# Replicape_B4.net
KiCad netlist of a schematic drawn in EAGLE
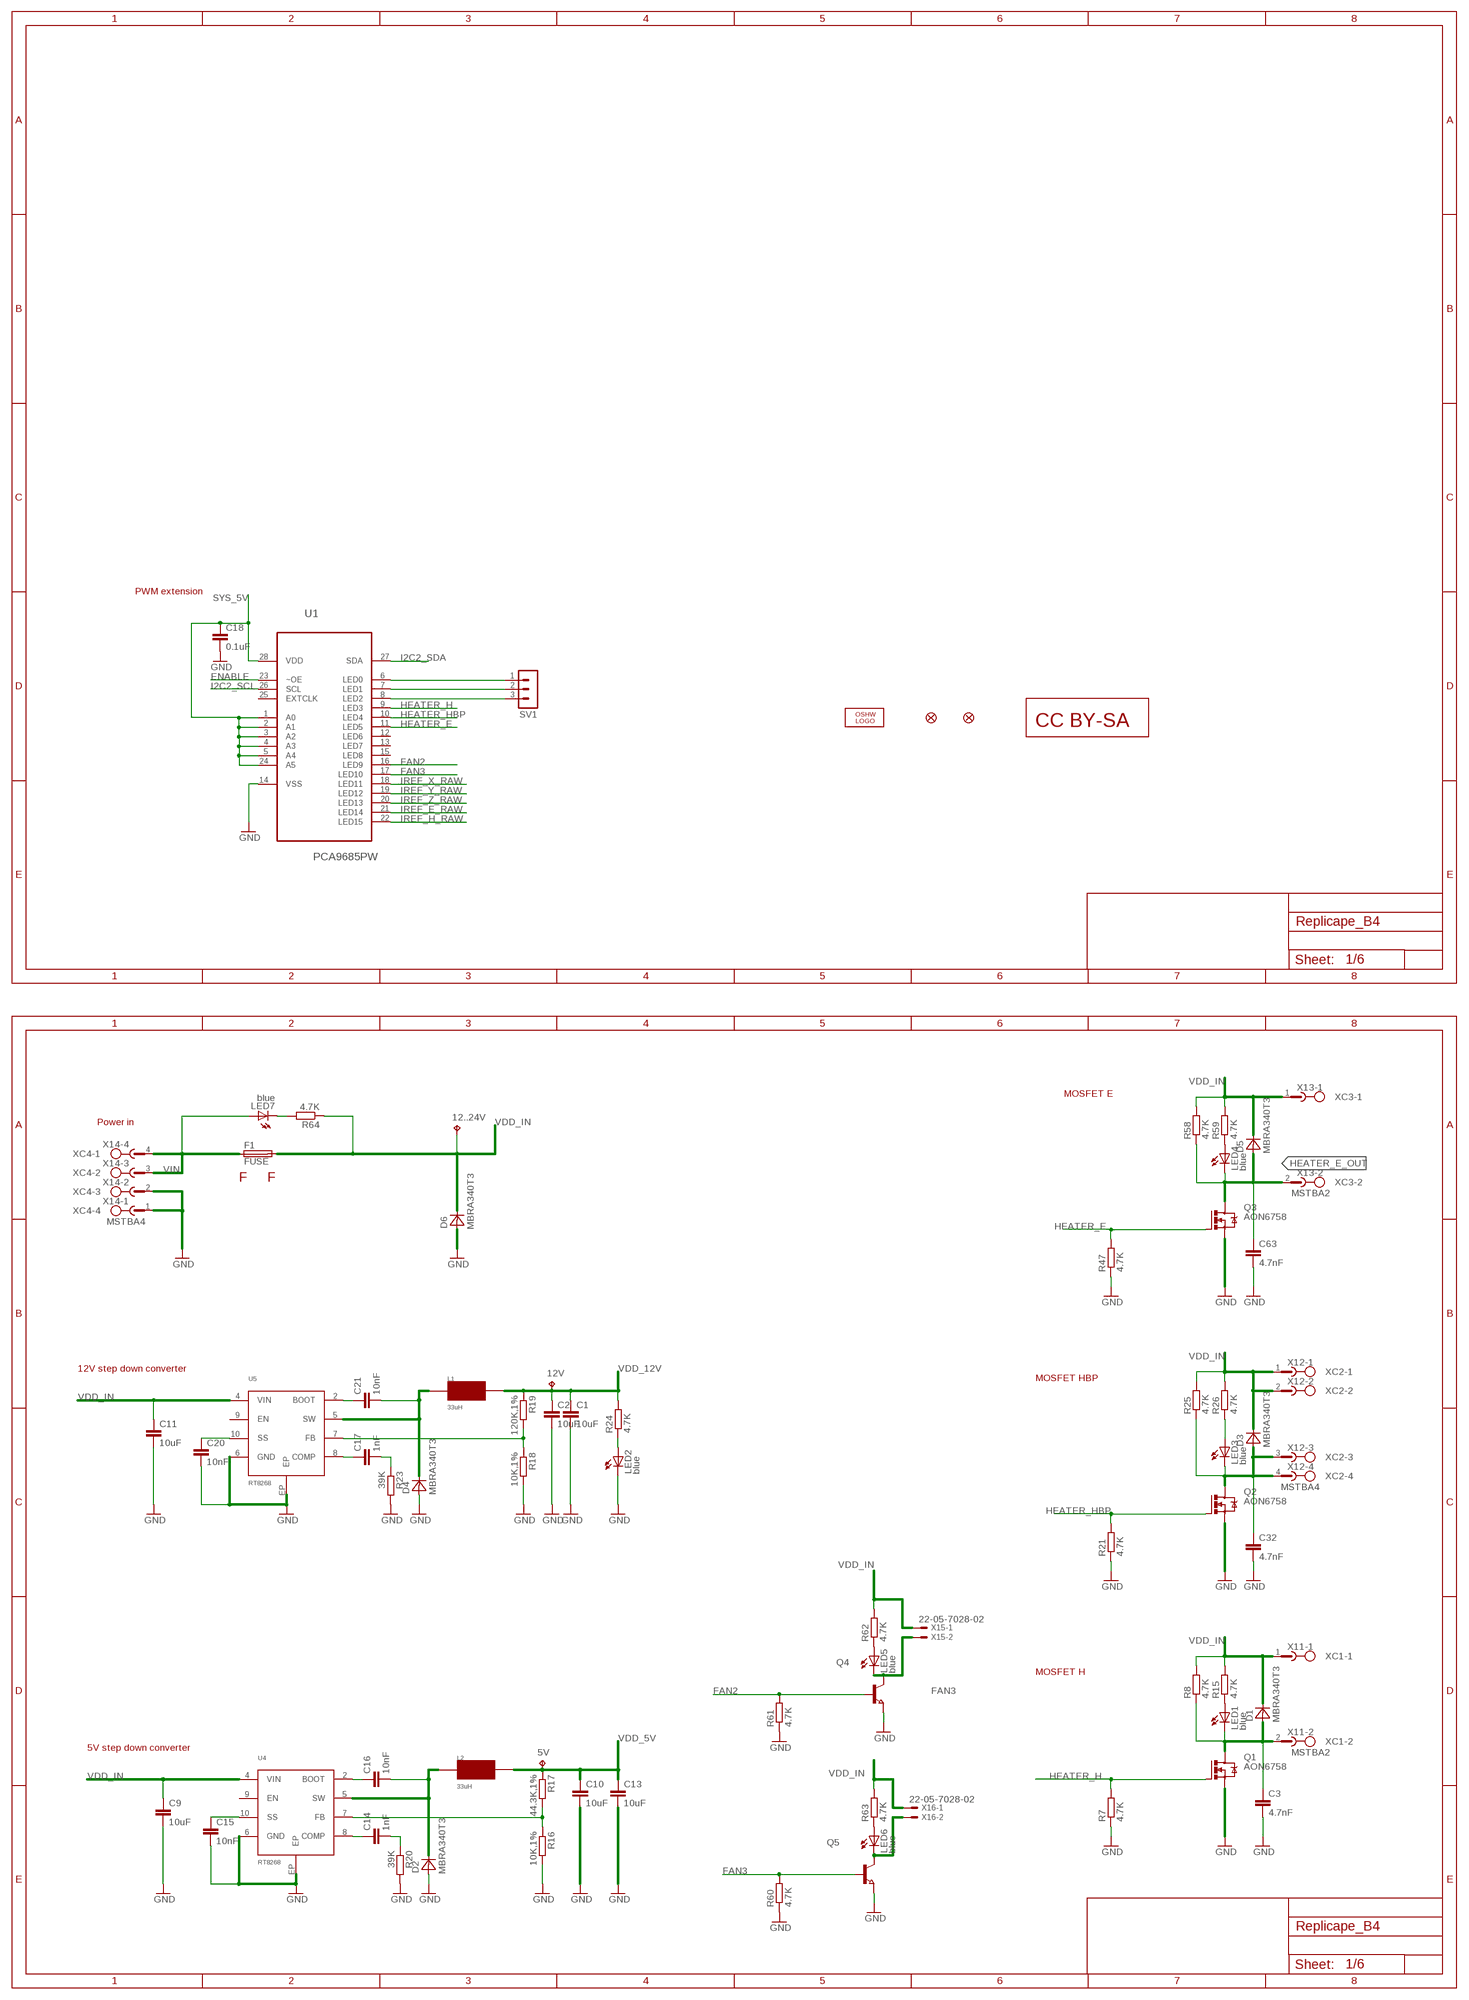
[diagram p0: schematic, sheet 1, part 1 of 2]
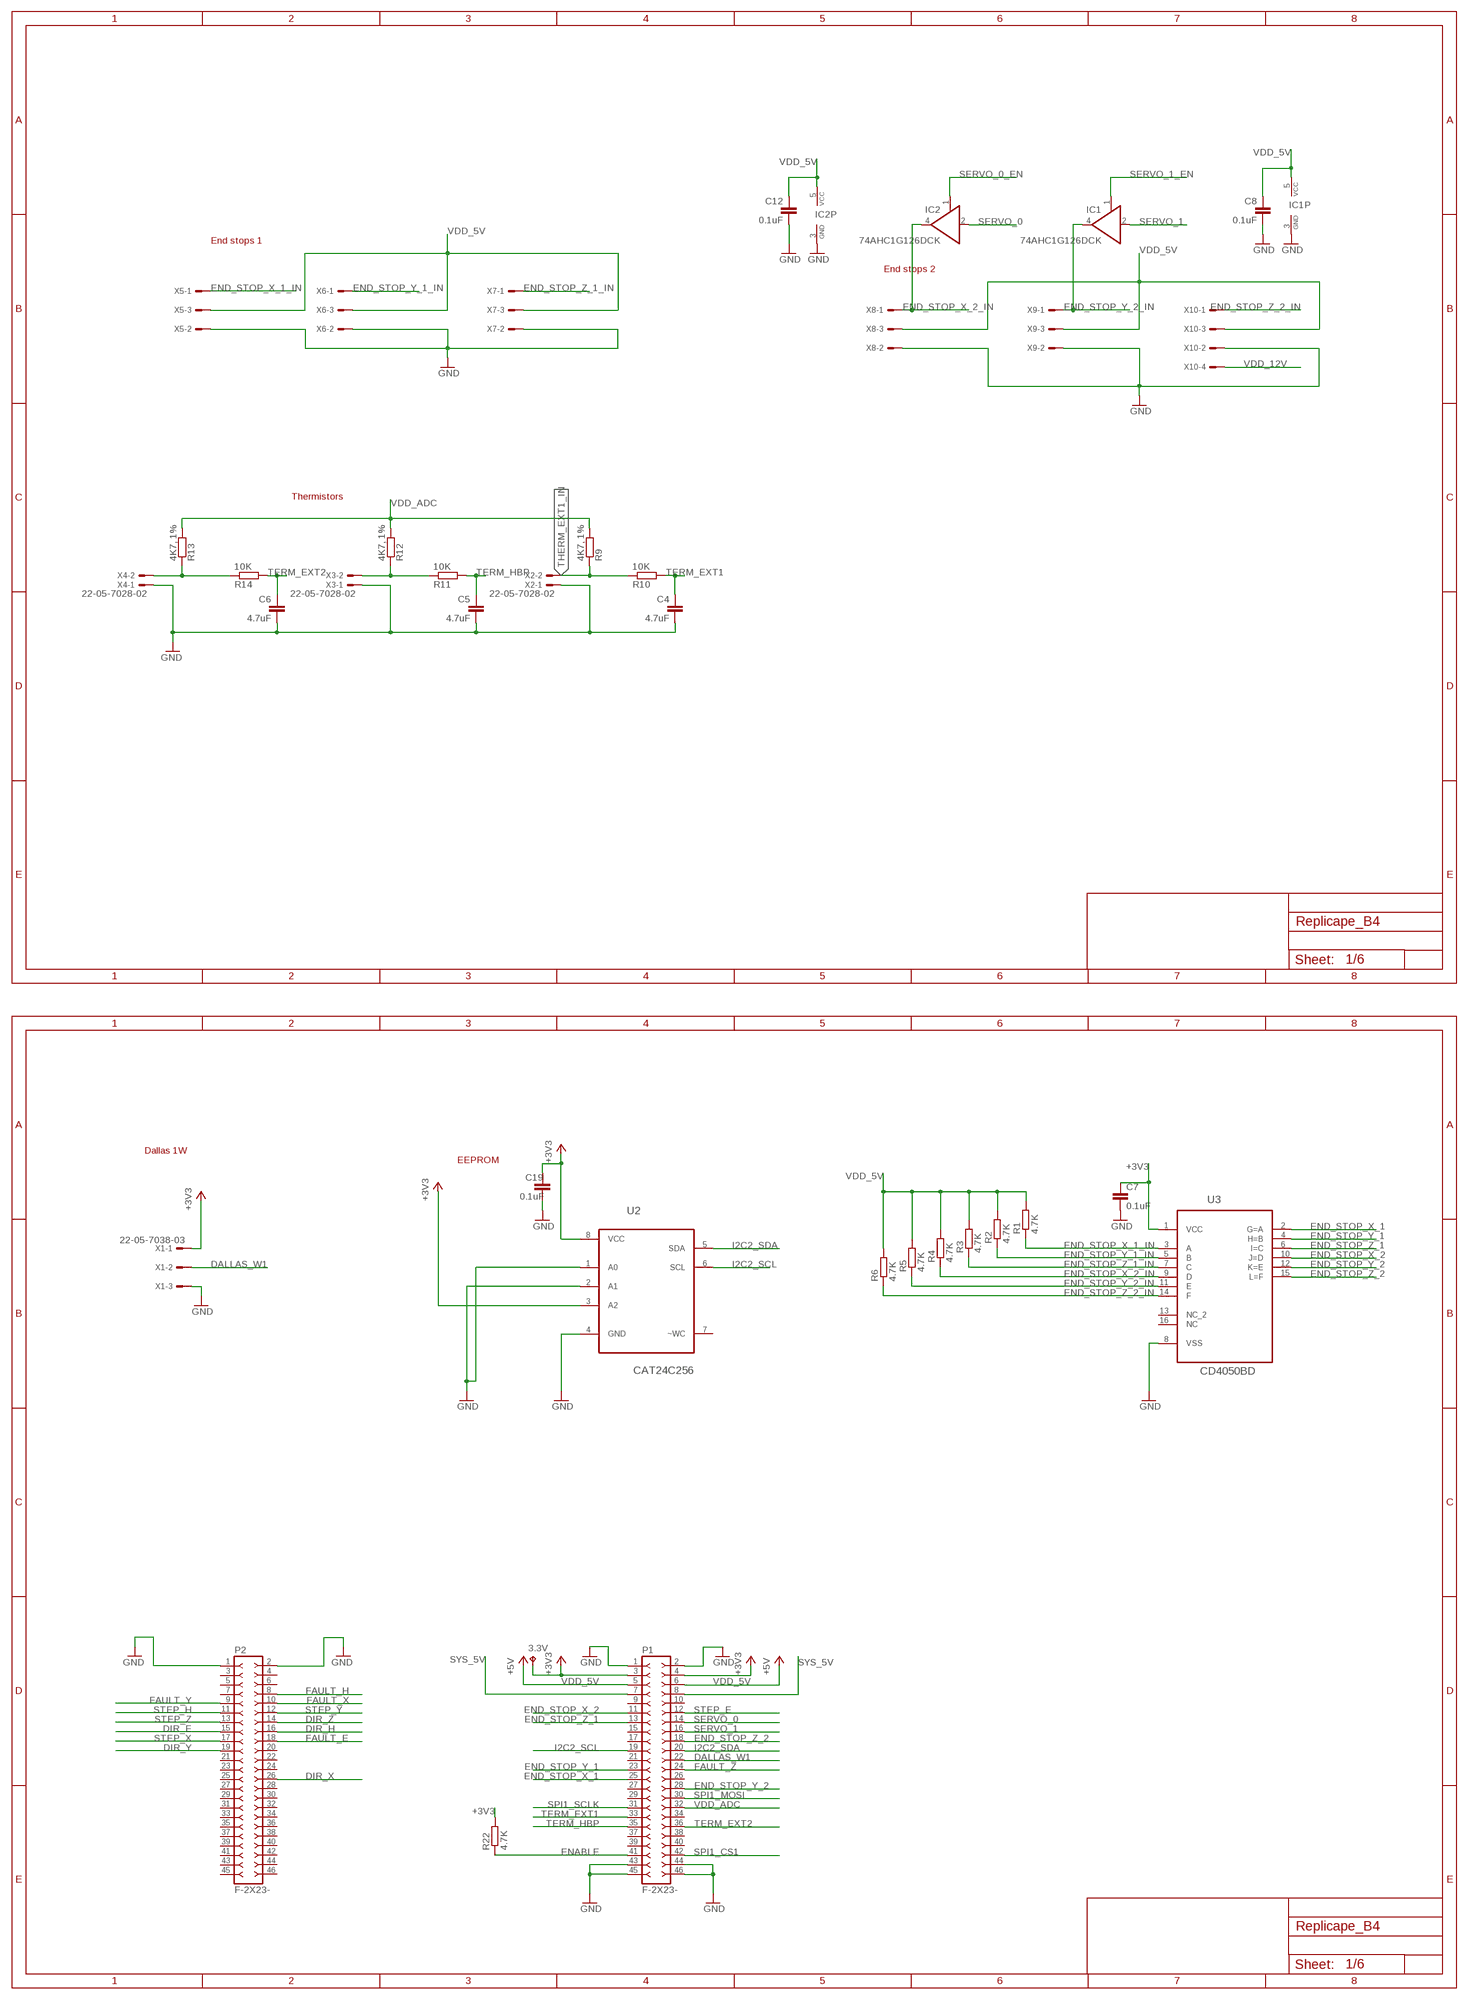
[diagram p1: schematic, sheet 1, part 2 of 2]
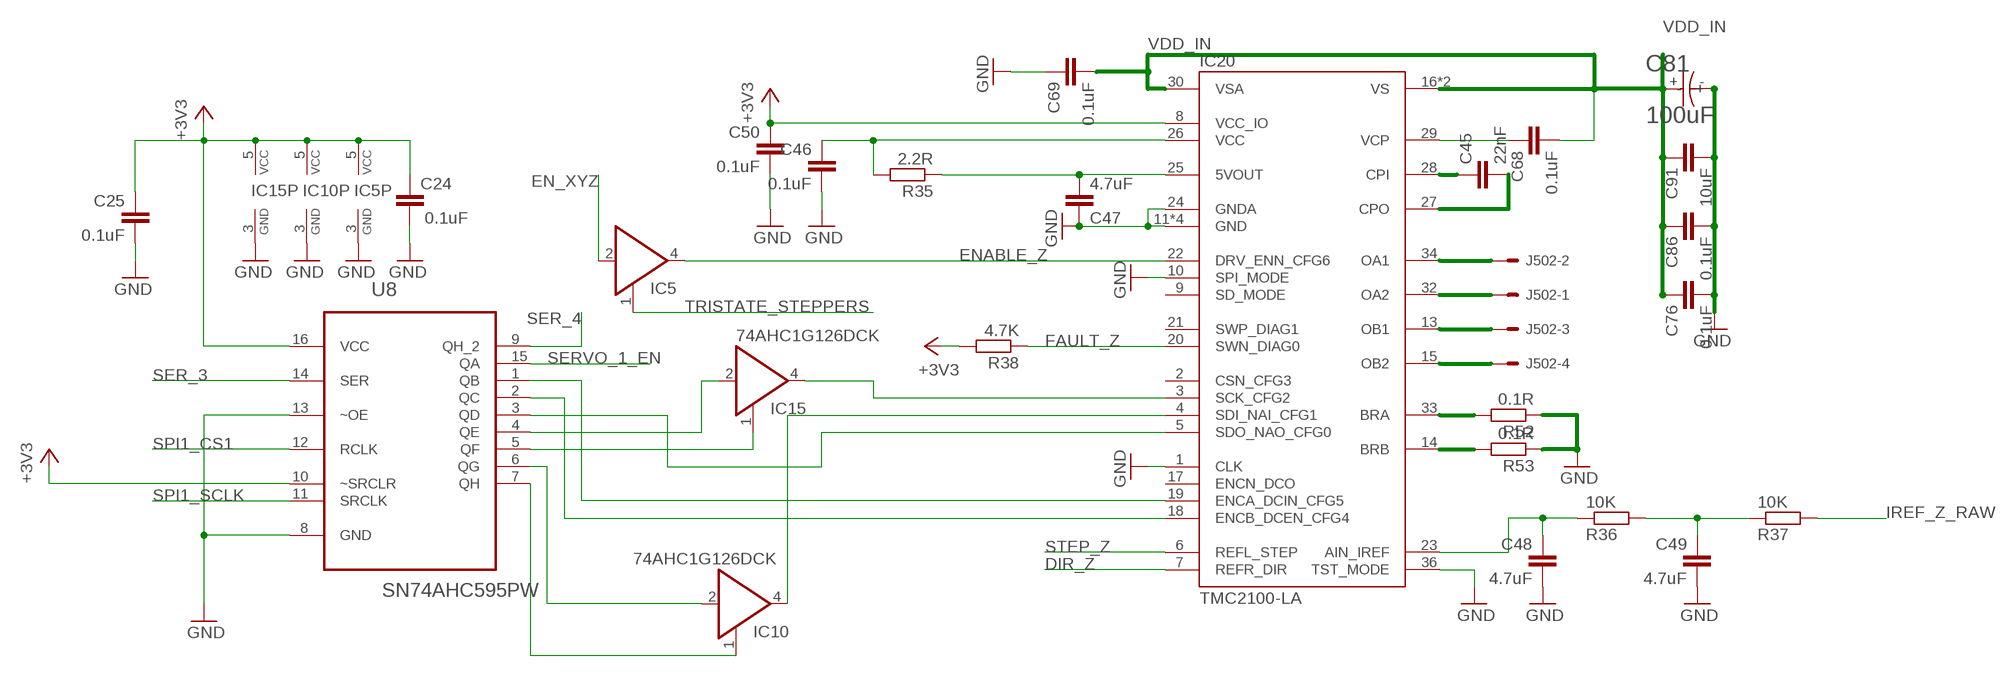
[diagram p2: schematic, sheet 2]
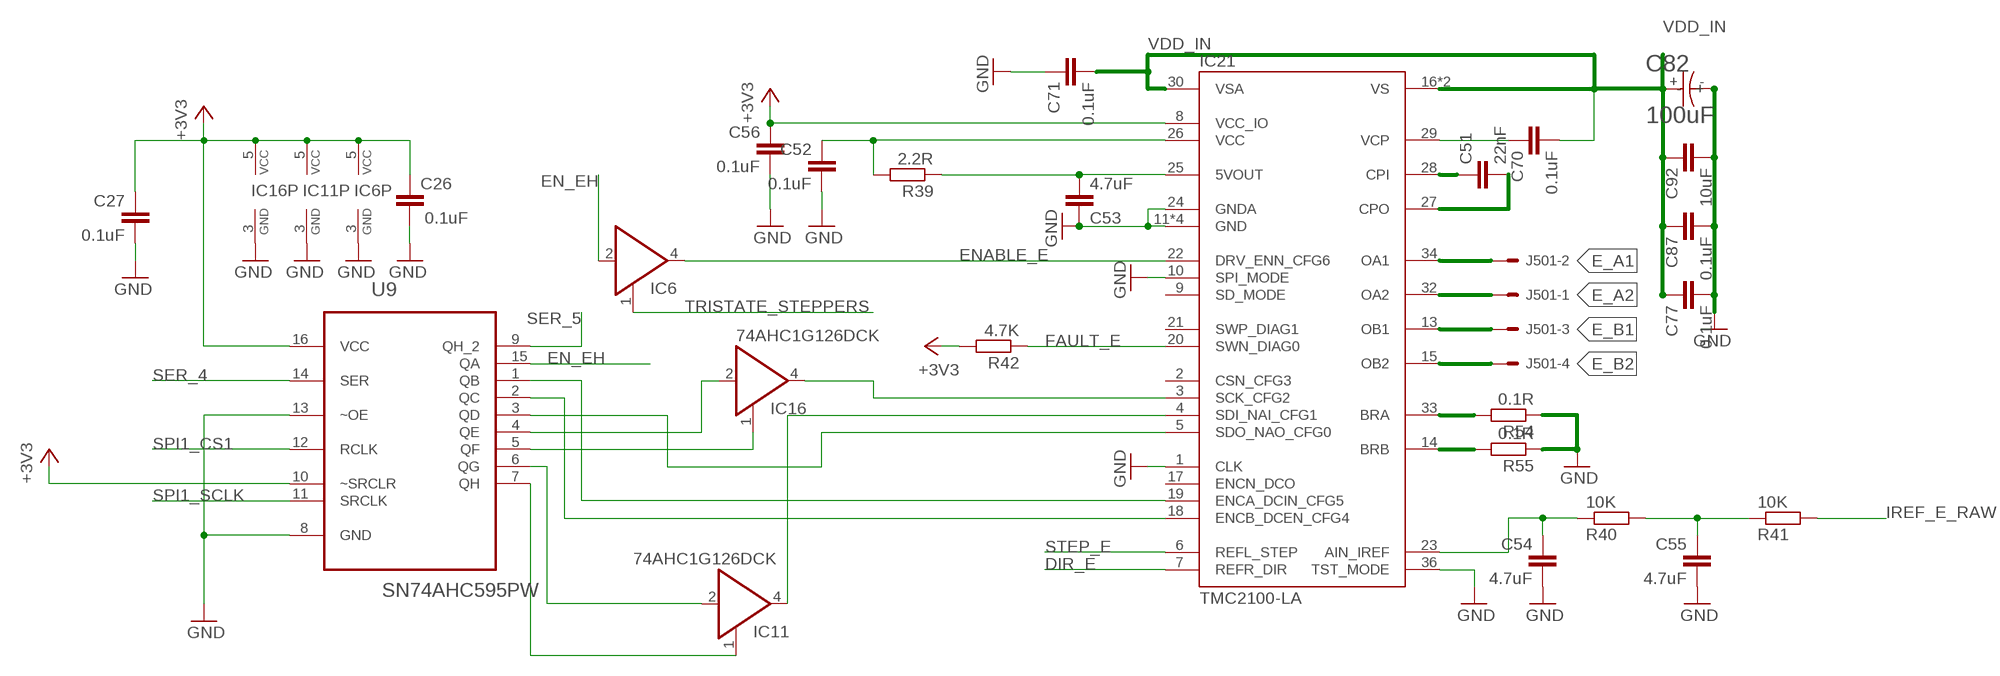
[diagram p3: schematic, sheet 3]
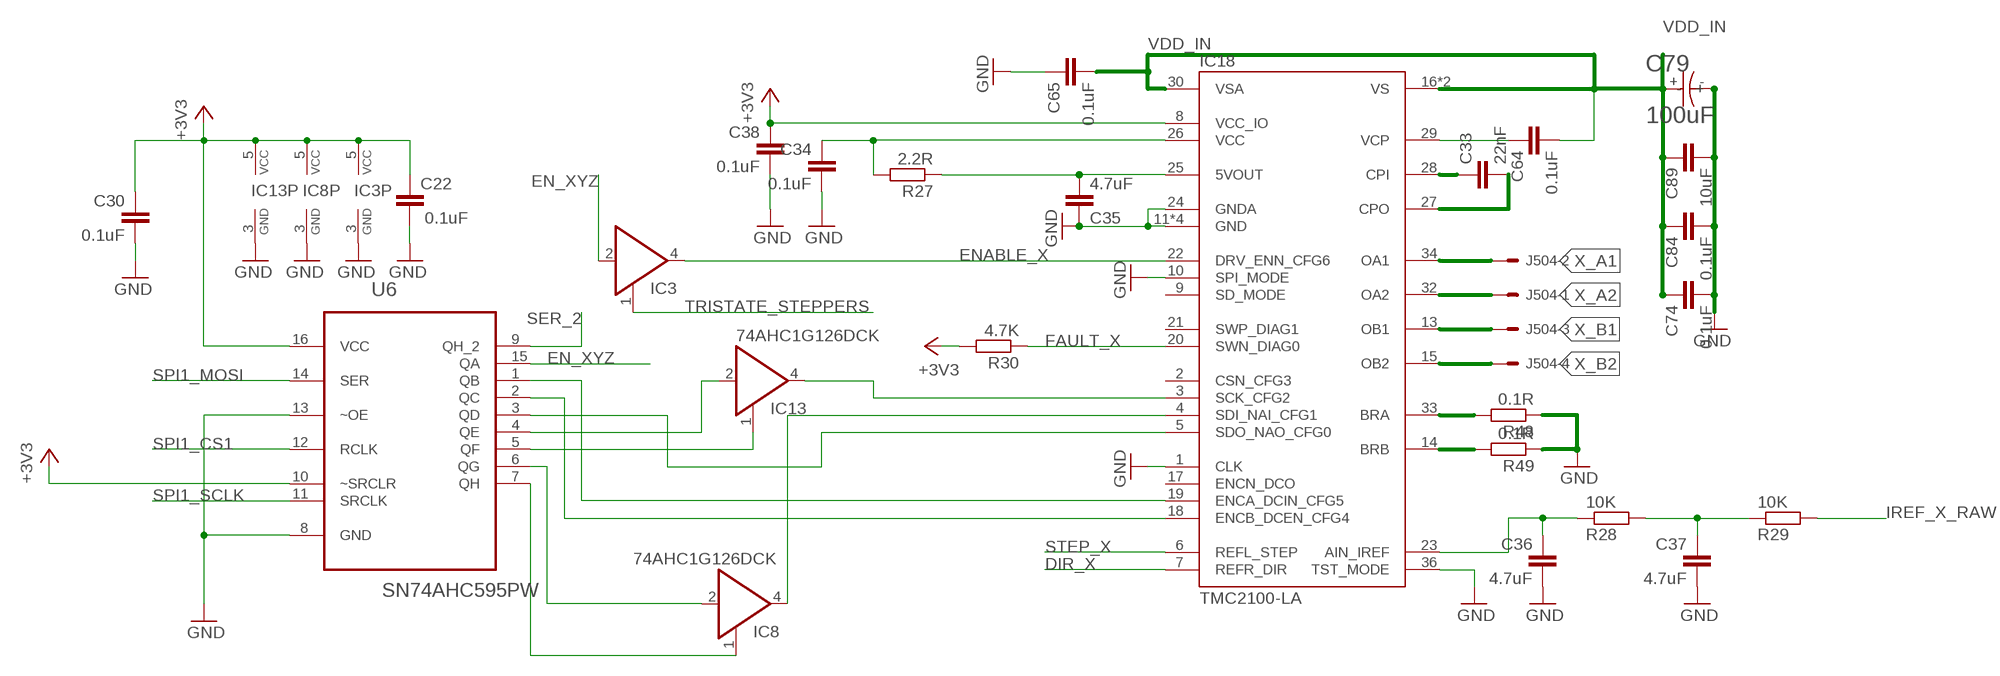
[diagram p4: schematic, sheet 4]
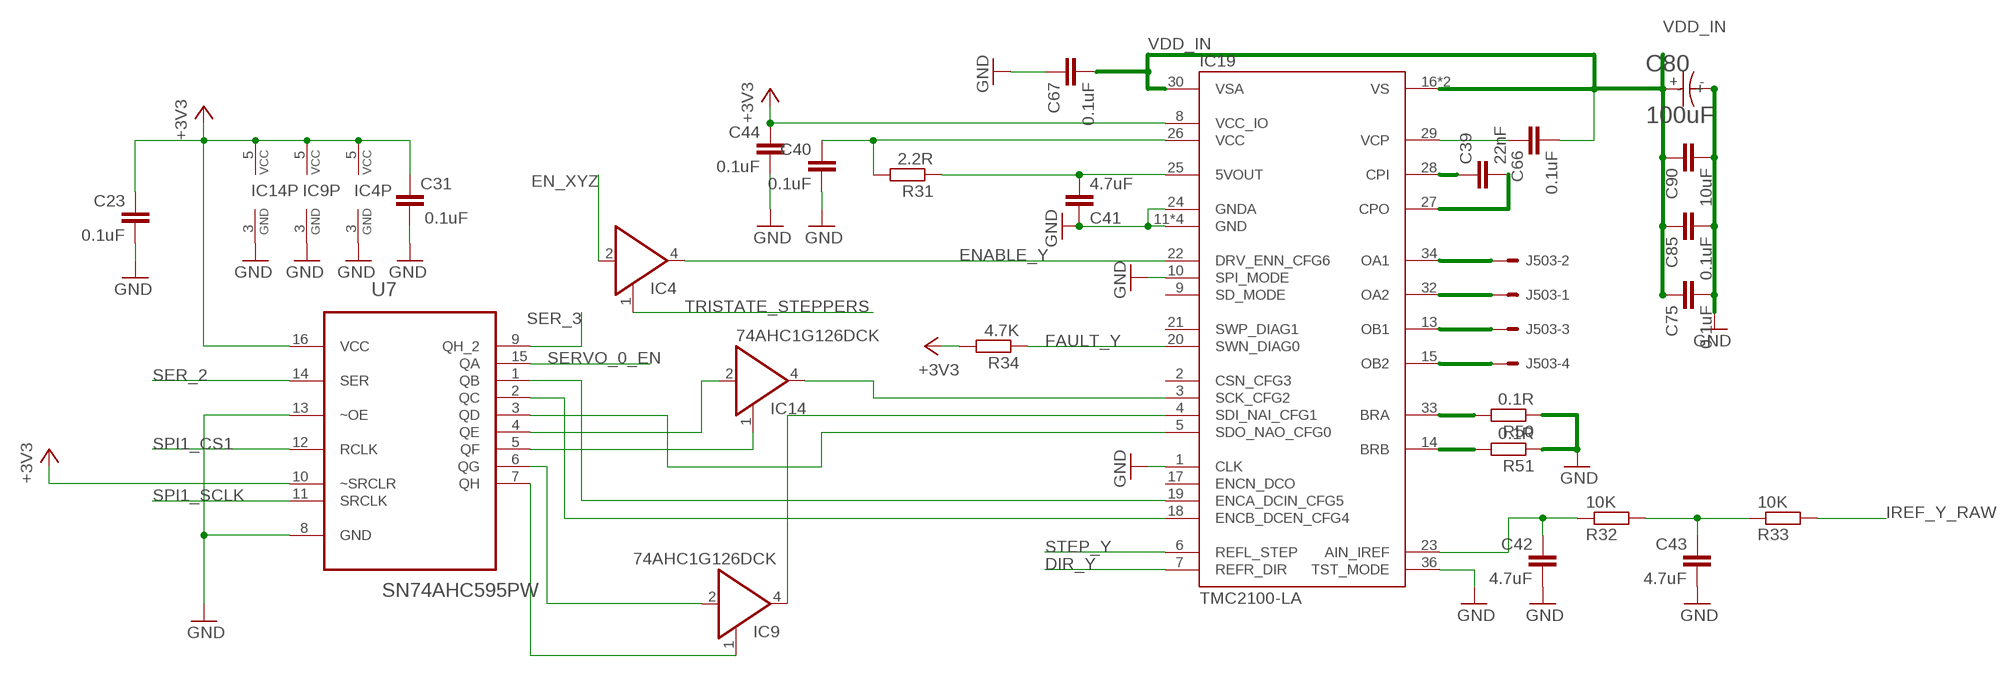
[diagram p5: schematic, sheet 5]
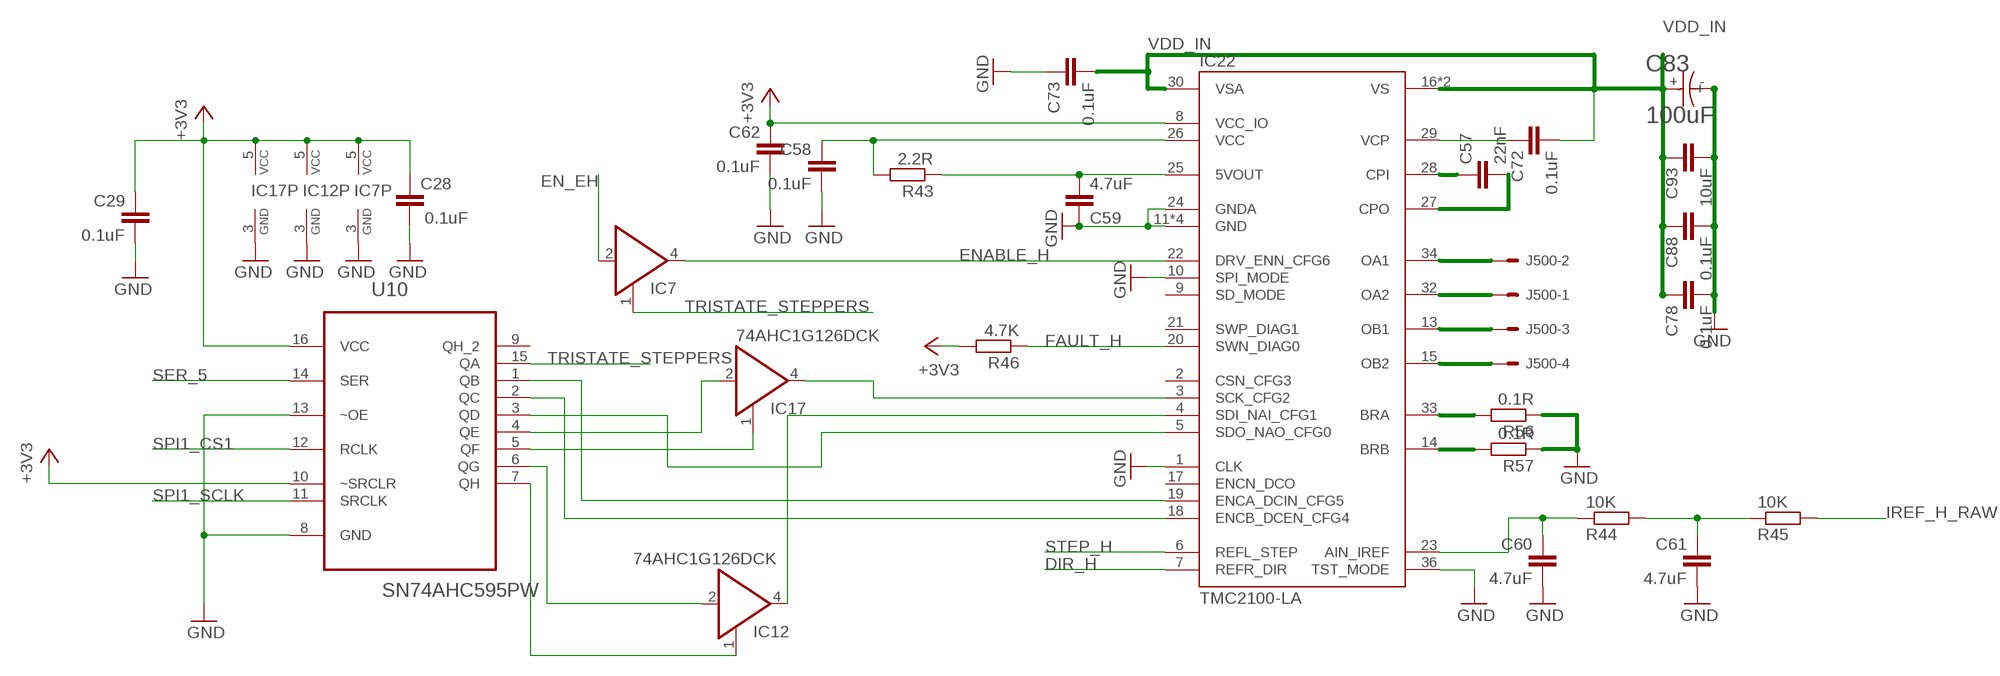
[diagram p6: schematic, sheet 6]

(export (version "E")
  (design (tool "Eeschema 10.0.6"))
  (components
    (comp (ref "C26")
      (value "0.1uF")
      (footprint "eagle-import:C0402")
      (fields (field (name "MPN") "CL10B104KB8NNND"))
      (libsource (lib "eagle-import") (part "C-EUC0402"))
    )
    (comp (ref "C27")
      (value "0.1uF")
      (footprint "eagle-import:C0402")
      (fields (field (name "MPN") "CL10B104KB8NNND"))
      (libsource (lib "eagle-import") (part "C-EUC0402"))
    )
    (comp (ref "C51")
      (value "22nF")
      (footprint "eagle-import:C0402")
      (fields (field (name "MPN") "C1005X7R1E223K050BB"))
      (libsource (lib "eagle-import") (part "C-EUC0402"))
    )
    (comp (ref "C52")
      (value "0.1uF")
      (footprint "eagle-import:C0402")
      (fields (field (name "MPN") "CL10B104KB8NNND"))
      (libsource (lib "eagle-import") (part "C-EUC0402"))
    )
    (comp (ref "C53")
      (value "4.7uF")
      (footprint "eagle-import:C0402")
      (fields (field (name "MPN") "GRM155R60J475ME47D"))
      (libsource (lib "eagle-import") (part "C-EUC0402"))
    )
    (comp (ref "C54")
      (value "4.7uF")
      (footprint "eagle-import:C0402")
      (fields (field (name "MPN") "GRM155R60J475ME47D"))
      (libsource (lib "eagle-import") (part "C-EUC0402"))
    )
    (comp (ref "C55")
      (value "4.7uF")
      (footprint "eagle-import:C0402")
      (fields (field (name "MPN") "GRM155R60J475ME47D"))
      (libsource (lib "eagle-import") (part "C-EUC0402"))
    )
    (comp (ref "C56")
      (value "0.1uF")
      (footprint "eagle-import:C0402")
      (fields (field (name "MPN") "CL10B104KB8NNND"))
      (libsource (lib "eagle-import") (part "C-EUC0402"))
    )
    (comp (ref "C70")
      (value "0.1uF")
      (footprint "eagle-import:C0402")
      (fields (field (name "MPN") "CL10B104KB8NNND"))
      (libsource (lib "eagle-import") (part "C-EUC0402"))
    )
    (comp (ref "C71")
      (value "0.1uF")
      (footprint "eagle-import:C0402")
      (fields (field (name "MPN") "CL10B104KB8NNND"))
      (libsource (lib "eagle-import") (part "C-EUC0402"))
    )
    (comp (ref "C77")
      (value "0.1uF")
      (footprint "eagle-import:C0402")
      (fields (field (name "MPN") "CL10B104KB8NNND"))
      (libsource (lib "eagle-import") (part "C-EUC0402"))
    )
    (comp (ref "C82")
      (value "100uF")
      (footprint "eagle-import:RHS1V10MCN1GS")
      (fields (field (name "MPN") "RHS1V101MCN1GS"))
      (libsource (lib "eagle-import") (part "C"))
    )
    (comp (ref "C87")
      (value "0.1uF")
      (footprint "eagle-import:C0402")
      (fields (field (name "MPN") "CL10B104KB8NNND"))
      (libsource (lib "eagle-import") (part "C-EUC0402"))
    )
    (comp (ref "C92")
      (value "10uF")
      (footprint "eagle-import:C0805")
      (fields (field (name "MPN") "C2012X5R1V106M085AC"))
      (libsource (lib "eagle-import") (part "C-EUC0805"))
    )
    (comp (ref "IC6")
      (value "74AHC1G126DCK")
      (footprint "eagle-import:SC70-5")
      (fields (field (name "MPN") "M74VHC1GT126DF1G"))
      (libsource (lib "eagle-import") (part "741G126DCKAHC"))
    )
    (comp (ref "IC11")
      (value "74AHC1G126DCK")
      (footprint "eagle-import:SC70-5")
      (fields (field (name "MPN") "M74VHC1GT126DF1G"))
      (libsource (lib "eagle-import") (part "741G126DCKAHC"))
    )
    (comp (ref "IC16")
      (value "74AHC1G126DCK")
      (footprint "eagle-import:SC70-5")
      (fields (field (name "MPN") "M74VHC1GT126DF1G"))
      (libsource (lib "eagle-import") (part "741G126DCKAHC"))
    )
    (comp (ref "IC21")
      (value "TMC2100-LA")
      (footprint "eagle-import:QFN36-PAD")
      (fields (field (name "MPN") "TMC2100-LA-T"))
      (libsource (lib "eagle-import") (part "TMC2100-LA"))
    )
    (comp (ref "J501")
      (value "22-05-7048-04")
      (footprint "eagle-import:7395-04")
      (fields (field (name "MPN") "640455-4"))
      (libsource (lib "eagle-import") (part "22-?-0405-7048"))
    )
    (comp (ref "R39")
      (value "2.2R")
      (footprint "eagle-import:R0402")
      (fields (field (name "MPN") "RC1005J2R2CS"))
      (libsource (lib "eagle-import") (part "R-EU_R0402"))
    )
    (comp (ref "R40")
      (value "10K")
      (footprint "eagle-import:R0402")
      (fields (field (name "MPN") "RC0402FR-0710KL"))
      (libsource (lib "eagle-import") (part "R-EU_R0402"))
    )
    (comp (ref "R41")
      (value "10K")
      (footprint "eagle-import:R0402")
      (fields (field (name "MPN") "RC0402FR-0710KL"))
      (libsource (lib "eagle-import") (part "R-EU_R0402"))
    )
    (comp (ref "R42")
      (value "4.7K")
      (footprint "eagle-import:R0402")
      (fields (field (name "MPN") "RC0402JR-074K7L"))
      (libsource (lib "eagle-import") (part "R-EU_R0402"))
    )
    (comp (ref "R54")
      (value "0.1R")
      (footprint "eagle-import:R0805")
      (fields (field (name "MPN") "RL1220S-R10-F"))
      (libsource (lib "eagle-import") (part "R-EU_R0805"))
    )
    (comp (ref "R55")
      (value "0.1R")
      (footprint "eagle-import:R0805")
      (fields (field (name "MPN") "RL1220S-R10-F"))
      (libsource (lib "eagle-import") (part "R-EU_R0805"))
    )
    (comp (ref "U9")
      (value "SN74AHC595PW")
      (footprint "eagle-import:SOP65P640X120-16N")
      (fields (field (name "MPN") "MC74HC595ADTR2G"))
      (libsource (lib "eagle-import") (part "SN74AHC595PW"))
    )
    (comp (ref "C24")
      (value "0.1uF")
      (footprint "eagle-import:C0402")
      (fields (field (name "MPN") "CL10B104KB8NNND"))
      (libsource (lib "eagle-import") (part "C-EUC0402"))
    )
    (comp (ref "C25")
      (value "0.1uF")
      (footprint "eagle-import:C0402")
      (fields (field (name "MPN") "CL10B104KB8NNND"))
      (libsource (lib "eagle-import") (part "C-EUC0402"))
    )
    (comp (ref "C45")
      (value "22nF")
      (footprint "eagle-import:C0402")
      (fields (field (name "MPN") "C1005X7R1E223K050BB"))
      (libsource (lib "eagle-import") (part "C-EUC0402"))
    )
    (comp (ref "C46")
      (value "0.1uF")
      (footprint "eagle-import:C0402")
      (fields (field (name "MPN") "CL10B104KB8NNND"))
      (libsource (lib "eagle-import") (part "C-EUC0402"))
    )
    (comp (ref "C47")
      (value "4.7uF")
      (footprint "eagle-import:C0402")
      (fields (field (name "MPN") "GRM155R60J475ME47D"))
      (libsource (lib "eagle-import") (part "C-EUC0402"))
    )
    (comp (ref "C48")
      (value "4.7uF")
      (footprint "eagle-import:C0402")
      (fields (field (name "MPN") "GRM155R60J475ME47D"))
      (libsource (lib "eagle-import") (part "C-EUC0402"))
    )
    (comp (ref "C49")
      (value "4.7uF")
      (footprint "eagle-import:C0402")
      (fields (field (name "MPN") "GRM155R60J475ME47D"))
      (libsource (lib "eagle-import") (part "C-EUC0402"))
    )
    (comp (ref "C50")
      (value "0.1uF")
      (footprint "eagle-import:C0402")
      (fields (field (name "MPN") "CL10B104KB8NNND"))
      (libsource (lib "eagle-import") (part "C-EUC0402"))
    )
    (comp (ref "C68")
      (value "0.1uF")
      (footprint "eagle-import:C0402")
      (fields (field (name "MPN") "CL10B104KB8NNND"))
      (libsource (lib "eagle-import") (part "C-EUC0402"))
    )
    (comp (ref "C69")
      (value "0.1uF")
      (footprint "eagle-import:C0402")
      (fields (field (name "MPN") "CL10B104KB8NNND"))
      (libsource (lib "eagle-import") (part "C-EUC0402"))
    )
    (comp (ref "C76")
      (value "0.1uF")
      (footprint "eagle-import:C0402")
      (fields (field (name "MPN") "CL10B104KB8NNND"))
      (libsource (lib "eagle-import") (part "C-EUC0402"))
    )
    (comp (ref "C81")
      (value "100uF")
      (footprint "eagle-import:RHS1V10MCN1GS")
      (fields (field (name "MPN") "RHS1V101MCN1GS"))
      (libsource (lib "eagle-import") (part "C"))
    )
    (comp (ref "C86")
      (value "0.1uF")
      (footprint "eagle-import:C0402")
      (fields (field (name "MPN") "CL10B104KB8NNND"))
      (libsource (lib "eagle-import") (part "C-EUC0402"))
    )
    (comp (ref "C91")
      (value "10uF")
      (footprint "eagle-import:C0805")
      (fields (field (name "MPN") "C2012X5R1V106M085AC"))
      (libsource (lib "eagle-import") (part "C-EUC0805"))
    )
    (comp (ref "IC5")
      (value "74AHC1G126DCK")
      (footprint "eagle-import:SC70-5")
      (fields (field (name "MPN") "M74VHC1GT126DF1G"))
      (libsource (lib "eagle-import") (part "741G126DCKAHC"))
    )
    (comp (ref "IC10")
      (value "74AHC1G126DCK")
      (footprint "eagle-import:SC70-5")
      (fields (field (name "MPN") "M74VHC1GT126DF1G"))
      (libsource (lib "eagle-import") (part "741G126DCKAHC"))
    )
    (comp (ref "IC15")
      (value "74AHC1G126DCK")
      (footprint "eagle-import:SC70-5")
      (fields (field (name "MPN") "M74VHC1GT126DF1G"))
      (libsource (lib "eagle-import") (part "741G126DCKAHC"))
    )
    (comp (ref "IC20")
      (value "TMC2100-LA")
      (footprint "eagle-import:QFN36-PAD")
      (fields (field (name "MPN") "TMC2100-LA-T"))
      (libsource (lib "eagle-import") (part "TMC2100-LA"))
    )
    (comp (ref "J502")
      (value "22-05-7048-04")
      (footprint "eagle-import:7395-04")
      (fields (field (name "MPN") "640455-4"))
      (libsource (lib "eagle-import") (part "22-?-0405-7048"))
    )
    (comp (ref "R35")
      (value "2.2R")
      (footprint "eagle-import:R0402")
      (fields (field (name "MPN") "RC1005J2R2CS"))
      (libsource (lib "eagle-import") (part "R-EU_R0402"))
    )
    (comp (ref "R36")
      (value "10K")
      (footprint "eagle-import:R0402")
      (fields (field (name "MPN") "RC0402FR-0710KL"))
      (libsource (lib "eagle-import") (part "R-EU_R0402"))
    )
    (comp (ref "R37")
      (value "10K")
      (footprint "eagle-import:R0402")
      (fields (field (name "MPN") "RC0402FR-0710KL"))
      (libsource (lib "eagle-import") (part "R-EU_R0402"))
    )
    (comp (ref "R38")
      (value "4.7K")
      (footprint "eagle-import:R0402")
      (fields (field (name "MPN") "RC0402JR-074K7L"))
      (libsource (lib "eagle-import") (part "R-EU_R0402"))
    )
    (comp (ref "R52")
      (value "0.1R")
      (footprint "eagle-import:R0805")
      (fields (field (name "MPN") "RL1220S-R10-F"))
      (libsource (lib "eagle-import") (part "R-EU_R0805"))
    )
    (comp (ref "R53")
      (value "0.1R")
      (footprint "eagle-import:R0805")
      (fields (field (name "MPN") "RL1220S-R10-F"))
      (libsource (lib "eagle-import") (part "R-EU_R0805"))
    )
    (comp (ref "U8")
      (value "SN74AHC595PW")
      (footprint "eagle-import:SOP65P640X120-16N")
      (fields (field (name "MPN") "MC74HC595ADTR2G"))
      (libsource (lib "eagle-import") (part "SN74AHC595PW"))
    )
    (comp (ref "C22")
      (value "0.1uF")
      (footprint "eagle-import:C0402")
      (fields (field (name "MPN") "CL10B104KB8NNND"))
      (libsource (lib "eagle-import") (part "C-EUC0402"))
    )
    (comp (ref "C30")
      (value "0.1uF")
      (footprint "eagle-import:C0402")
      (fields (field (name "MPN") "CL10B104KB8NNND"))
      (libsource (lib "eagle-import") (part "C-EUC0402"))
    )
    (comp (ref "C33")
      (value "22nF")
      (footprint "eagle-import:C0402")
      (fields (field (name "MPN") "C1005X7R1E223K050BB"))
      (libsource (lib "eagle-import") (part "C-EUC0402"))
    )
    (comp (ref "C34")
      (value "0.1uF")
      (footprint "eagle-import:C0402")
      (fields (field (name "MPN") "CL10B104KB8NNND"))
      (libsource (lib "eagle-import") (part "C-EUC0402"))
    )
    (comp (ref "C35")
      (value "4.7uF")
      (footprint "eagle-import:C0402")
      (fields (field (name "MPN") "GRM155R60J475ME47D"))
      (libsource (lib "eagle-import") (part "C-EUC0402"))
    )
    (comp (ref "C36")
      (value "4.7uF")
      (footprint "eagle-import:C0402")
      (fields (field (name "MPN") "GRM155R60J475ME47D"))
      (libsource (lib "eagle-import") (part "C-EUC0402"))
    )
    (comp (ref "C37")
      (value "4.7uF")
      (footprint "eagle-import:C0402")
      (fields (field (name "MPN") "GRM155R60J475ME47D"))
      (libsource (lib "eagle-import") (part "C-EUC0402"))
    )
    (comp (ref "C38")
      (value "0.1uF")
      (footprint "eagle-import:C0402")
      (fields (field (name "MPN") "CL10B104KB8NNND"))
      (libsource (lib "eagle-import") (part "C-EUC0402"))
    )
    (comp (ref "C64")
      (value "0.1uF")
      (footprint "eagle-import:C0402")
      (fields (field (name "MPN") "CL10B104KB8NNND"))
      (libsource (lib "eagle-import") (part "C-EUC0402"))
    )
    (comp (ref "C65")
      (value "0.1uF")
      (footprint "eagle-import:C0402")
      (fields (field (name "MPN") "CL10B104KB8NNND"))
      (libsource (lib "eagle-import") (part "C-EUC0402"))
    )
    (comp (ref "C74")
      (value "0.1uF")
      (footprint "eagle-import:C0402")
      (fields (field (name "MPN") "CL10B104KB8NNND"))
      (libsource (lib "eagle-import") (part "C-EUC0402"))
    )
    (comp (ref "C79")
      (value "100uF")
      (footprint "eagle-import:RHS1V10MCN1GS")
      (fields (field (name "MPN") "RHS1V101MCN1GS"))
      (libsource (lib "eagle-import") (part "C"))
    )
    (comp (ref "C84")
      (value "0.1uF")
      (footprint "eagle-import:C0402")
      (fields (field (name "MPN") "CL10B104KB8NNND"))
      (libsource (lib "eagle-import") (part "C-EUC0402"))
    )
    (comp (ref "C89")
      (value "10uF")
      (footprint "eagle-import:C0805")
      (fields (field (name "MPN") "C2012X5R1V106M085AC"))
      (libsource (lib "eagle-import") (part "C-EUC0805"))
    )
    (comp (ref "IC3")
      (value "74AHC1G126DCK")
      (footprint "eagle-import:SC70-5")
      (fields (field (name "MPN") "M74VHC1GT126DF1G"))
      (libsource (lib "eagle-import") (part "741G126DCKAHC"))
    )
    (comp (ref "IC8")
      (value "74AHC1G126DCK")
      (footprint "eagle-import:SC70-5")
      (fields (field (name "MPN") "M74VHC1GT126DF1G"))
      (libsource (lib "eagle-import") (part "741G126DCKAHC"))
    )
    (comp (ref "IC13")
      (value "74AHC1G126DCK")
      (footprint "eagle-import:SC70-5")
      (fields (field (name "MPN") "M74VHC1GT126DF1G"))
      (libsource (lib "eagle-import") (part "741G126DCKAHC"))
    )
    (comp (ref "IC18")
      (value "TMC2100-LA")
      (footprint "eagle-import:QFN36-PAD")
      (fields (field (name "MPN") "TMC2100-LA-T"))
      (libsource (lib "eagle-import") (part "TMC2100-LA"))
    )
    (comp (ref "J504")
      (value "22-05-7048-04")
      (footprint "eagle-import:7395-04")
      (fields (field (name "MPN") "640455-4"))
      (libsource (lib "eagle-import") (part "22-?-0405-7048"))
    )
    (comp (ref "R27")
      (value "2.2R")
      (footprint "eagle-import:R0402")
      (fields (field (name "MPN") "RC1005J2R2CS"))
      (libsource (lib "eagle-import") (part "R-EU_R0402"))
    )
    (comp (ref "R28")
      (value "10K")
      (footprint "eagle-import:R0402")
      (fields (field (name "MPN") "RC0402FR-0710KL"))
      (libsource (lib "eagle-import") (part "R-EU_R0402"))
    )
    (comp (ref "R29")
      (value "10K")
      (footprint "eagle-import:R0402")
      (fields (field (name "MPN") "RC0402FR-0710KL"))
      (libsource (lib "eagle-import") (part "R-EU_R0402"))
    )
    (comp (ref "R30")
      (value "4.7K")
      (footprint "eagle-import:R0402")
      (fields (field (name "MPN") "RC0402JR-074K7L"))
      (libsource (lib "eagle-import") (part "R-EU_R0402"))
    )
    (comp (ref "R48")
      (value "0.1R")
      (footprint "eagle-import:R0805")
      (fields (field (name "MPN") "RL1220S-R10-F"))
      (libsource (lib "eagle-import") (part "R-EU_R0805"))
    )
    (comp (ref "R49")
      (value "0.1R")
      (footprint "eagle-import:R0805")
      (fields (field (name "MPN") "RL1220S-R10-F"))
      (libsource (lib "eagle-import") (part "R-EU_R0805"))
    )
    (comp (ref "U6")
      (value "SN74AHC595PW")
      (footprint "eagle-import:SOP65P640X120-16N")
      (fields (field (name "MPN") "MC74HC595ADTR2G"))
      (libsource (lib "eagle-import") (part "SN74AHC595PW"))
    )
    (comp (ref "C23")
      (value "0.1uF")
      (footprint "eagle-import:C0402")
      (fields (field (name "MPN") "CL10B104KB8NNND"))
      (libsource (lib "eagle-import") (part "C-EUC0402"))
    )
    (comp (ref "C31")
      (value "0.1uF")
      (footprint "eagle-import:C0402")
      (fields (field (name "MPN") "CL10B104KB8NNND"))
      (libsource (lib "eagle-import") (part "C-EUC0402"))
    )
    (comp (ref "C39")
      (value "22nF")
      (footprint "eagle-import:C0402")
      (fields (field (name "MPN") "C1005X7R1E223K050BB"))
      (libsource (lib "eagle-import") (part "C-EUC0402"))
    )
    (comp (ref "C40")
      (value "0.1uF")
      (footprint "eagle-import:C0402")
      (fields (field (name "MPN") "CL10B104KB8NNND"))
      (libsource (lib "eagle-import") (part "C-EUC0402"))
    )
    (comp (ref "C41")
      (value "4.7uF")
      (footprint "eagle-import:C0402")
      (fields (field (name "MPN") "GRM155R60J475ME47D"))
      (libsource (lib "eagle-import") (part "C-EUC0402"))
    )
    (comp (ref "C42")
      (value "4.7uF")
      (footprint "eagle-import:C0402")
      (fields (field (name "MPN") "GRM155R60J475ME47D"))
      (libsource (lib "eagle-import") (part "C-EUC0402"))
    )
    (comp (ref "C43")
      (value "4.7uF")
      (footprint "eagle-import:C0402")
      (fields (field (name "MPN") "GRM155R60J475ME47D"))
      (libsource (lib "eagle-import") (part "C-EUC0402"))
    )
    (comp (ref "C44")
      (value "0.1uF")
      (footprint "eagle-import:C0402")
      (fields (field (name "MPN") "CL10B104KB8NNND"))
      (libsource (lib "eagle-import") (part "C-EUC0402"))
    )
    (comp (ref "C66")
      (value "0.1uF")
      (footprint "eagle-import:C0402")
      (fields (field (name "MPN") "CL10B104KB8NNND"))
      (libsource (lib "eagle-import") (part "C-EUC0402"))
    )
    (comp (ref "C67")
      (value "0.1uF")
      (footprint "eagle-import:C0402")
      (fields (field (name "MPN") "CL10B104KB8NNND"))
      (libsource (lib "eagle-import") (part "C-EUC0402"))
    )
    (comp (ref "C75")
      (value "0.1uF")
      (footprint "eagle-import:C0402")
      (fields (field (name "MPN") "CL10B104KB8NNND"))
      (libsource (lib "eagle-import") (part "C-EUC0402"))
    )
    (comp (ref "C80")
      (value "100uF")
      (footprint "eagle-import:RHS1V10MCN1GS")
      (fields (field (name "MPN") "RHS1V101MCN1GS"))
      (libsource (lib "eagle-import") (part "C"))
    )
    (comp (ref "C85")
      (value "0.1uF")
      (footprint "eagle-import:C0402")
      (fields (field (name "MPN") "CL10B104KB8NNND"))
      (libsource (lib "eagle-import") (part "C-EUC0402"))
    )
    (comp (ref "C90")
      (value "10uF")
      (footprint "eagle-import:C0805")
      (fields (field (name "MPN") "C2012X5R1V106M085AC"))
      (libsource (lib "eagle-import") (part "C-EUC0805"))
    )
    (comp (ref "IC4")
      (value "74AHC1G126DCK")
      (footprint "eagle-import:SC70-5")
      (fields (field (name "MPN") "M74VHC1GT126DF1G"))
      (libsource (lib "eagle-import") (part "741G126DCKAHC"))
    )
    (comp (ref "IC9")
      (value "74AHC1G126DCK")
      (footprint "eagle-import:SC70-5")
      (fields (field (name "MPN") "M74VHC1GT126DF1G"))
      (libsource (lib "eagle-import") (part "741G126DCKAHC"))
    )
    (comp (ref "IC14")
      (value "74AHC1G126DCK")
      (footprint "eagle-import:SC70-5")
      (fields (field (name "MPN") "M74VHC1GT126DF1G"))
      (libsource (lib "eagle-import") (part "741G126DCKAHC"))
    )
    (comp (ref "IC19")
      (value "TMC2100-LA")
      (footprint "eagle-import:QFN36-PAD")
      (fields (field (name "MPN") "TMC2100-LA-T"))
      (libsource (lib "eagle-import") (part "TMC2100-LA"))
    )
    (comp (ref "J503")
      (value "22-05-7048-04")
      (footprint "eagle-import:7395-04")
      (fields (field (name "MPN") "640455-4"))
      (libsource (lib "eagle-import") (part "22-?-0405-7048"))
    )
    (comp (ref "R31")
      (value "2.2R")
      (footprint "eagle-import:R0402")
      (fields (field (name "MPN") "RC1005J2R2CS"))
      (libsource (lib "eagle-import") (part "R-EU_R0402"))
    )
    (comp (ref "R32")
      (value "10K")
      (footprint "eagle-import:R0402")
      (fields (field (name "MPN") "RC0402FR-0710KL"))
      (libsource (lib "eagle-import") (part "R-EU_R0402"))
    )
    (comp (ref "R33")
      (value "10K")
      (footprint "eagle-import:R0402")
      (fields (field (name "MPN") "RC0402FR-0710KL"))
      (libsource (lib "eagle-import") (part "R-EU_R0402"))
    )
    (comp (ref "R34")
      (value "4.7K")
      (footprint "eagle-import:R0402")
      (fields (field (name "MPN") "RC0402JR-074K7L"))
      (libsource (lib "eagle-import") (part "R-EU_R0402"))
    )
    (comp (ref "R50")
      (value "0.1R")
      (footprint "eagle-import:R0805")
      (fields (field (name "MPN") "RL1220S-R10-F"))
      (libsource (lib "eagle-import") (part "R-EU_R0805"))
    )
    (comp (ref "R51")
      (value "0.1R")
      (footprint "eagle-import:R0805")
      (fields (field (name "MPN") "RL1220S-R10-F"))
      (libsource (lib "eagle-import") (part "R-EU_R0805"))
    )
    (comp (ref "U7")
      (value "SN74AHC595PW")
      (footprint "eagle-import:SOP65P640X120-16N")
      (fields (field (name "MPN") "MC74HC595ADTR2G"))
      (libsource (lib "eagle-import") (part "SN74AHC595PW"))
    )
    (comp (ref "C28")
      (value "0.1uF")
      (footprint "eagle-import:C0402")
      (fields (field (name "MPN") "CL10B104KB8NNND"))
      (libsource (lib "eagle-import") (part "C-EUC0402"))
    )
    (comp (ref "C29")
      (value "0.1uF")
      (footprint "eagle-import:C0402")
      (fields (field (name "MPN") "CL10B104KB8NNND"))
      (libsource (lib "eagle-import") (part "C-EUC0402"))
    )
    (comp (ref "C57")
      (value "22nF")
      (footprint "eagle-import:C0402")
      (fields (field (name "MPN") "C1005X7R1E223K050BB"))
      (libsource (lib "eagle-import") (part "C-EUC0402"))
    )
    (comp (ref "C58")
      (value "0.1uF")
      (footprint "eagle-import:C0402")
      (fields (field (name "MPN") "CL10B104KB8NNND"))
      (libsource (lib "eagle-import") (part "C-EUC0402"))
    )
    (comp (ref "C59")
      (value "4.7uF")
      (footprint "eagle-import:C0402")
      (fields (field (name "MPN") "GRM155R60J475ME47D"))
      (libsource (lib "eagle-import") (part "C-EUC0402"))
    )
    (comp (ref "C60")
      (value "4.7uF")
      (footprint "eagle-import:C0402")
      (fields (field (name "MPN") "GRM155R60J475ME47D"))
      (libsource (lib "eagle-import") (part "C-EUC0402"))
    )
    (comp (ref "C61")
      (value "4.7uF")
      (footprint "eagle-import:C0402")
      (fields (field (name "MPN") "GRM155R60J475ME47D"))
      (libsource (lib "eagle-import") (part "C-EUC0402"))
    )
    (comp (ref "C62")
      (value "0.1uF")
      (footprint "eagle-import:C0402")
      (fields (field (name "MPN") "CL10B104KB8NNND"))
      (libsource (lib "eagle-import") (part "C-EUC0402"))
    )
    (comp (ref "C72")
      (value "0.1uF")
      (footprint "eagle-import:C0402")
      (fields (field (name "MPN") "CL10B104KB8NNND"))
      (libsource (lib "eagle-import") (part "C-EUC0402"))
    )
    (comp (ref "C73")
      (value "0.1uF")
      (footprint "eagle-import:C0402")
      (fields (field (name "MPN") "CL10B104KB8NNND"))
      (libsource (lib "eagle-import") (part "C-EUC0402"))
    )
    (comp (ref "C78")
      (value "0.1uF")
      (footprint "eagle-import:C0402")
      (fields (field (name "MPN") "CL10B104KB8NNND"))
      (libsource (lib "eagle-import") (part "C-EUC0402"))
    )
    (comp (ref "C83")
      (value "100uF")
      (footprint "eagle-import:RHS1V10MCN1GS")
      (fields (field (name "MPN") "RHS1V101MCN1GS"))
      (libsource (lib "eagle-import") (part "C"))
    )
    (comp (ref "C88")
      (value "0.1uF")
      (footprint "eagle-import:C0402")
      (fields (field (name "MPN") "CL10B104KB8NNND"))
      (libsource (lib "eagle-import") (part "C-EUC0402"))
    )
    (comp (ref "C93")
      (value "10uF")
      (footprint "eagle-import:C0805")
      (fields (field (name "MPN") "C2012X5R1V106M085AC"))
      (libsource (lib "eagle-import") (part "C-EUC0805"))
    )
    (comp (ref "IC7")
      (value "74AHC1G126DCK")
      (footprint "eagle-import:SC70-5")
      (fields (field (name "MPN") "M74VHC1GT126DF1G"))
      (libsource (lib "eagle-import") (part "741G126DCKAHC"))
    )
    (comp (ref "IC12")
      (value "74AHC1G126DCK")
      (footprint "eagle-import:SC70-5")
      (fields (field (name "MPN") "M74VHC1GT126DF1G"))
      (libsource (lib "eagle-import") (part "741G126DCKAHC"))
    )
    (comp (ref "IC17")
      (value "74AHC1G126DCK")
      (footprint "eagle-import:SC70-5")
      (fields (field (name "MPN") "M74VHC1GT126DF1G"))
      (libsource (lib "eagle-import") (part "741G126DCKAHC"))
    )
    (comp (ref "IC22")
      (value "TMC2100-LA")
      (footprint "eagle-import:QFN36-PAD")
      (fields (field (name "MPN") "TMC2100-LA-T"))
      (libsource (lib "eagle-import") (part "TMC2100-LA"))
    )
    (comp (ref "J500")
      (value "22-05-7048-04")
      (footprint "eagle-import:7395-04")
      (fields (field (name "MPN") "640455-4"))
      (libsource (lib "eagle-import") (part "22-?-0405-7048"))
    )
    (comp (ref "R43")
      (value "2.2R")
      (footprint "eagle-import:R0402")
      (fields (field (name "MPN") "RC1005J2R2CS"))
      (libsource (lib "eagle-import") (part "R-EU_R0402"))
    )
    (comp (ref "R44")
      (value "10K")
      (footprint "eagle-import:R0402")
      (fields (field (name "MPN") "RC0402FR-0710KL"))
      (libsource (lib "eagle-import") (part "R-EU_R0402"))
    )
    (comp (ref "R45")
      (value "10K")
      (footprint "eagle-import:R0402")
      (fields (field (name "MPN") "RC0402FR-0710KL"))
      (libsource (lib "eagle-import") (part "R-EU_R0402"))
    )
    (comp (ref "R46")
      (value "4.7K")
      (footprint "eagle-import:R0402")
      (fields (field (name "MPN") "RC0402JR-074K7L"))
      (libsource (lib "eagle-import") (part "R-EU_R0402"))
    )
    (comp (ref "R56")
      (value "0.1R")
      (footprint "eagle-import:R0805")
      (fields (field (name "MPN") "RL1220S-R10-F"))
      (libsource (lib "eagle-import") (part "R-EU_R0805"))
    )
    (comp (ref "R57")
      (value "0.1R")
      (footprint "eagle-import:R0805")
      (fields (field (name "MPN") "RL1220S-R10-F"))
      (libsource (lib "eagle-import") (part "R-EU_R0805"))
    )
    (comp (ref "U10")
      (value "SN74AHC595PW")
      (footprint "eagle-import:SOP65P640X120-16N")
      (fields (field (name "MPN") "MC74HC595ADTR2G"))
      (libsource (lib "eagle-import") (part "SN74AHC595PW"))
    )
    (comp (ref "3.3V")
      (value "TPB1,27")
      (footprint "eagle-import:B1,27")
      (libsource (lib "eagle-import") (part "TPB1,27"))
    )
    (comp (ref "5V")
      (value "TPB1,27")
      (footprint "eagle-import:B1,27")
      (libsource (lib "eagle-import") (part "TPB1,27"))
    )
    (comp (ref "12..24V")
      (value "TPB1,27")
      (footprint "eagle-import:B1,27")
      (libsource (lib "eagle-import") (part "TPB1,27"))
    )
    (comp (ref "12V")
      (value "TPB1,27")
      (footprint "eagle-import:B1,27")
      (libsource (lib "eagle-import") (part "TPB1,27"))
    )
    (comp (ref "C1")
      (value "10uF")
      (footprint "eagle-import:C1206")
      (fields (field (name "MPN") "CL31B106KAHNNNE"))
      (libsource (lib "eagle-import") (part "C-EUC1206"))
    )
    (comp (ref "C2")
      (value "10uF")
      (footprint "eagle-import:C1206")
      (fields (field (name "MPN") "CL31B106KAHNNNE"))
      (libsource (lib "eagle-import") (part "C-EUC1206"))
    )
    (comp (ref "C3")
      (value "4.7nF")
      (footprint "eagle-import:C0402")
      (fields (field (name "MPN") "CL05B472KA5NNNC"))
      (libsource (lib "eagle-import") (part "C-EUC0402"))
    )
    (comp (ref "C4")
      (value "4.7uF")
      (footprint "eagle-import:C0402")
      (fields (field (name "MPN") "GRM155R60J475ME47D"))
      (libsource (lib "eagle-import") (part "C-EUC0402"))
    )
    (comp (ref "C5")
      (value "4.7uF")
      (footprint "eagle-import:C0402")
      (fields (field (name "MPN") "GRM155R60J475ME47D"))
      (libsource (lib "eagle-import") (part "C-EUC0402"))
    )
    (comp (ref "C6")
      (value "4.7uF")
      (footprint "eagle-import:C0402")
      (fields (field (name "MPN") "GRM155R60J475ME47D"))
      (libsource (lib "eagle-import") (part "C-EUC0402"))
    )
    (comp (ref "C7")
      (value "0.1uF")
      (footprint "eagle-import:C0402")
      (fields (field (name "MPN") "CL10B104KB8NNND"))
      (libsource (lib "eagle-import") (part "C-EUC0402"))
    )
    (comp (ref "C8")
      (value "0.1uF")
      (footprint "eagle-import:C0402")
      (fields (field (name "MPN") "CL10B104KB8NNND"))
      (libsource (lib "eagle-import") (part "C-EUC0402"))
    )
    (comp (ref "C9")
      (value "10uF")
      (footprint "eagle-import:C1206")
      (fields (field (name "MPN") "CL31B106KAHNNNE"))
      (libsource (lib "eagle-import") (part "C-EUC1206"))
    )
    (comp (ref "C10")
      (value "10uF")
      (footprint "eagle-import:C1206")
      (fields (field (name "MPN") "CL31B106KAHNNNE"))
      (libsource (lib "eagle-import") (part "C-EUC1206"))
    )
    (comp (ref "C11")
      (value "10uF")
      (footprint "eagle-import:C1206")
      (fields (field (name "MPN") "CL31B106KAHNNNE"))
      (libsource (lib "eagle-import") (part "C-EUC1206"))
    )
    (comp (ref "C12")
      (value "0.1uF")
      (footprint "eagle-import:C0402")
      (fields (field (name "MPN") "CL10B104KB8NNND"))
      (libsource (lib "eagle-import") (part "C-EUC0402"))
    )
    (comp (ref "C13")
      (value "10uF")
      (footprint "eagle-import:C1206")
      (fields (field (name "MPN") "CL31B106KAHNNNE"))
      (libsource (lib "eagle-import") (part "C-EUC1206"))
    )
    (comp (ref "C14")
      (value "1nF")
      (footprint "eagle-import:C0402")
      (fields (field (name "MPN") "C1005X7R1H102K050BA"))
      (libsource (lib "eagle-import") (part "C-EUC0402"))
    )
    (comp (ref "C15")
      (value "10nF")
      (footprint "eagle-import:C0402")
      (fields (field (name "MPN") "CL05B103KB5NNNC"))
      (libsource (lib "eagle-import") (part "C-EUC0402"))
    )
    (comp (ref "C16")
      (value "10nF")
      (footprint "eagle-import:C0402")
      (fields (field (name "MPN") "CL05B103KB5NNNC"))
      (libsource (lib "eagle-import") (part "C-EUC0402"))
    )
    (comp (ref "C17")
      (value "1nF")
      (footprint "eagle-import:C0402")
      (fields (field (name "MPN") "C1005X7R1H102K050BA"))
      (libsource (lib "eagle-import") (part "C-EUC0402"))
    )
    (comp (ref "C18")
      (value "0.1uF")
      (footprint "eagle-import:C0402")
      (fields (field (name "MPN") "CL10B104KB8NNND"))
      (libsource (lib "eagle-import") (part "C-EUC0402"))
    )
    (comp (ref "C19")
      (value "0.1uF")
      (footprint "eagle-import:C0402")
      (fields (field (name "MPN") "CL10B104KB8NNND"))
      (libsource (lib "eagle-import") (part "C-EUC0402"))
    )
    (comp (ref "C20")
      (value "10nF")
      (footprint "eagle-import:C0402")
      (fields (field (name "MPN") "CL05B103KB5NNNC"))
      (libsource (lib "eagle-import") (part "C-EUC0402"))
    )
    (comp (ref "C21")
      (value "10nF")
      (footprint "eagle-import:C0402")
      (fields (field (name "MPN") "CL05B103KB5NNNC"))
      (libsource (lib "eagle-import") (part "C-EUC0402"))
    )
    (comp (ref "C32")
      (value "4.7nF")
      (footprint "eagle-import:C0402")
      (fields (field (name "MPN") "CL05B472KA5NNNC"))
      (libsource (lib "eagle-import") (part "C-EUC0402"))
    )
    (comp (ref "C63")
      (value "4.7nF")
      (footprint "eagle-import:C0402")
      (fields (field (name "MPN") "CL05B472KA5NNNC"))
      (libsource (lib "eagle-import") (part "C-EUC0402"))
    )
    (comp (ref "D1")
      (value "MBRA340T3")
      (footprint "eagle-import:SMA")
      (fields (field (name "MPN") "MBRA340T3G"))
      (libsource (lib "eagle-import") (part "MBRA340T3"))
    )
    (comp (ref "D2")
      (value "MBRA340T3")
      (footprint "eagle-import:SMA")
      (fields (field (name "MPN") "MBRA340T3G"))
      (libsource (lib "eagle-import") (part "MBRA340T3"))
    )
    (comp (ref "D3")
      (value "MBRA340T3")
      (footprint "eagle-import:SMA")
      (fields (field (name "MPN") "MBRA340T3G"))
      (libsource (lib "eagle-import") (part "MBRA340T3"))
    )
    (comp (ref "D4")
      (value "MBRA340T3")
      (footprint "eagle-import:SMA")
      (fields (field (name "MPN") "MBRA340T3G"))
      (libsource (lib "eagle-import") (part "MBRA340T3"))
    )
    (comp (ref "D5")
      (value "MBRA340T3")
      (footprint "eagle-import:SMA")
      (fields (field (name "MPN") "MBRA340T3G"))
      (libsource (lib "eagle-import") (part "MBRA340T3"))
    )
    (comp (ref "D6")
      (value "MBRA340T3")
      (footprint "eagle-import:SMA")
      (fields (field (name "MPN") "MBRA340T3G"))
      (libsource (lib "eagle-import") (part "MBRA340T3"))
    )
    (comp (ref "F1")
      (value "FUSE")
      (footprint "eagle-import:3557")
      (fields (field (name "MPN") "0891020.NXS"))
      (libsource (lib "eagle-import") (part "FUSE"))
    )
    (comp (ref "FH1")
      (value "FUSE-HOLDER")
      (footprint "eagle-import:FUSE-HOLDER")
      (fields (field (name "MPN") "3557"))
      (libsource (lib "eagle-import") (part "FUSE-HOLDER"))
    )
    (comp (ref "FH2")
      (value "FUSE-HOLDER")
      (footprint "eagle-import:FUSE-HOLDER")
      (fields (field (name "MPN") "3557"))
      (libsource (lib "eagle-import") (part "FUSE-HOLDER"))
    )
    (comp (ref "IC1")
      (value "74AHC1G126DCK")
      (footprint "eagle-import:SC70-5")
      (fields (field (name "MPN") "M74VHC1GT126DF1G"))
      (libsource (lib "eagle-import") (part "741G126DCKAHC"))
    )
    (comp (ref "IC2")
      (value "74AHC1G126DCK")
      (footprint "eagle-import:SC70-5")
      (fields (field (name "MPN") "M74VHC1GT126DF1G"))
      (libsource (lib "eagle-import") (part "741G126DCKAHC"))
    )
    (comp (ref "JP1")
      (value "FIDUCIAL1X2.5")
      (footprint "eagle-import:FIDUCIAL-1X2.5")
      (libsource (lib "eagle-import") (part "FIDUCIAL1X2.5"))
    )
    (comp (ref "JP2")
      (value "FIDUCIAL1X2.5")
      (footprint "eagle-import:FIDUCIAL-1X2.5")
      (libsource (lib "eagle-import") (part "FIDUCIAL1X2.5"))
    )
    (comp (ref "L1")
      (value "33uH")
      (footprint "eagle-import:NR8040T330")
      (fields (field (name "MPN") "NR8040T330M"))
      (libsource (lib "eagle-import") (part "RT8040T330"))
    )
    (comp (ref "L2")
      (value "33uH")
      (footprint "eagle-import:NR8040T330")
      (fields (field (name "MPN") "NR8040T330M"))
      (libsource (lib "eagle-import") (part "RT8040T330"))
    )
    (comp (ref "LED1")
      (value "blue")
      (footprint "eagle-import:CHIP-LED0603")
      (fields (field (name "MPN") "Q65110A7211"))
      (libsource (lib "eagle-import") (part "LEDCHIP-LED0603"))
    )
    (comp (ref "LED2")
      (value "blue")
      (footprint "eagle-import:CHIP-LED0603")
      (fields (field (name "MPN") "Q65110A7211"))
      (libsource (lib "eagle-import") (part "LEDCHIP-LED0603"))
    )
    (comp (ref "LED3")
      (value "blue")
      (footprint "eagle-import:CHIP-LED0603")
      (fields (field (name "MPN") "Q65110A7211"))
      (libsource (lib "eagle-import") (part "LEDCHIP-LED0603"))
    )
    (comp (ref "LED4")
      (value "blue")
      (footprint "eagle-import:CHIP-LED0603")
      (fields (field (name "MPN") "Q65110A7211"))
      (libsource (lib "eagle-import") (part "LEDCHIP-LED0603"))
    )
    (comp (ref "LED5")
      (value "blue")
      (footprint "eagle-import:CHIP-LED0603")
      (fields (field (name "MPN") "Q65110A7211"))
      (libsource (lib "eagle-import") (part "LEDCHIP-LED0603"))
    )
    (comp (ref "LED6")
      (value "blue")
      (footprint "eagle-import:CHIP-LED0603")
      (fields (field (name "MPN") "Q65110A7211"))
      (libsource (lib "eagle-import") (part "LEDCHIP-LED0603"))
    )
    (comp (ref "LED7")
      (value "blue")
      (footprint "eagle-import:CHIP-LED0603")
      (fields (field (name "MPN") "Q65110A7211"))
      (libsource (lib "eagle-import") (part "LEDCHIP-LED0603"))
    )
    (comp (ref "LOGO1")
      (value "OSHW_LOGO_FILLX0200-NT")
      (footprint "eagle-import:OSHW_FILLX200_NOTEXT")
      (libsource (lib "eagle-import") (part "OSHW_LOGO_FILLX0200-NT"))
    )
    (comp (ref "P1")
      (value "F-2X23-")
      (footprint "eagle-import:DIL-100-2X23")
      (fields (field (name "MPN") "SSHQ-123-D-08-F-LF"))
      (libsource (lib "eagle-import") (part "F-2X23-"))
    )
    (comp (ref "P2")
      (value "F-2X23-")
      (footprint "eagle-import:DIL-100-2X23")
      (fields (field (name "MPN") "SSHQ-123-D-08-F-LF"))
      (libsource (lib "eagle-import") (part "F-2X23-"))
    )
    (comp (ref "Q1")
      (value "AON6758")
      (footprint "eagle-import:8-DFN-EP-(5X6)")
      (fields (field (name "MPN") "SIRA34DP-T1-GE3"))
      (libsource (lib "eagle-import") (part "AON6758"))
    )
    (comp (ref "Q2")
      (value "AON6758")
      (footprint "eagle-import:8-DFN-EP-(5X6)")
      (fields (field (name "MPN") "SIRA34DP-T1-GE3"))
      (libsource (lib "eagle-import") (part "AON6758"))
    )
    (comp (ref "Q3")
      (value "AON6758")
      (footprint "eagle-import:8-DFN-EP-(5X6)")
      (fields (field (name "MPN") "SIRA34DP-T1-GE3"))
      (libsource (lib "eagle-import") (part "AON6758"))
    )
    (comp (ref "Q4")
      (value "NPN-TRANSISTOR_SOT23")
      (footprint "eagle-import:SOT23")
      (fields (field (name "MPN") "AO7400"))
      (libsource (lib "eagle-import") (part "NPN-TRANSISTOR_SOT23"))
    )
    (comp (ref "Q5")
      (value "NPN-TRANSISTOR_SOT23")
      (footprint "eagle-import:SOT23")
      (fields (field (name "MPN") "AO7400"))
      (libsource (lib "eagle-import") (part "NPN-TRANSISTOR_SOT23"))
    )
    (comp (ref "R1")
      (value "4.7K")
      (footprint "eagle-import:R0402")
      (fields (field (name "MPN") "RC0402JR-074K7L"))
      (libsource (lib "eagle-import") (part "R-EU_R0402"))
    )
    (comp (ref "R2")
      (value "4.7K")
      (footprint "eagle-import:R0402")
      (fields (field (name "MPN") "RC0402JR-074K7L"))
      (libsource (lib "eagle-import") (part "R-EU_R0402"))
    )
    (comp (ref "R3")
      (value "4.7K")
      (footprint "eagle-import:R0402")
      (fields (field (name "MPN") "RC0402JR-074K7L"))
      (libsource (lib "eagle-import") (part "R-EU_R0402"))
    )
    (comp (ref "R4")
      (value "4.7K")
      (footprint "eagle-import:R0402")
      (fields (field (name "MPN") "RC0402JR-074K7L"))
      (libsource (lib "eagle-import") (part "R-EU_R0402"))
    )
    (comp (ref "R5")
      (value "4.7K")
      (footprint "eagle-import:R0402")
      (fields (field (name "MPN") "RC0402JR-074K7L"))
      (libsource (lib "eagle-import") (part "R-EU_R0402"))
    )
    (comp (ref "R6")
      (value "4.7K")
      (footprint "eagle-import:R0402")
      (fields (field (name "MPN") "RC0402JR-074K7L"))
      (libsource (lib "eagle-import") (part "R-EU_R0402"))
    )
    (comp (ref "R7")
      (value "4.7K")
      (footprint "eagle-import:R0402")
      (fields (field (name "MPN") "RC0402JR-074K7L"))
      (libsource (lib "eagle-import") (part "R-EU_R0402"))
    )
    (comp (ref "R8")
      (value "4.7K")
      (footprint "eagle-import:R0402")
      (fields (field (name "MPN") "RC0402JR-074K7L"))
      (libsource (lib "eagle-import") (part "R-EU_R0402"))
    )
    (comp (ref "R9")
      (value "4K7, 1%")
      (footprint "eagle-import:R0402")
      (fields (field (name "MPN") "RC0402FR-074K7L"))
      (libsource (lib "eagle-import") (part "R-EU_R0402"))
    )
    (comp (ref "R10")
      (value "10K")
      (footprint "eagle-import:R0402")
      (fields (field (name "MPN") "RC0402FR-0710KL"))
      (libsource (lib "eagle-import") (part "R-EU_R0402"))
    )
    (comp (ref "R11")
      (value "10K")
      (footprint "eagle-import:R0402")
      (fields (field (name "MPN") "RC0402FR-0710KL"))
      (libsource (lib "eagle-import") (part "R-EU_R0402"))
    )
    (comp (ref "R12")
      (value "4K7, 1%")
      (footprint "eagle-import:R0402")
      (fields (field (name "MPN") "RC0402FR-074K7L"))
      (libsource (lib "eagle-import") (part "R-EU_R0402"))
    )
    (comp (ref "R13")
      (value "4K7, 1%")
      (footprint "eagle-import:R0402")
      (fields (field (name "MPN") "RC0402FR-074K7L"))
      (libsource (lib "eagle-import") (part "R-EU_R0402"))
    )
    (comp (ref "R14")
      (value "10K")
      (footprint "eagle-import:R0402")
      (fields (field (name "MPN") "RC0402FR-0710KL"))
      (libsource (lib "eagle-import") (part "R-EU_R0402"))
    )
    (comp (ref "R15")
      (value "4.7K")
      (footprint "eagle-import:R0402")
      (fields (field (name "MPN") "RC0402JR-074K7L"))
      (libsource (lib "eagle-import") (part "R-EU_R0402"))
    )
    (comp (ref "R16")
      (value "10K,1%")
      (footprint "eagle-import:R0402")
      (fields (field (name "MPN") "RC0402FR-0710KL"))
      (libsource (lib "eagle-import") (part "R-EU_R0402"))
    )
    (comp (ref "R17")
      (value "44.3K,1%")
      (footprint "eagle-import:R0402")
      (fields (field (name "MPN") "RC1005F4422CS"))
      (libsource (lib "eagle-import") (part "R-EU_R0402"))
    )
    (comp (ref "R18")
      (value "10K,1%")
      (footprint "eagle-import:R0402")
      (fields (field (name "MPN") "RC0402FR-0710KL"))
      (libsource (lib "eagle-import") (part "R-EU_R0402"))
    )
    (comp (ref "R19")
      (value "120K,1%")
      (footprint "eagle-import:R0402")
      (fields (field (name "MPN") "RMCF0402FT120K"))
      (libsource (lib "eagle-import") (part "R-EU_R0402"))
    )
    (comp (ref "R20")
      (value "39K")
      (footprint "eagle-import:R0402")
      (fields (field (name "MPN") "RC1005J393CS"))
      (libsource (lib "eagle-import") (part "R-EU_R0402"))
    )
    (comp (ref "R21")
      (value "4.7K")
      (footprint "eagle-import:R0402")
      (fields (field (name "MPN") "RC0402JR-074K7L"))
      (libsource (lib "eagle-import") (part "R-EU_R0402"))
    )
    (comp (ref "R22")
      (value "4.7K")
      (footprint "eagle-import:R0402")
      (fields (field (name "MPN") "RC0402JR-074K7L"))
      (libsource (lib "eagle-import") (part "R-EU_R0402"))
    )
    (comp (ref "R23")
      (value "39K")
      (footprint "eagle-import:R0402")
      (fields (field (name "MPN") "RC1005J393CS"))
      (libsource (lib "eagle-import") (part "R-EU_R0402"))
    )
    (comp (ref "R24")
      (value "4.7K")
      (footprint "eagle-import:R0402")
      (fields (field (name "MPN") "RC0402JR-074K7L"))
      (libsource (lib "eagle-import") (part "R-EU_R0402"))
    )
    (comp (ref "R25")
      (value "4.7K")
      (footprint "eagle-import:R0402")
      (fields (field (name "MPN") "RC0402JR-074K7L"))
      (libsource (lib "eagle-import") (part "R-EU_R0402"))
    )
    (comp (ref "R26")
      (value "4.7K")
      (footprint "eagle-import:R0402")
      (fields (field (name "MPN") "RC0402JR-074K7L"))
      (libsource (lib "eagle-import") (part "R-EU_R0402"))
    )
    (comp (ref "R47")
      (value "4.7K")
      (footprint "eagle-import:R0402")
      (fields (field (name "MPN") "RC0402JR-074K7L"))
      (libsource (lib "eagle-import") (part "R-EU_R0402"))
    )
    (comp (ref "R58")
      (value "4.7K")
      (footprint "eagle-import:R0402")
      (fields (field (name "MPN") "RC0402JR-074K7L"))
      (libsource (lib "eagle-import") (part "R-EU_R0402"))
    )
    (comp (ref "R59")
      (value "4.7K")
      (footprint "eagle-import:R0402")
      (fields (field (name "MPN") "RC0402JR-074K7L"))
      (libsource (lib "eagle-import") (part "R-EU_R0402"))
    )
    (comp (ref "R60")
      (value "4.7K")
      (footprint "eagle-import:R0402")
      (fields (field (name "MPN") "RC0402JR-074K7L"))
      (libsource (lib "eagle-import") (part "R-EU_R0402"))
    )
    (comp (ref "R61")
      (value "4.7K")
      (footprint "eagle-import:R0402")
      (fields (field (name "MPN") "RC0402JR-074K7L"))
      (libsource (lib "eagle-import") (part "R-EU_R0402"))
    )
    (comp (ref "R62")
      (value "4.7K")
      (footprint "eagle-import:R0402")
      (fields (field (name "MPN") "RC0402JR-074K7L"))
      (libsource (lib "eagle-import") (part "R-EU_R0402"))
    )
    (comp (ref "R63")
      (value "4.7K")
      (footprint "eagle-import:R0402")
      (fields (field (name "MPN") "RC0402JR-074K7L"))
      (libsource (lib "eagle-import") (part "R-EU_R0402"))
    )
    (comp (ref "R64")
      (value "4.7K")
      (footprint "eagle-import:R0402")
      (fields (field (name "MPN") "RC0402JR-074K7L"))
      (libsource (lib "eagle-import") (part "R-EU_R0402"))
    )
    (comp (ref "SV1")
      (value "MA03-1")
      (footprint "eagle-import:MA03-1")
      (libsource (lib "eagle-import") (part "MA03-1"))
    )
    (comp (ref "U$1")
      (value "CC-BY-SA")
      (footprint "eagle-import:CC-BY-SA")
      (libsource (lib "eagle-import") (part "CC-BY-SA"))
    )
    (comp (ref "U1")
      (value "PCA9685PW")
      (footprint "eagle-import:SOP65P640X110-28N")
      (fields (field (name "MPN") "PCA9685PW,112"))
      (libsource (lib "eagle-import") (part "PCA9685PW"))
    )
    (comp (ref "U2")
      (value "CAT24C256")
      (footprint "eagle-import:SOIC127P600X175-8N")
      (fields (field (name "MPN") "CAT24C256WI-GT3"))
      (libsource (lib "eagle-import") (part "CAT24C256"))
    )
    (comp (ref "U3")
      (value "CD4050BD")
      (footprint "eagle-import:SOIC127P600X175-16N")
      (fields (field (name "MPN") "CD4050BDR"))
      (libsource (lib "eagle-import") (part "CD4050BD"))
    )
    (comp (ref "U4")
      (value "RT8268")
      (footprint "eagle-import:MSOP10")
      (fields (field (name "MPN") "RT8268GFP"))
      (libsource (lib "eagle-import") (part "RT8268"))
    )
    (comp (ref "U5")
      (value "RT8268")
      (footprint "eagle-import:MSOP10")
      (fields (field (name "MPN") "RT8268GFP"))
      (libsource (lib "eagle-import") (part "RT8268"))
    )
    (comp (ref "X1")
      (value "22-05-7038-03")
      (footprint "eagle-import:7395-03")
      (fields (field (name "MPN") "640455-3"))
      (libsource (lib "eagle-import") (part "22-?-0305-7038"))
    )
    (comp (ref "X2")
      (value "22-05-7028-02")
      (footprint "eagle-import:7395-02")
      (fields (field (name "MPN") "640455-2"))
      (libsource (lib "eagle-import") (part "22-?-0205-7028"))
    )
    (comp (ref "X3")
      (value "22-05-7028-02")
      (footprint "eagle-import:7395-02")
      (fields (field (name "MPN") "640455-2"))
      (libsource (lib "eagle-import") (part "22-?-0205-7028"))
    )
    (comp (ref "X4")
      (value "22-05-7028-02")
      (footprint "eagle-import:7395-02")
      (fields (field (name "MPN") "640455-2"))
      (libsource (lib "eagle-import") (part "22-?-0205-7028"))
    )
    (comp (ref "X5")
      (value "22-05-7038-03")
      (footprint "eagle-import:7395-03")
      (fields (field (name "MPN") "640455-3"))
      (libsource (lib "eagle-import") (part "22-?-0305-7038"))
    )
    (comp (ref "X6")
      (value "22-05-7038-03")
      (footprint "eagle-import:7395-03")
      (fields (field (name "MPN") "640455-3"))
      (libsource (lib "eagle-import") (part "22-?-0305-7038"))
    )
    (comp (ref "X7")
      (value "22-05-7038-03")
      (footprint "eagle-import:7395-03")
      (fields (field (name "MPN") "640455-3"))
      (libsource (lib "eagle-import") (part "22-?-0305-7038"))
    )
    (comp (ref "X8")
      (value "22-05-7038-03")
      (footprint "eagle-import:7395-03")
      (fields (field (name "MPN") "640455-3"))
      (libsource (lib "eagle-import") (part "22-?-0305-7038"))
    )
    (comp (ref "X9")
      (value "22-05-7038-03")
      (footprint "eagle-import:7395-03")
      (fields (field (name "MPN") "640455-3"))
      (libsource (lib "eagle-import") (part "22-?-0305-7038"))
    )
    (comp (ref "X10")
      (value "22-05-7048-04")
      (footprint "eagle-import:7395-04")
      (fields (field (name "MPN") "640455-4"))
      (libsource (lib "eagle-import") (part "22-?-0405-7048"))
    )
    (comp (ref "X11")
      (value "MSTBA2")
      (footprint "eagle-import:MSTBA2")
      (fields
        (field (name "MF") "FARNELL")
        (field (name "MPN") "1757242")
        (field (name "MPN_1") "39532-1002")
      )
      (libsource (lib "eagle-import") (part "MSTBA2"))
    )
    (comp (ref "X12")
      (value "MSTBA4")
      (footprint "eagle-import:MSTBA4")
      (fields
        (field (name "MF") "FARNELL")
        (field (name "MPN") "1757268")
        (field (name "MPN_1") "39532-1004")
      )
      (libsource (lib "eagle-import") (part "MSTBA4"))
    )
    (comp (ref "X13")
      (value "MSTBA2")
      (footprint "eagle-import:MSTBA2")
      (fields
        (field (name "MF") "FARNELL")
        (field (name "MPN") "1757242")
        (field (name "MPN_1") "39532-1002")
      )
      (libsource (lib "eagle-import") (part "MSTBA2"))
    )
    (comp (ref "X14")
      (value "MSTBA4")
      (footprint "eagle-import:MSTBA4")
      (fields
        (field (name "MF") "FARNELL")
        (field (name "MPN") "1757268")
        (field (name "MPN_1") "39532-1004")
      )
      (libsource (lib "eagle-import") (part "MSTBA4"))
    )
    (comp (ref "X15")
      (value "22-05-7028-02")
      (footprint "eagle-import:7395-02")
      (fields (field (name "MPN") "640455-2"))
      (libsource (lib "eagle-import") (part "22-?-0205-7028"))
    )
    (comp (ref "X16")
      (value "22-05-7028-02")
      (footprint "eagle-import:7395-02")
      (fields (field (name "MPN") "640455-2"))
      (libsource (lib "eagle-import") (part "22-?-0205-7028"))
    )
    (comp (ref "XC1")
      (value "MSTBV2-CONNECTOR")
      (footprint "eagle-import:MSTBA2-CONNECTOR")
      (fields (field (name "MPN") "39530-0002"))
      (libsource (lib "eagle-import") (part "MSTBV2-CONNECTOR"))
    )
    (comp (ref "XC2")
      (value "MSTBA4-CONNECTOR")
      (footprint "eagle-import:MSTBA4-CONNECTOR")
      (fields (field (name "MPN") "39530-0004"))
      (libsource (lib "eagle-import") (part "MSTBA4-CONNECTOR"))
    )
    (comp (ref "XC3")
      (value "MSTBV2-CONNECTOR")
      (footprint "eagle-import:MSTBA2-CONNECTOR")
      (fields (field (name "MPN") "39530-0002"))
      (libsource (lib "eagle-import") (part "MSTBV2-CONNECTOR"))
    )
    (comp (ref "XC4")
      (value "MSTBA4-CONNECTOR")
      (footprint "eagle-import:MSTBA4-CONNECTOR")
      (fields (field (name "MPN") "39530-0004"))
      (libsource (lib "eagle-import") (part "MSTBA4-CONNECTOR"))
    )
  )
  (nets
    (net (code "1") (name "+3V3") (class "Default")
      (node (ref "3.3V") (pin "TP") (pinfunction "TP_TP") (pintype "input"))
      (node (ref "C19") (pin "1") (pinfunction "1_1") (pintype "passive"))
      (node (ref "C22") (pin "1") (pinfunction "1_1") (pintype "passive"))
      (node (ref "C23") (pin "1") (pinfunction "1_1") (pintype "passive"))
      (node (ref "C24") (pin "1") (pinfunction "1_1") (pintype "passive"))
      (node (ref "C25") (pin "1") (pinfunction "1_1") (pintype "passive"))
      (node (ref "C26") (pin "1") (pinfunction "1_1") (pintype "passive"))
      (node (ref "C27") (pin "1") (pinfunction "1_1") (pintype "passive"))
      (node (ref "C28") (pin "1") (pinfunction "1_1") (pintype "passive"))
      (node (ref "C29") (pin "1") (pinfunction "1_1") (pintype "passive"))
      (node (ref "C30") (pin "1") (pinfunction "1_1") (pintype "passive"))
      (node (ref "C31") (pin "1") (pinfunction "1_1") (pintype "passive"))
      (node (ref "C38") (pin "1") (pinfunction "1_1") (pintype "passive"))
      (node (ref "C44") (pin "1") (pinfunction "1_1") (pintype "passive"))
      (node (ref "C50") (pin "1") (pinfunction "1_1") (pintype "passive"))
      (node (ref "C56") (pin "1") (pinfunction "1_1") (pintype "passive"))
      (node (ref "C62") (pin "1") (pinfunction "1_1") (pintype "passive"))
      (node (ref "C7") (pin "1") (pinfunction "1_1") (pintype "passive"))
      (node (ref "IC10") (pin "5") (pinfunction "VCC_5") (pintype "power_in"))
      (node (ref "IC11") (pin "5") (pinfunction "VCC_5") (pintype "power_in"))
      (node (ref "IC12") (pin "5") (pinfunction "VCC_5") (pintype "power_in"))
      (node (ref "IC13") (pin "5") (pinfunction "VCC_5") (pintype "power_in"))
      (node (ref "IC14") (pin "5") (pinfunction "VCC_5") (pintype "power_in"))
      (node (ref "IC15") (pin "5") (pinfunction "VCC_5") (pintype "power_in"))
      (node (ref "IC16") (pin "5") (pinfunction "VCC_5") (pintype "power_in"))
      (node (ref "IC17") (pin "5") (pinfunction "VCC_5") (pintype "power_in"))
      (node (ref "IC18") (pin "8") (pinfunction "VCC_IO_8") (pintype "bidirectional"))
      (node (ref "IC19") (pin "8") (pinfunction "VCC_IO_8") (pintype "bidirectional"))
      (node (ref "IC20") (pin "8") (pinfunction "VCC_IO_8") (pintype "bidirectional"))
      (node (ref "IC21") (pin "8") (pinfunction "VCC_IO_8") (pintype "bidirectional"))
      (node (ref "IC22") (pin "8") (pinfunction "VCC_IO_8") (pintype "bidirectional"))
      (node (ref "IC3") (pin "5") (pinfunction "VCC_5") (pintype "power_in"))
      (node (ref "IC4") (pin "5") (pinfunction "VCC_5") (pintype "power_in"))
      (node (ref "IC5") (pin "5") (pinfunction "VCC_5") (pintype "power_in"))
      (node (ref "IC6") (pin "5") (pinfunction "VCC_5") (pintype "power_in"))
      (node (ref "IC7") (pin "5") (pinfunction "VCC_5") (pintype "power_in"))
      (node (ref "IC8") (pin "5") (pinfunction "VCC_5") (pintype "power_in"))
      (node (ref "IC9") (pin "5") (pinfunction "VCC_5") (pintype "power_in"))
      (node (ref "P1") (pin "3") (pinfunction "3_3") (pintype "passive"))
      (node (ref "P1") (pin "4") (pinfunction "4_4") (pintype "passive"))
      (node (ref "R22") (pin "2") (pinfunction "2_2") (pintype "passive"))
      (node (ref "R30") (pin "2") (pinfunction "2_2") (pintype "passive"))
      (node (ref "R34") (pin "2") (pinfunction "2_2") (pintype "passive"))
      (node (ref "R38") (pin "2") (pinfunction "2_2") (pintype "passive"))
      (node (ref "R42") (pin "2") (pinfunction "2_2") (pintype "passive"))
      (node (ref "R46") (pin "2") (pinfunction "2_2") (pintype "passive"))
      (node (ref "U10") (pin "10") (pinfunction "~{SRCLR}_10") (pintype "input"))
      (node (ref "U10") (pin "16") (pinfunction "VCC_16") (pintype "power_in"))
      (node (ref "U2") (pin "3") (pinfunction "A2_3") (pintype "input"))
      (node (ref "U2") (pin "8") (pinfunction "VCC_8") (pintype "power_in"))
      (node (ref "U3") (pin "1") (pinfunction "VCC_1") (pintype "power_in"))
      (node (ref "U6") (pin "10") (pinfunction "~{SRCLR}_10") (pintype "input"))
      (node (ref "U6") (pin "16") (pinfunction "VCC_16") (pintype "power_in"))
      (node (ref "U7") (pin "10") (pinfunction "~{SRCLR}_10") (pintype "input"))
      (node (ref "U7") (pin "16") (pinfunction "VCC_16") (pintype "power_in"))
      (node (ref "U8") (pin "10") (pinfunction "~{SRCLR}_10") (pintype "input"))
      (node (ref "U8") (pin "16") (pinfunction "VCC_16") (pintype "power_in"))
      (node (ref "U9") (pin "10") (pinfunction "~{SRCLR}_10") (pintype "input"))
      (node (ref "U9") (pin "16") (pinfunction "VCC_16") (pintype "power_in"))
      (node (ref "X1") (pin "1") (pinfunction "S_1") (pintype "passive"))
    )
    (net (code "2") (name "DALLAS_W1") (class "Default")
      (node (ref "P1") (pin "22") (pinfunction "22_22") (pintype "passive"))
      (node (ref "X1") (pin "2") (pinfunction "S_2") (pintype "passive"))
    )
    (net (code "3") (name "DIR_E") (class "Default")
      (node (ref "IC21") (pin "7") (pinfunction "REFR_DIR_7") (pintype "bidirectional"))
      (node (ref "P2") (pin "15") (pinfunction "15_15") (pintype "passive"))
    )
    (net (code "4") (name "DIR_H") (class "Default")
      (node (ref "IC22") (pin "7") (pinfunction "REFR_DIR_7") (pintype "bidirectional"))
      (node (ref "P2") (pin "16") (pinfunction "16_16") (pintype "passive"))
    )
    (net (code "5") (name "DIR_X") (class "Default")
      (node (ref "IC18") (pin "7") (pinfunction "REFR_DIR_7") (pintype "bidirectional"))
      (node (ref "P2") (pin "26") (pinfunction "26_26") (pintype "passive"))
    )
    (net (code "6") (name "DIR_Y") (class "Default")
      (node (ref "IC19") (pin "7") (pinfunction "REFR_DIR_7") (pintype "bidirectional"))
      (node (ref "P2") (pin "19") (pinfunction "19_19") (pintype "passive"))
    )
    (net (code "7") (name "DIR_Z") (class "Default")
      (node (ref "IC20") (pin "7") (pinfunction "REFR_DIR_7") (pintype "bidirectional"))
      (node (ref "P2") (pin "14") (pinfunction "14_14") (pintype "passive"))
    )
    (net (code "8") (name "ENABLE") (class "Default")
      (node (ref "P1") (pin "41") (pinfunction "41_41") (pintype "passive"))
      (node (ref "R22") (pin "1") (pinfunction "1_1") (pintype "passive"))
      (node (ref "U1") (pin "23") (pinfunction "~{OE}_23") (pintype "input"))
    )
    (net (code "9") (name "ENABLE_E") (class "Default")
      (node (ref "IC21") (pin "22") (pinfunction "DRV_ENN_CFG6_22") (pintype "bidirectional"))
      (node (ref "IC6") (pin "4") (pinfunction "O_4") (pintype "output"))
    )
    (net (code "10") (name "ENABLE_H") (class "Default")
      (node (ref "IC22") (pin "22") (pinfunction "DRV_ENN_CFG6_22") (pintype "bidirectional"))
      (node (ref "IC7") (pin "4") (pinfunction "O_4") (pintype "output"))
    )
    (net (code "11") (name "ENABLE_X") (class "Default")
      (node (ref "IC18") (pin "22") (pinfunction "DRV_ENN_CFG6_22") (pintype "bidirectional"))
      (node (ref "IC3") (pin "4") (pinfunction "O_4") (pintype "output"))
    )
    (net (code "12") (name "ENABLE_Y") (class "Default")
      (node (ref "IC19") (pin "22") (pinfunction "DRV_ENN_CFG6_22") (pintype "bidirectional"))
      (node (ref "IC4") (pin "4") (pinfunction "O_4") (pintype "output"))
    )
    (net (code "13") (name "ENABLE_Z") (class "Default")
      (node (ref "IC20") (pin "22") (pinfunction "DRV_ENN_CFG6_22") (pintype "bidirectional"))
      (node (ref "IC5") (pin "4") (pinfunction "O_4") (pintype "output"))
    )
    (net (code "14") (name "END_STOP_X_1") (class "Default")
      (node (ref "P1") (pin "25") (pinfunction "25_25") (pintype "passive"))
      (node (ref "U3") (pin "2") (pinfunction "G=A_2") (pintype "output"))
    )
    (net (code "15") (name "END_STOP_X_1_IN") (class "Default")
      (node (ref "R1") (pin "1") (pinfunction "1_1") (pintype "passive"))
      (node (ref "U3") (pin "3") (pinfunction "A_3") (pintype "input"))
      (node (ref "X5") (pin "1") (pinfunction "S_1") (pintype "passive"))
    )
    (net (code "16") (name "END_STOP_X_2") (class "Default")
      (node (ref "P1") (pin "11") (pinfunction "11_11") (pintype "passive"))
      (node (ref "U3") (pin "10") (pinfunction "J=D_10") (pintype "output"))
    )
    (net (code "17") (name "END_STOP_X_2_IN") (class "Default")
      (node (ref "IC2") (pin "4") (pinfunction "O_4") (pintype "output"))
      (node (ref "R4") (pin "1") (pinfunction "1_1") (pintype "passive"))
      (node (ref "U3") (pin "9") (pinfunction "D_9") (pintype "input"))
      (node (ref "X8") (pin "1") (pinfunction "S_1") (pintype "passive"))
    )
    (net (code "18") (name "END_STOP_Y_1") (class "Default")
      (node (ref "P1") (pin "23") (pinfunction "23_23") (pintype "passive"))
      (node (ref "U3") (pin "4") (pinfunction "H=B_4") (pintype "output"))
    )
    (net (code "19") (name "END_STOP_Y_1_IN") (class "Default")
      (node (ref "R2") (pin "1") (pinfunction "1_1") (pintype "passive"))
      (node (ref "U3") (pin "5") (pinfunction "B_5") (pintype "input"))
      (node (ref "X6") (pin "1") (pinfunction "S_1") (pintype "passive"))
    )
    (net (code "20") (name "END_STOP_Y_2") (class "Default")
      (node (ref "P1") (pin "28") (pinfunction "28_28") (pintype "passive"))
      (node (ref "U3") (pin "12") (pinfunction "K=E_12") (pintype "output"))
    )
    (net (code "21") (name "END_STOP_Y_2_IN") (class "Default")
      (node (ref "IC1") (pin "4") (pinfunction "O_4") (pintype "output"))
      (node (ref "R5") (pin "1") (pinfunction "1_1") (pintype "passive"))
      (node (ref "U3") (pin "11") (pinfunction "E_11") (pintype "input"))
      (node (ref "X9") (pin "1") (pinfunction "S_1") (pintype "passive"))
    )
    (net (code "22") (name "END_STOP_Z_1") (class "Default")
      (node (ref "P1") (pin "13") (pinfunction "13_13") (pintype "passive"))
      (node (ref "U3") (pin "6") (pinfunction "I=C_6") (pintype "output"))
    )
    (net (code "23") (name "END_STOP_Z_1_IN") (class "Default")
      (node (ref "R3") (pin "1") (pinfunction "1_1") (pintype "passive"))
      (node (ref "U3") (pin "7") (pinfunction "C_7") (pintype "input"))
      (node (ref "X7") (pin "1") (pinfunction "S_1") (pintype "passive"))
    )
    (net (code "24") (name "END_STOP_Z_2") (class "Default")
      (node (ref "P1") (pin "18") (pinfunction "18_18") (pintype "passive"))
      (node (ref "U3") (pin "15") (pinfunction "L=F_15") (pintype "output"))
    )
    (net (code "25") (name "END_STOP_Z_2_IN") (class "Default")
      (node (ref "R6") (pin "1") (pinfunction "1_1") (pintype "passive"))
      (node (ref "U3") (pin "14") (pinfunction "F_14") (pintype "input"))
      (node (ref "X10") (pin "1") (pinfunction "S_1") (pintype "passive"))
    )
    (net (code "26") (name "EN_EH") (class "Default")
      (node (ref "IC6") (pin "2") (pinfunction "I_2") (pintype "input"))
      (node (ref "IC7") (pin "2") (pinfunction "I_2") (pintype "input"))
      (node (ref "U9") (pin "15") (pinfunction "QA_15") (pintype "output"))
    )
    (net (code "27") (name "EN_XYZ") (class "Default")
      (node (ref "IC3") (pin "2") (pinfunction "I_2") (pintype "input"))
      (node (ref "IC4") (pin "2") (pinfunction "I_2") (pintype "input"))
      (node (ref "IC5") (pin "2") (pinfunction "I_2") (pintype "input"))
      (node (ref "U6") (pin "15") (pinfunction "QA_15") (pintype "output"))
    )
    (net (code "28") (name "E_A1") (class "Default")
      (node (ref "IC21") (pin "34") (pinfunction "OA1_34") (pintype "bidirectional"))
      (node (ref "J501") (pin "2") (pinfunction "S_2") (pintype "passive"))
    )
    (net (code "29") (name "E_A2") (class "Default")
      (node (ref "IC21") (pin "32") (pinfunction "OA2_32") (pintype "bidirectional"))
      (node (ref "J501") (pin "1") (pinfunction "S_1") (pintype "passive"))
    )
    (net (code "30") (name "E_B1") (class "Default")
      (node (ref "IC21") (pin "13") (pinfunction "OB1_13") (pintype "bidirectional"))
      (node (ref "J501") (pin "3") (pinfunction "S_3") (pintype "passive"))
    )
    (net (code "31") (name "E_B2") (class "Default")
      (node (ref "IC21") (pin "15") (pinfunction "OB2_15") (pintype "bidirectional"))
      (node (ref "J501") (pin "4") (pinfunction "S_4") (pintype "passive"))
    )
    (net (code "32") (name "FAN2") (class "Default")
      (node (ref "Q4") (pin "1") (pinfunction "B_1") (pintype "passive"))
      (node (ref "R61") (pin "2") (pinfunction "2_2") (pintype "passive"))
      (node (ref "U1") (pin "16") (pinfunction "LED9_16") (pintype "output"))
    )
    (net (code "33") (name "FAN3") (class "Default")
      (node (ref "Q5") (pin "1") (pinfunction "B_1") (pintype "passive"))
      (node (ref "R60") (pin "2") (pinfunction "2_2") (pintype "passive"))
      (node (ref "U1") (pin "17") (pinfunction "LED10_17") (pintype "output"))
    )
    (net (code "34") (name "FAULT_E") (class "Default")
      (node (ref "IC21") (pin "20") (pinfunction "SWN_DIAG0_20") (pintype "bidirectional"))
      (node (ref "P2") (pin "18") (pinfunction "18_18") (pintype "passive"))
      (node (ref "R42") (pin "1") (pinfunction "1_1") (pintype "passive"))
    )
    (net (code "35") (name "FAULT_H") (class "Default")
      (node (ref "IC22") (pin "20") (pinfunction "SWN_DIAG0_20") (pintype "bidirectional"))
      (node (ref "P2") (pin "8") (pinfunction "8_8") (pintype "passive"))
      (node (ref "R46") (pin "1") (pinfunction "1_1") (pintype "passive"))
    )
    (net (code "36") (name "FAULT_X") (class "Default")
      (node (ref "IC18") (pin "20") (pinfunction "SWN_DIAG0_20") (pintype "bidirectional"))
      (node (ref "P2") (pin "10") (pinfunction "10_10") (pintype "passive"))
      (node (ref "R30") (pin "1") (pinfunction "1_1") (pintype "passive"))
    )
    (net (code "37") (name "FAULT_Y") (class "Default")
      (node (ref "IC19") (pin "20") (pinfunction "SWN_DIAG0_20") (pintype "bidirectional"))
      (node (ref "P2") (pin "9") (pinfunction "9_9") (pintype "passive"))
      (node (ref "R34") (pin "1") (pinfunction "1_1") (pintype "passive"))
    )
    (net (code "38") (name "FAULT_Z") (class "Default")
      (node (ref "IC20") (pin "20") (pinfunction "SWN_DIAG0_20") (pintype "bidirectional"))
      (node (ref "P1") (pin "24") (pinfunction "24_24") (pintype "passive"))
      (node (ref "R38") (pin "1") (pinfunction "1_1") (pintype "passive"))
    )
    (net (code "39") (name "GND") (class "Default")
      (node (ref "C1") (pin "2") (pinfunction "2_2") (pintype "passive"))
      (node (ref "C10") (pin "2") (pinfunction "2_2") (pintype "passive"))
      (node (ref "C11") (pin "2") (pinfunction "2_2") (pintype "passive"))
      (node (ref "C12") (pin "2") (pinfunction "2_2") (pintype "passive"))
      (node (ref "C13") (pin "2") (pinfunction "2_2") (pintype "passive"))
      (node (ref "C15") (pin "2") (pinfunction "2_2") (pintype "passive"))
      (node (ref "C18") (pin "2") (pinfunction "2_2") (pintype "passive"))
      (node (ref "C19") (pin "2") (pinfunction "2_2") (pintype "passive"))
      (node (ref "C2") (pin "2") (pinfunction "2_2") (pintype "passive"))
      (node (ref "C20") (pin "2") (pinfunction "2_2") (pintype "passive"))
      (node (ref "C22") (pin "2") (pinfunction "2_2") (pintype "passive"))
      (node (ref "C23") (pin "2") (pinfunction "2_2") (pintype "passive"))
      (node (ref "C24") (pin "2") (pinfunction "2_2") (pintype "passive"))
      (node (ref "C25") (pin "2") (pinfunction "2_2") (pintype "passive"))
      (node (ref "C26") (pin "2") (pinfunction "2_2") (pintype "passive"))
      (node (ref "C27") (pin "2") (pinfunction "2_2") (pintype "passive"))
      (node (ref "C28") (pin "2") (pinfunction "2_2") (pintype "passive"))
      (node (ref "C29") (pin "2") (pinfunction "2_2") (pintype "passive"))
      (node (ref "C3") (pin "2") (pinfunction "2_2") (pintype "passive"))
      (node (ref "C30") (pin "2") (pinfunction "2_2") (pintype "passive"))
      (node (ref "C31") (pin "2") (pinfunction "2_2") (pintype "passive"))
      (node (ref "C32") (pin "2") (pinfunction "2_2") (pintype "passive"))
      (node (ref "C34") (pin "2") (pinfunction "2_2") (pintype "passive"))
      (node (ref "C35") (pin "1") (pinfunction "1_1") (pintype "passive"))
      (node (ref "C36") (pin "2") (pinfunction "2_2") (pintype "passive"))
      (node (ref "C37") (pin "2") (pinfunction "2_2") (pintype "passive"))
      (node (ref "C38") (pin "2") (pinfunction "2_2") (pintype "passive"))
      (node (ref "C4") (pin "2") (pinfunction "2_2") (pintype "passive"))
      (node (ref "C40") (pin "2") (pinfunction "2_2") (pintype "passive"))
      (node (ref "C41") (pin "1") (pinfunction "1_1") (pintype "passive"))
      (node (ref "C42") (pin "2") (pinfunction "2_2") (pintype "passive"))
      (node (ref "C43") (pin "2") (pinfunction "2_2") (pintype "passive"))
      (node (ref "C44") (pin "2") (pinfunction "2_2") (pintype "passive"))
      (node (ref "C46") (pin "2") (pinfunction "2_2") (pintype "passive"))
      (node (ref "C47") (pin "1") (pinfunction "1_1") (pintype "passive"))
      (node (ref "C48") (pin "2") (pinfunction "2_2") (pintype "passive"))
      (node (ref "C49") (pin "2") (pinfunction "2_2") (pintype "passive"))
      (node (ref "C5") (pin "2") (pinfunction "2_2") (pintype "passive"))
      (node (ref "C50") (pin "2") (pinfunction "2_2") (pintype "passive"))
      (node (ref "C52") (pin "2") (pinfunction "2_2") (pintype "passive"))
      (node (ref "C53") (pin "1") (pinfunction "1_1") (pintype "passive"))
      (node (ref "C54") (pin "2") (pinfunction "2_2") (pintype "passive"))
      (node (ref "C55") (pin "2") (pinfunction "2_2") (pintype "passive"))
      (node (ref "C56") (pin "2") (pinfunction "2_2") (pintype "passive"))
      (node (ref "C58") (pin "2") (pinfunction "2_2") (pintype "passive"))
      (node (ref "C59") (pin "1") (pinfunction "1_1") (pintype "passive"))
      (node (ref "C6") (pin "2") (pinfunction "2_2") (pintype "passive"))
      (node (ref "C60") (pin "2") (pinfunction "2_2") (pintype "passive"))
      (node (ref "C61") (pin "2") (pinfunction "2_2") (pintype "passive"))
      (node (ref "C62") (pin "2") (pinfunction "2_2") (pintype "passive"))
      (node (ref "C63") (pin "2") (pinfunction "2_2") (pintype "passive"))
      (node (ref "C65") (pin "1") (pinfunction "1_1") (pintype "passive"))
      (node (ref "C67") (pin "1") (pinfunction "1_1") (pintype "passive"))
      (node (ref "C69") (pin "1") (pinfunction "1_1") (pintype "passive"))
      (node (ref "C7") (pin "2") (pinfunction "2_2") (pintype "passive"))
      (node (ref "C71") (pin "1") (pinfunction "1_1") (pintype "passive"))
      (node (ref "C73") (pin "1") (pinfunction "1_1") (pintype "passive"))
      (node (ref "C74") (pin "2") (pinfunction "2_2") (pintype "passive"))
      (node (ref "C75") (pin "2") (pinfunction "2_2") (pintype "passive"))
      (node (ref "C76") (pin "2") (pinfunction "2_2") (pintype "passive"))
      (node (ref "C77") (pin "2") (pinfunction "2_2") (pintype "passive"))
      (node (ref "C78") (pin "2") (pinfunction "2_2") (pintype "passive"))
      (node (ref "C79") (pin "-") (pinfunction "-_-") (pintype "passive"))
      (node (ref "C8") (pin "2") (pinfunction "2_2") (pintype "passive"))
      (node (ref "C80") (pin "-") (pinfunction "-_-") (pintype "passive"))
      (node (ref "C81") (pin "-") (pinfunction "-_-") (pintype "passive"))
      (node (ref "C82") (pin "-") (pinfunction "-_-") (pintype "passive"))
      (node (ref "C83") (pin "-") (pinfunction "-_-") (pintype "passive"))
      (node (ref "C84") (pin "2") (pinfunction "2_2") (pintype "passive"))
      (node (ref "C85") (pin "2") (pinfunction "2_2") (pintype "passive"))
      (node (ref "C86") (pin "2") (pinfunction "2_2") (pintype "passive"))
      (node (ref "C87") (pin "2") (pinfunction "2_2") (pintype "passive"))
      (node (ref "C88") (pin "2") (pinfunction "2_2") (pintype "passive"))
      (node (ref "C89") (pin "2") (pinfunction "2_2") (pintype "passive"))
      (node (ref "C9") (pin "2") (pinfunction "2_2") (pintype "passive"))
      (node (ref "C90") (pin "2") (pinfunction "2_2") (pintype "passive"))
      (node (ref "C91") (pin "2") (pinfunction "2_2") (pintype "passive"))
      (node (ref "C92") (pin "2") (pinfunction "2_2") (pintype "passive"))
      (node (ref "C93") (pin "2") (pinfunction "2_2") (pintype "passive"))
      (node (ref "D2") (pin "A") (pinfunction "A_A") (pintype "passive"))
      (node (ref "D4") (pin "A") (pinfunction "A_A") (pintype "passive"))
      (node (ref "D6") (pin "A") (pinfunction "A_A") (pintype "passive"))
      (node (ref "IC1") (pin "3") (pinfunction "GND_3") (pintype "power_in"))
      (node (ref "IC10") (pin "3") (pinfunction "GND_3") (pintype "power_in"))
      (node (ref "IC11") (pin "3") (pinfunction "GND_3") (pintype "power_in"))
      (node (ref "IC12") (pin "3") (pinfunction "GND_3") (pintype "power_in"))
      (node (ref "IC13") (pin "3") (pinfunction "GND_3") (pintype "power_in"))
      (node (ref "IC14") (pin "3") (pinfunction "GND_3") (pintype "power_in"))
      (node (ref "IC15") (pin "3") (pinfunction "GND_3") (pintype "power_in"))
      (node (ref "IC16") (pin "3") (pinfunction "GND_3") (pintype "power_in"))
      (node (ref "IC17") (pin "3") (pinfunction "GND_3") (pintype "power_in"))
      (node (ref "IC18") (pin "1") (pinfunction "CLK_1") (pintype "bidirectional"))
      (node (ref "IC18") (pin "10") (pinfunction "SPI_MODE_10") (pintype "bidirectional"))
      (node (ref "IC18") (pin "11") (pinfunction "GND_11") (pintype "bidirectional"))
      (node (ref "IC18") (pin "12") (pinfunction "GND_12") (pintype "bidirectional"))
      (node (ref "IC18") (pin "24") (pinfunction "GNDA_24") (pintype "bidirectional"))
      (node (ref "IC18") (pin "35") (pinfunction "GND_35") (pintype "bidirectional"))
      (node (ref "IC18") (pin "36") (pinfunction "TST_MODE_36") (pintype "bidirectional"))
      (node (ref "IC18") (pin "TP") (pinfunction "GND_TP") (pintype "bidirectional"))
      (node (ref "IC19") (pin "1") (pinfunction "CLK_1") (pintype "bidirectional"))
      (node (ref "IC19") (pin "10") (pinfunction "SPI_MODE_10") (pintype "bidirectional"))
      (node (ref "IC19") (pin "11") (pinfunction "GND_11") (pintype "bidirectional"))
      (node (ref "IC19") (pin "12") (pinfunction "GND_12") (pintype "bidirectional"))
      (node (ref "IC19") (pin "24") (pinfunction "GNDA_24") (pintype "bidirectional"))
      (node (ref "IC19") (pin "35") (pinfunction "GND_35") (pintype "bidirectional"))
      (node (ref "IC19") (pin "36") (pinfunction "TST_MODE_36") (pintype "bidirectional"))
      (node (ref "IC19") (pin "TP") (pinfunction "GND_TP") (pintype "bidirectional"))
      (node (ref "IC2") (pin "3") (pinfunction "GND_3") (pintype "power_in"))
      (node (ref "IC20") (pin "1") (pinfunction "CLK_1") (pintype "bidirectional"))
      (node (ref "IC20") (pin "10") (pinfunction "SPI_MODE_10") (pintype "bidirectional"))
      (node (ref "IC20") (pin "11") (pinfunction "GND_11") (pintype "bidirectional"))
      (node (ref "IC20") (pin "12") (pinfunction "GND_12") (pintype "bidirectional"))
      (node (ref "IC20") (pin "24") (pinfunction "GNDA_24") (pintype "bidirectional"))
      (node (ref "IC20") (pin "35") (pinfunction "GND_35") (pintype "bidirectional"))
      (node (ref "IC20") (pin "36") (pinfunction "TST_MODE_36") (pintype "bidirectional"))
      (node (ref "IC20") (pin "TP") (pinfunction "GND_TP") (pintype "bidirectional"))
      (node (ref "IC21") (pin "1") (pinfunction "CLK_1") (pintype "bidirectional"))
      (node (ref "IC21") (pin "10") (pinfunction "SPI_MODE_10") (pintype "bidirectional"))
      (node (ref "IC21") (pin "11") (pinfunction "GND_11") (pintype "bidirectional"))
      (node (ref "IC21") (pin "12") (pinfunction "GND_12") (pintype "bidirectional"))
      (node (ref "IC21") (pin "24") (pinfunction "GNDA_24") (pintype "bidirectional"))
      (node (ref "IC21") (pin "35") (pinfunction "GND_35") (pintype "bidirectional"))
      (node (ref "IC21") (pin "36") (pinfunction "TST_MODE_36") (pintype "bidirectional"))
      (node (ref "IC21") (pin "TP") (pinfunction "GND_TP") (pintype "bidirectional"))
      (node (ref "IC22") (pin "1") (pinfunction "CLK_1") (pintype "bidirectional"))
      (node (ref "IC22") (pin "10") (pinfunction "SPI_MODE_10") (pintype "bidirectional"))
      (node (ref "IC22") (pin "11") (pinfunction "GND_11") (pintype "bidirectional"))
      (node (ref "IC22") (pin "12") (pinfunction "GND_12") (pintype "bidirectional"))
      (node (ref "IC22") (pin "24") (pinfunction "GNDA_24") (pintype "bidirectional"))
      (node (ref "IC22") (pin "35") (pinfunction "GND_35") (pintype "bidirectional"))
      (node (ref "IC22") (pin "36") (pinfunction "TST_MODE_36") (pintype "bidirectional"))
      (node (ref "IC22") (pin "TP") (pinfunction "GND_TP") (pintype "bidirectional"))
      (node (ref "IC3") (pin "3") (pinfunction "GND_3") (pintype "power_in"))
      (node (ref "IC4") (pin "3") (pinfunction "GND_3") (pintype "power_in"))
      (node (ref "IC5") (pin "3") (pinfunction "GND_3") (pintype "power_in"))
      (node (ref "IC6") (pin "3") (pinfunction "GND_3") (pintype "power_in"))
      (node (ref "IC7") (pin "3") (pinfunction "GND_3") (pintype "power_in"))
      (node (ref "IC8") (pin "3") (pinfunction "GND_3") (pintype "power_in"))
      (node (ref "IC9") (pin "3") (pinfunction "GND_3") (pintype "power_in"))
      (node (ref "LED2") (pin "C") (pinfunction "C_C") (pintype "passive"))
      (node (ref "P1") (pin "1") (pinfunction "1_1") (pintype "passive"))
      (node (ref "P1") (pin "2") (pinfunction "2_2") (pintype "passive"))
      (node (ref "P1") (pin "43") (pinfunction "43_43") (pintype "passive"))
      (node (ref "P1") (pin "44") (pinfunction "44_44") (pintype "passive"))
      (node (ref "P1") (pin "45") (pinfunction "45_45") (pintype "passive"))
      (node (ref "P1") (pin "46") (pinfunction "46_46") (pintype "passive"))
      (node (ref "P2") (pin "1") (pinfunction "1_1") (pintype "passive"))
      (node (ref "P2") (pin "2") (pinfunction "2_2") (pintype "passive"))
      (node (ref "Q1") (pin "1") (pinfunction "S_1") (pintype "passive"))
      (node (ref "Q1") (pin "2") (pinfunction "S_2") (pintype "passive"))
      (node (ref "Q1") (pin "3") (pinfunction "S_3") (pintype "passive"))
      (node (ref "Q2") (pin "1") (pinfunction "S_1") (pintype "passive"))
      (node (ref "Q2") (pin "2") (pinfunction "S_2") (pintype "passive"))
      (node (ref "Q2") (pin "3") (pinfunction "S_3") (pintype "passive"))
      (node (ref "Q3") (pin "1") (pinfunction "S_1") (pintype "passive"))
      (node (ref "Q3") (pin "2") (pinfunction "S_2") (pintype "passive"))
      (node (ref "Q3") (pin "3") (pinfunction "S_3") (pintype "passive"))
      (node (ref "Q4") (pin "2") (pinfunction "E_2") (pintype "passive"))
      (node (ref "Q5") (pin "2") (pinfunction "E_2") (pintype "passive"))
      (node (ref "R16") (pin "2") (pinfunction "2_2") (pintype "passive"))
      (node (ref "R18") (pin "2") (pinfunction "2_2") (pintype "passive"))
      (node (ref "R20") (pin "2") (pinfunction "2_2") (pintype "passive"))
      (node (ref "R21") (pin "1") (pinfunction "1_1") (pintype "passive"))
      (node (ref "R23") (pin "2") (pinfunction "2_2") (pintype "passive"))
      (node (ref "R47") (pin "1") (pinfunction "1_1") (pintype "passive"))
      (node (ref "R48") (pin "1") (pinfunction "1_1") (pintype "passive"))
      (node (ref "R49") (pin "1") (pinfunction "1_1") (pintype "passive"))
      (node (ref "R50") (pin "1") (pinfunction "1_1") (pintype "passive"))
      (node (ref "R51") (pin "1") (pinfunction "1_1") (pintype "passive"))
      (node (ref "R52") (pin "1") (pinfunction "1_1") (pintype "passive"))
      (node (ref "R53") (pin "1") (pinfunction "1_1") (pintype "passive"))
      (node (ref "R54") (pin "1") (pinfunction "1_1") (pintype "passive"))
      (node (ref "R55") (pin "1") (pinfunction "1_1") (pintype "passive"))
      (node (ref "R56") (pin "1") (pinfunction "1_1") (pintype "passive"))
      (node (ref "R57") (pin "1") (pinfunction "1_1") (pintype "passive"))
      (node (ref "R60") (pin "1") (pinfunction "1_1") (pintype "passive"))
      (node (ref "R61") (pin "1") (pinfunction "1_1") (pintype "passive"))
      (node (ref "R7") (pin "1") (pinfunction "1_1") (pintype "passive"))
      (node (ref "U1") (pin "14") (pinfunction "VSS_14") (pintype "passive"))
      (node (ref "U10") (pin "13") (pinfunction "~{OE}_13") (pintype "input"))
      (node (ref "U10") (pin "8") (pinfunction "GND_8") (pintype "passive"))
      (node (ref "U2") (pin "1") (pinfunction "A0_1") (pintype "input"))
      (node (ref "U2") (pin "2") (pinfunction "A1_2") (pintype "input"))
      (node (ref "U2") (pin "4") (pinfunction "GND_4") (pintype "power_in"))
      (node (ref "U3") (pin "8") (pinfunction "VSS_8") (pintype "power_in"))
      (node (ref "U4") (pin "6") (pinfunction "GND_6") (pintype "power_in"))
      (node (ref "U4") (pin "EP") (pinfunction "EP_EP") (pintype "power_in"))
      (node (ref "U5") (pin "6") (pinfunction "GND_6") (pintype "power_in"))
      (node (ref "U5") (pin "EP") (pinfunction "EP_EP") (pintype "power_in"))
      (node (ref "U6") (pin "13") (pinfunction "~{OE}_13") (pintype "input"))
      (node (ref "U6") (pin "8") (pinfunction "GND_8") (pintype "passive"))
      (node (ref "U7") (pin "13") (pinfunction "~{OE}_13") (pintype "input"))
      (node (ref "U7") (pin "8") (pinfunction "GND_8") (pintype "passive"))
      (node (ref "U8") (pin "13") (pinfunction "~{OE}_13") (pintype "input"))
      (node (ref "U8") (pin "8") (pinfunction "GND_8") (pintype "passive"))
      (node (ref "U9") (pin "13") (pinfunction "~{OE}_13") (pintype "input"))
      (node (ref "U9") (pin "8") (pinfunction "GND_8") (pintype "passive"))
      (node (ref "X1") (pin "3") (pinfunction "S_3") (pintype "passive"))
      (node (ref "X10") (pin "2") (pinfunction "S_2") (pintype "passive"))
      (node (ref "X14") (pin "1") (pinfunction "1_1") (pintype "passive"))
      (node (ref "X14") (pin "2") (pinfunction "1_2") (pintype "passive"))
      (node (ref "X2") (pin "1") (pinfunction "S_1") (pintype "passive"))
      (node (ref "X3") (pin "1") (pinfunction "S_1") (pintype "passive"))
      (node (ref "X4") (pin "1") (pinfunction "S_1") (pintype "passive"))
      (node (ref "X5") (pin "2") (pinfunction "S_2") (pintype "passive"))
      (node (ref "X6") (pin "2") (pinfunction "S_2") (pintype "passive"))
      (node (ref "X7") (pin "2") (pinfunction "S_2") (pintype "passive"))
      (node (ref "X8") (pin "2") (pinfunction "S_2") (pintype "passive"))
      (node (ref "X9") (pin "2") (pinfunction "S_2") (pintype "passive"))
    )
    (net (code "40") (name "HEATER_E") (class "Default")
      (node (ref "Q3") (pin "4") (pinfunction "G_4") (pintype "passive"))
      (node (ref "R47") (pin "2") (pinfunction "2_2") (pintype "passive"))
      (node (ref "U1") (pin "11") (pinfunction "LED5_11") (pintype "output"))
    )
    (net (code "41") (name "HEATER_E_OUT") (class "Default")
      (node (ref "C63") (pin "1") (pinfunction "1_1") (pintype "passive"))
      (node (ref "D5") (pin "A") (pinfunction "A_A") (pintype "passive"))
      (node (ref "LED4") (pin "C") (pinfunction "C_C") (pintype "passive"))
      (node (ref "Q3") (pin "5") (pinfunction "D_5") (pintype "passive"))
      (node (ref "Q3") (pin "6") (pinfunction "D_6") (pintype "passive"))
      (node (ref "Q3") (pin "7") (pinfunction "D_7") (pintype "passive"))
      (node (ref "Q3") (pin "8") (pinfunction "D_8") (pintype "passive"))
      (node (ref "Q3") (pin "TH") (pinfunction "D_TH") (pintype "passive"))
      (node (ref "R58") (pin "1") (pinfunction "1_1") (pintype "passive"))
      (node (ref "X13") (pin "2") (pinfunction "1_2") (pintype "passive"))
    )
    (net (code "42") (name "HEATER_H") (class "Default")
      (node (ref "Q1") (pin "4") (pinfunction "G_4") (pintype "passive"))
      (node (ref "R7") (pin "2") (pinfunction "2_2") (pintype "passive"))
      (node (ref "U1") (pin "9") (pinfunction "LED3_9") (pintype "output"))
    )
    (net (code "43") (name "HEATER_HBP") (class "Default")
      (node (ref "Q2") (pin "4") (pinfunction "G_4") (pintype "passive"))
      (node (ref "R21") (pin "2") (pinfunction "2_2") (pintype "passive"))
      (node (ref "U1") (pin "10") (pinfunction "LED4_10") (pintype "output"))
    )
    (net (code "44") (name "I2C2_SCL") (class "Default")
      (node (ref "P1") (pin "19") (pinfunction "19_19") (pintype "passive"))
      (node (ref "U1") (pin "26") (pinfunction "SCL_26") (pintype "input"))
      (node (ref "U2") (pin "6") (pinfunction "SCL_6") (pintype "input"))
    )
    (net (code "45") (name "I2C2_SDA") (class "Default")
      (node (ref "P1") (pin "20") (pinfunction "20_20") (pintype "passive"))
      (node (ref "U1") (pin "27") (pinfunction "SDA_27") (pintype "bidirectional"))
      (node (ref "U2") (pin "5") (pinfunction "SDA_5") (pintype "bidirectional"))
    )
    (net (code "46") (name "IREF_E_RAW") (class "Default")
      (node (ref "R41") (pin "2") (pinfunction "2_2") (pintype "passive"))
      (node (ref "U1") (pin "21") (pinfunction "LED14_21") (pintype "output"))
    )
    (net (code "47") (name "IREF_H_RAW") (class "Default")
      (node (ref "R45") (pin "2") (pinfunction "2_2") (pintype "passive"))
      (node (ref "U1") (pin "22") (pinfunction "LED15_22") (pintype "output"))
    )
    (net (code "48") (name "IREF_X_RAW") (class "Default")
      (node (ref "R29") (pin "2") (pinfunction "2_2") (pintype "passive"))
      (node (ref "U1") (pin "18") (pinfunction "LED11_18") (pintype "output"))
    )
    (net (code "49") (name "IREF_Y_RAW") (class "Default")
      (node (ref "R33") (pin "2") (pinfunction "2_2") (pintype "passive"))
      (node (ref "U1") (pin "19") (pinfunction "LED12_19") (pintype "output"))
    )
    (net (code "50") (name "IREF_Z_RAW") (class "Default")
      (node (ref "R37") (pin "2") (pinfunction "2_2") (pintype "passive"))
      (node (ref "U1") (pin "20") (pinfunction "LED13_20") (pintype "output"))
    )
    (net (code "51") (name "Net-(C14-Pad2)") (class "Default")
      (node (ref "C14") (pin "2") (pinfunction "2_2") (pintype "passive"))
      (node (ref "R20") (pin "1") (pinfunction "1_1") (pintype "passive"))
    )
    (net (code "52") (name "Net-(C17-Pad2)") (class "Default")
      (node (ref "C17") (pin "2") (pinfunction "2_2") (pintype "passive"))
      (node (ref "R23") (pin "1") (pinfunction "1_1") (pintype "passive"))
    )
    (net (code "53") (name "Net-(C37-Pad1)") (class "Default")
      (node (ref "C37") (pin "1") (pinfunction "1_1") (pintype "passive"))
      (node (ref "R28") (pin "2") (pinfunction "2_2") (pintype "passive"))
      (node (ref "R29") (pin "1") (pinfunction "1_1") (pintype "passive"))
    )
    (net (code "54") (name "Net-(C43-Pad1)") (class "Default")
      (node (ref "C43") (pin "1") (pinfunction "1_1") (pintype "passive"))
      (node (ref "R32") (pin "2") (pinfunction "2_2") (pintype "passive"))
      (node (ref "R33") (pin "1") (pinfunction "1_1") (pintype "passive"))
    )
    (net (code "55") (name "Net-(C49-Pad1)") (class "Default")
      (node (ref "C49") (pin "1") (pinfunction "1_1") (pintype "passive"))
      (node (ref "R36") (pin "2") (pinfunction "2_2") (pintype "passive"))
      (node (ref "R37") (pin "1") (pinfunction "1_1") (pintype "passive"))
    )
    (net (code "56") (name "Net-(C55-Pad1)") (class "Default")
      (node (ref "C55") (pin "1") (pinfunction "1_1") (pintype "passive"))
      (node (ref "R40") (pin "2") (pinfunction "2_2") (pintype "passive"))
      (node (ref "R41") (pin "1") (pinfunction "1_1") (pintype "passive"))
    )
    (net (code "57") (name "Net-(C61-Pad1)") (class "Default")
      (node (ref "C61") (pin "1") (pinfunction "1_1") (pintype "passive"))
      (node (ref "R44") (pin "2") (pinfunction "2_2") (pintype "passive"))
      (node (ref "R45") (pin "1") (pinfunction "1_1") (pintype "passive"))
    )
    (net (code "58") (name "Net-(IC8A-I)") (class "Default")
      (node (ref "IC8") (pin "2") (pinfunction "I_2") (pintype "input"))
      (node (ref "U6") (pin "6") (pinfunction "QG_6") (pintype "output"))
    )
    (net (code "59") (name "Net-(IC8A-OE)") (class "Default")
      (node (ref "IC8") (pin "1") (pinfunction "OE_1") (pintype "input"))
      (node (ref "U6") (pin "7") (pinfunction "QH_7") (pintype "output"))
    )
    (net (code "60") (name "Net-(IC9A-I)") (class "Default")
      (node (ref "IC9") (pin "2") (pinfunction "I_2") (pintype "input"))
      (node (ref "U7") (pin "6") (pinfunction "QG_6") (pintype "output"))
    )
    (net (code "61") (name "Net-(IC9A-OE)") (class "Default")
      (node (ref "IC9") (pin "1") (pinfunction "OE_1") (pintype "input"))
      (node (ref "U7") (pin "7") (pinfunction "QH_7") (pintype "output"))
    )
    (net (code "62") (name "Net-(IC10A-I)") (class "Default")
      (node (ref "IC10") (pin "2") (pinfunction "I_2") (pintype "input"))
      (node (ref "U8") (pin "6") (pinfunction "QG_6") (pintype "output"))
    )
    (net (code "63") (name "Net-(IC10A-O)") (class "Default")
      (node (ref "IC10") (pin "4") (pinfunction "O_4") (pintype "output"))
      (node (ref "IC20") (pin "4") (pinfunction "SDI_NAI_CFG1_4") (pintype "bidirectional"))
    )
    (net (code "64") (name "Net-(IC10A-OE)") (class "Default")
      (node (ref "IC10") (pin "1") (pinfunction "OE_1") (pintype "input"))
      (node (ref "U8") (pin "7") (pinfunction "QH_7") (pintype "output"))
    )
    (net (code "65") (name "Net-(IC11A-I)") (class "Default")
      (node (ref "IC11") (pin "2") (pinfunction "I_2") (pintype "input"))
      (node (ref "U9") (pin "6") (pinfunction "QG_6") (pintype "output"))
    )
    (net (code "66") (name "Net-(IC11A-O)") (class "Default")
      (node (ref "IC11") (pin "4") (pinfunction "O_4") (pintype "output"))
      (node (ref "IC21") (pin "4") (pinfunction "SDI_NAI_CFG1_4") (pintype "bidirectional"))
    )
    (net (code "67") (name "Net-(IC11A-OE)") (class "Default")
      (node (ref "IC11") (pin "1") (pinfunction "OE_1") (pintype "input"))
      (node (ref "U9") (pin "7") (pinfunction "QH_7") (pintype "output"))
    )
    (net (code "68") (name "Net-(IC12A-I)") (class "Default")
      (node (ref "IC12") (pin "2") (pinfunction "I_2") (pintype "input"))
      (node (ref "U10") (pin "6") (pinfunction "QG_6") (pintype "output"))
    )
    (net (code "69") (name "Net-(IC12A-O)") (class "Default")
      (node (ref "IC12") (pin "4") (pinfunction "O_4") (pintype "output"))
      (node (ref "IC22") (pin "4") (pinfunction "SDI_NAI_CFG1_4") (pintype "bidirectional"))
    )
    (net (code "70") (name "Net-(IC12A-OE)") (class "Default")
      (node (ref "IC12") (pin "1") (pinfunction "OE_1") (pintype "input"))
      (node (ref "U10") (pin "7") (pinfunction "QH_7") (pintype "output"))
    )
    (net (code "71") (name "Net-(IC13A-I)") (class "Default")
      (node (ref "IC13") (pin "2") (pinfunction "I_2") (pintype "input"))
      (node (ref "U6") (pin "4") (pinfunction "QE_4") (pintype "output"))
    )
    (net (code "72") (name "Net-(IC13A-O)") (class "Default")
      (node (ref "IC13") (pin "4") (pinfunction "O_4") (pintype "output"))
      (node (ref "IC18") (pin "3") (pinfunction "SCK_CFG2_3") (pintype "bidirectional"))
    )
    (net (code "73") (name "Net-(IC13A-OE)") (class "Default")
      (node (ref "IC13") (pin "1") (pinfunction "OE_1") (pintype "input"))
      (node (ref "U6") (pin "5") (pinfunction "QF_5") (pintype "output"))
    )
    (net (code "74") (name "Net-(IC14A-I)") (class "Default")
      (node (ref "IC14") (pin "2") (pinfunction "I_2") (pintype "input"))
      (node (ref "U7") (pin "4") (pinfunction "QE_4") (pintype "output"))
    )
    (net (code "75") (name "Net-(IC14A-O)") (class "Default")
      (node (ref "IC14") (pin "4") (pinfunction "O_4") (pintype "output"))
      (node (ref "IC19") (pin "3") (pinfunction "SCK_CFG2_3") (pintype "bidirectional"))
    )
    (net (code "76") (name "Net-(IC14A-OE)") (class "Default")
      (node (ref "IC14") (pin "1") (pinfunction "OE_1") (pintype "input"))
      (node (ref "U7") (pin "5") (pinfunction "QF_5") (pintype "output"))
    )
    (net (code "77") (name "Net-(IC15A-I)") (class "Default")
      (node (ref "IC15") (pin "2") (pinfunction "I_2") (pintype "input"))
      (node (ref "U8") (pin "4") (pinfunction "QE_4") (pintype "output"))
    )
    (net (code "78") (name "Net-(IC15A-O)") (class "Default")
      (node (ref "IC15") (pin "4") (pinfunction "O_4") (pintype "output"))
      (node (ref "IC20") (pin "3") (pinfunction "SCK_CFG2_3") (pintype "bidirectional"))
    )
    (net (code "79") (name "Net-(IC15A-OE)") (class "Default")
      (node (ref "IC15") (pin "1") (pinfunction "OE_1") (pintype "input"))
      (node (ref "U8") (pin "5") (pinfunction "QF_5") (pintype "output"))
    )
    (net (code "80") (name "Net-(IC16A-I)") (class "Default")
      (node (ref "IC16") (pin "2") (pinfunction "I_2") (pintype "input"))
      (node (ref "U9") (pin "4") (pinfunction "QE_4") (pintype "output"))
    )
    (net (code "81") (name "Net-(IC16A-O)") (class "Default")
      (node (ref "IC16") (pin "4") (pinfunction "O_4") (pintype "output"))
      (node (ref "IC21") (pin "3") (pinfunction "SCK_CFG2_3") (pintype "bidirectional"))
    )
    (net (code "82") (name "Net-(IC16A-OE)") (class "Default")
      (node (ref "IC16") (pin "1") (pinfunction "OE_1") (pintype "input"))
      (node (ref "U9") (pin "5") (pinfunction "QF_5") (pintype "output"))
    )
    (net (code "83") (name "Net-(IC17A-I)") (class "Default")
      (node (ref "IC17") (pin "2") (pinfunction "I_2") (pintype "input"))
      (node (ref "U10") (pin "4") (pinfunction "QE_4") (pintype "output"))
    )
    (net (code "84") (name "Net-(IC17A-O)") (class "Default")
      (node (ref "IC17") (pin "4") (pinfunction "O_4") (pintype "output"))
      (node (ref "IC22") (pin "3") (pinfunction "SCK_CFG2_3") (pintype "bidirectional"))
    )
    (net (code "85") (name "Net-(IC17A-OE)") (class "Default")
      (node (ref "IC17") (pin "1") (pinfunction "OE_1") (pintype "input"))
      (node (ref "U10") (pin "5") (pinfunction "QF_5") (pintype "output"))
    )
    (net (code "86") (name "Net-(IC18-5VOUT)") (class "Default")
      (node (ref "C35") (pin "2") (pinfunction "2_2") (pintype "passive"))
      (node (ref "IC18") (pin "25") (pinfunction "5VOUT_25") (pintype "bidirectional"))
      (node (ref "R27") (pin "1") (pinfunction "1_1") (pintype "passive"))
    )
    (net (code "87") (name "Net-(IC18-AIN_IREF)") (class "Default")
      (node (ref "C36") (pin "1") (pinfunction "1_1") (pintype "passive"))
      (node (ref "IC18") (pin "23") (pinfunction "AIN_IREF_23") (pintype "bidirectional"))
      (node (ref "R28") (pin "1") (pinfunction "1_1") (pintype "passive"))
    )
    (net (code "88") (name "Net-(IC18-BRA)") (class "Default")
      (node (ref "IC18") (pin "33") (pinfunction "BRA_33") (pintype "bidirectional"))
      (node (ref "R48") (pin "2") (pinfunction "2_2") (pintype "passive"))
    )
    (net (code "89") (name "Net-(IC18-BRB)") (class "Default")
      (node (ref "IC18") (pin "14") (pinfunction "BRB_14") (pintype "bidirectional"))
      (node (ref "R49") (pin "2") (pinfunction "2_2") (pintype "passive"))
    )
    (net (code "90") (name "Net-(IC18-CPI)") (class "Default")
      (node (ref "C33") (pin "1") (pinfunction "1_1") (pintype "passive"))
      (node (ref "IC18") (pin "28") (pinfunction "CPI_28") (pintype "bidirectional"))
    )
    (net (code "91") (name "Net-(IC18-CPO)") (class "Default")
      (node (ref "C33") (pin "2") (pinfunction "2_2") (pintype "passive"))
      (node (ref "IC18") (pin "27") (pinfunction "CPO_27") (pintype "bidirectional"))
    )
    (net (code "92") (name "Net-(IC18-ENCA_DCIN_CFG5)") (class "Default")
      (node (ref "IC18") (pin "19") (pinfunction "ENCA_DCIN_CFG5_19") (pintype "bidirectional"))
      (node (ref "U6") (pin "1") (pinfunction "QB_1") (pintype "output"))
    )
    (net (code "93") (name "Net-(IC18-ENCB_DCEN_CFG4)") (class "Default")
      (node (ref "IC18") (pin "18") (pinfunction "ENCB_DCEN_CFG4_18") (pintype "bidirectional"))
      (node (ref "U6") (pin "2") (pinfunction "QC_2") (pintype "output"))
    )
    (net (code "94") (name "Net-(IC18-SDI_NAI_CFG1)") (class "Default")
      (node (ref "IC18") (pin "4") (pinfunction "SDI_NAI_CFG1_4") (pintype "bidirectional"))
      (node (ref "IC8") (pin "4") (pinfunction "O_4") (pintype "output"))
    )
    (net (code "95") (name "Net-(IC18-SDO_NAO_CFG0)") (class "Default")
      (node (ref "IC18") (pin "5") (pinfunction "SDO_NAO_CFG0_5") (pintype "bidirectional"))
      (node (ref "U6") (pin "3") (pinfunction "QD_3") (pintype "output"))
    )
    (net (code "96") (name "Net-(IC18-VCC)") (class "Default")
      (node (ref "C34") (pin "1") (pinfunction "1_1") (pintype "passive"))
      (node (ref "IC18") (pin "26") (pinfunction "VCC_26") (pintype "bidirectional"))
      (node (ref "R27") (pin "2") (pinfunction "2_2") (pintype "passive"))
    )
    (net (code "97") (name "Net-(IC18-VCP)") (class "Default")
      (node (ref "C64") (pin "1") (pinfunction "1_1") (pintype "passive"))
      (node (ref "IC18") (pin "29") (pinfunction "VCP_29") (pintype "bidirectional"))
    )
    (net (code "98") (name "Net-(IC19-5VOUT)") (class "Default")
      (node (ref "C41") (pin "2") (pinfunction "2_2") (pintype "passive"))
      (node (ref "IC19") (pin "25") (pinfunction "5VOUT_25") (pintype "bidirectional"))
      (node (ref "R31") (pin "1") (pinfunction "1_1") (pintype "passive"))
    )
    (net (code "99") (name "Net-(IC19-AIN_IREF)") (class "Default")
      (node (ref "C42") (pin "1") (pinfunction "1_1") (pintype "passive"))
      (node (ref "IC19") (pin "23") (pinfunction "AIN_IREF_23") (pintype "bidirectional"))
      (node (ref "R32") (pin "1") (pinfunction "1_1") (pintype "passive"))
    )
    (net (code "100") (name "Net-(IC19-BRA)") (class "Default")
      (node (ref "IC19") (pin "33") (pinfunction "BRA_33") (pintype "bidirectional"))
      (node (ref "R50") (pin "2") (pinfunction "2_2") (pintype "passive"))
    )
    (net (code "101") (name "Net-(IC19-BRB)") (class "Default")
      (node (ref "IC19") (pin "14") (pinfunction "BRB_14") (pintype "bidirectional"))
      (node (ref "R51") (pin "2") (pinfunction "2_2") (pintype "passive"))
    )
    (net (code "102") (name "Net-(IC19-CPI)") (class "Default")
      (node (ref "C39") (pin "1") (pinfunction "1_1") (pintype "passive"))
      (node (ref "IC19") (pin "28") (pinfunction "CPI_28") (pintype "bidirectional"))
    )
    (net (code "103") (name "Net-(IC19-CPO)") (class "Default")
      (node (ref "C39") (pin "2") (pinfunction "2_2") (pintype "passive"))
      (node (ref "IC19") (pin "27") (pinfunction "CPO_27") (pintype "bidirectional"))
    )
    (net (code "104") (name "Net-(IC19-ENCA_DCIN_CFG5)") (class "Default")
      (node (ref "IC19") (pin "19") (pinfunction "ENCA_DCIN_CFG5_19") (pintype "bidirectional"))
      (node (ref "U7") (pin "1") (pinfunction "QB_1") (pintype "output"))
    )
    (net (code "105") (name "Net-(IC19-ENCB_DCEN_CFG4)") (class "Default")
      (node (ref "IC19") (pin "18") (pinfunction "ENCB_DCEN_CFG4_18") (pintype "bidirectional"))
      (node (ref "U7") (pin "2") (pinfunction "QC_2") (pintype "output"))
    )
    (net (code "106") (name "Net-(IC19-OA1)") (class "Default")
      (node (ref "IC19") (pin "34") (pinfunction "OA1_34") (pintype "bidirectional"))
      (node (ref "J503") (pin "2") (pinfunction "S_2") (pintype "passive"))
    )
    (net (code "107") (name "Net-(IC19-OA2)") (class "Default")
      (node (ref "IC19") (pin "32") (pinfunction "OA2_32") (pintype "bidirectional"))
      (node (ref "J503") (pin "1") (pinfunction "S_1") (pintype "passive"))
    )
    (net (code "108") (name "Net-(IC19-OB1)") (class "Default")
      (node (ref "IC19") (pin "13") (pinfunction "OB1_13") (pintype "bidirectional"))
      (node (ref "J503") (pin "3") (pinfunction "S_3") (pintype "passive"))
    )
    (net (code "109") (name "Net-(IC19-OB2)") (class "Default")
      (node (ref "IC19") (pin "15") (pinfunction "OB2_15") (pintype "bidirectional"))
      (node (ref "J503") (pin "4") (pinfunction "S_4") (pintype "passive"))
    )
    (net (code "110") (name "Net-(IC19-SDI_NAI_CFG1)") (class "Default")
      (node (ref "IC19") (pin "4") (pinfunction "SDI_NAI_CFG1_4") (pintype "bidirectional"))
      (node (ref "IC9") (pin "4") (pinfunction "O_4") (pintype "output"))
    )
    (net (code "111") (name "Net-(IC19-SDO_NAO_CFG0)") (class "Default")
      (node (ref "IC19") (pin "5") (pinfunction "SDO_NAO_CFG0_5") (pintype "bidirectional"))
      (node (ref "U7") (pin "3") (pinfunction "QD_3") (pintype "output"))
    )
    (net (code "112") (name "Net-(IC19-VCC)") (class "Default")
      (node (ref "C40") (pin "1") (pinfunction "1_1") (pintype "passive"))
      (node (ref "IC19") (pin "26") (pinfunction "VCC_26") (pintype "bidirectional"))
      (node (ref "R31") (pin "2") (pinfunction "2_2") (pintype "passive"))
    )
    (net (code "113") (name "Net-(IC19-VCP)") (class "Default")
      (node (ref "C66") (pin "1") (pinfunction "1_1") (pintype "passive"))
      (node (ref "IC19") (pin "29") (pinfunction "VCP_29") (pintype "bidirectional"))
    )
    (net (code "114") (name "Net-(IC20-5VOUT)") (class "Default")
      (node (ref "C47") (pin "2") (pinfunction "2_2") (pintype "passive"))
      (node (ref "IC20") (pin "25") (pinfunction "5VOUT_25") (pintype "bidirectional"))
      (node (ref "R35") (pin "1") (pinfunction "1_1") (pintype "passive"))
    )
    (net (code "115") (name "Net-(IC20-AIN_IREF)") (class "Default")
      (node (ref "C48") (pin "1") (pinfunction "1_1") (pintype "passive"))
      (node (ref "IC20") (pin "23") (pinfunction "AIN_IREF_23") (pintype "bidirectional"))
      (node (ref "R36") (pin "1") (pinfunction "1_1") (pintype "passive"))
    )
    (net (code "116") (name "Net-(IC20-BRA)") (class "Default")
      (node (ref "IC20") (pin "33") (pinfunction "BRA_33") (pintype "bidirectional"))
      (node (ref "R52") (pin "2") (pinfunction "2_2") (pintype "passive"))
    )
    (net (code "117") (name "Net-(IC20-BRB)") (class "Default")
      (node (ref "IC20") (pin "14") (pinfunction "BRB_14") (pintype "bidirectional"))
      (node (ref "R53") (pin "2") (pinfunction "2_2") (pintype "passive"))
    )
    (net (code "118") (name "Net-(IC20-CPI)") (class "Default")
      (node (ref "C45") (pin "1") (pinfunction "1_1") (pintype "passive"))
      (node (ref "IC20") (pin "28") (pinfunction "CPI_28") (pintype "bidirectional"))
    )
    (net (code "119") (name "Net-(IC20-CPO)") (class "Default")
      (node (ref "C45") (pin "2") (pinfunction "2_2") (pintype "passive"))
      (node (ref "IC20") (pin "27") (pinfunction "CPO_27") (pintype "bidirectional"))
    )
    (net (code "120") (name "Net-(IC20-ENCA_DCIN_CFG5)") (class "Default")
      (node (ref "IC20") (pin "19") (pinfunction "ENCA_DCIN_CFG5_19") (pintype "bidirectional"))
      (node (ref "U8") (pin "1") (pinfunction "QB_1") (pintype "output"))
    )
    (net (code "121") (name "Net-(IC20-ENCB_DCEN_CFG4)") (class "Default")
      (node (ref "IC20") (pin "18") (pinfunction "ENCB_DCEN_CFG4_18") (pintype "bidirectional"))
      (node (ref "U8") (pin "2") (pinfunction "QC_2") (pintype "output"))
    )
    (net (code "122") (name "Net-(IC20-OA1)") (class "Default")
      (node (ref "IC20") (pin "34") (pinfunction "OA1_34") (pintype "bidirectional"))
      (node (ref "J502") (pin "2") (pinfunction "S_2") (pintype "passive"))
    )
    (net (code "123") (name "Net-(IC20-OA2)") (class "Default")
      (node (ref "IC20") (pin "32") (pinfunction "OA2_32") (pintype "bidirectional"))
      (node (ref "J502") (pin "1") (pinfunction "S_1") (pintype "passive"))
    )
    (net (code "124") (name "Net-(IC20-OB1)") (class "Default")
      (node (ref "IC20") (pin "13") (pinfunction "OB1_13") (pintype "bidirectional"))
      (node (ref "J502") (pin "3") (pinfunction "S_3") (pintype "passive"))
    )
    (net (code "125") (name "Net-(IC20-OB2)") (class "Default")
      (node (ref "IC20") (pin "15") (pinfunction "OB2_15") (pintype "bidirectional"))
      (node (ref "J502") (pin "4") (pinfunction "S_4") (pintype "passive"))
    )
    (net (code "126") (name "Net-(IC20-SDO_NAO_CFG0)") (class "Default")
      (node (ref "IC20") (pin "5") (pinfunction "SDO_NAO_CFG0_5") (pintype "bidirectional"))
      (node (ref "U8") (pin "3") (pinfunction "QD_3") (pintype "output"))
    )
    (net (code "127") (name "Net-(IC20-VCC)") (class "Default")
      (node (ref "C46") (pin "1") (pinfunction "1_1") (pintype "passive"))
      (node (ref "IC20") (pin "26") (pinfunction "VCC_26") (pintype "bidirectional"))
      (node (ref "R35") (pin "2") (pinfunction "2_2") (pintype "passive"))
    )
    (net (code "128") (name "Net-(IC20-VCP)") (class "Default")
      (node (ref "C68") (pin "1") (pinfunction "1_1") (pintype "passive"))
      (node (ref "IC20") (pin "29") (pinfunction "VCP_29") (pintype "bidirectional"))
    )
    (net (code "129") (name "Net-(IC21-5VOUT)") (class "Default")
      (node (ref "C53") (pin "2") (pinfunction "2_2") (pintype "passive"))
      (node (ref "IC21") (pin "25") (pinfunction "5VOUT_25") (pintype "bidirectional"))
      (node (ref "R39") (pin "1") (pinfunction "1_1") (pintype "passive"))
    )
    (net (code "130") (name "Net-(IC21-AIN_IREF)") (class "Default")
      (node (ref "C54") (pin "1") (pinfunction "1_1") (pintype "passive"))
      (node (ref "IC21") (pin "23") (pinfunction "AIN_IREF_23") (pintype "bidirectional"))
      (node (ref "R40") (pin "1") (pinfunction "1_1") (pintype "passive"))
    )
    (net (code "131") (name "Net-(IC21-BRA)") (class "Default")
      (node (ref "IC21") (pin "33") (pinfunction "BRA_33") (pintype "bidirectional"))
      (node (ref "R54") (pin "2") (pinfunction "2_2") (pintype "passive"))
    )
    (net (code "132") (name "Net-(IC21-BRB)") (class "Default")
      (node (ref "IC21") (pin "14") (pinfunction "BRB_14") (pintype "bidirectional"))
      (node (ref "R55") (pin "2") (pinfunction "2_2") (pintype "passive"))
    )
    (net (code "133") (name "Net-(IC21-CPI)") (class "Default")
      (node (ref "C51") (pin "1") (pinfunction "1_1") (pintype "passive"))
      (node (ref "IC21") (pin "28") (pinfunction "CPI_28") (pintype "bidirectional"))
    )
    (net (code "134") (name "Net-(IC21-CPO)") (class "Default")
      (node (ref "C51") (pin "2") (pinfunction "2_2") (pintype "passive"))
      (node (ref "IC21") (pin "27") (pinfunction "CPO_27") (pintype "bidirectional"))
    )
    (net (code "135") (name "Net-(IC21-ENCA_DCIN_CFG5)") (class "Default")
      (node (ref "IC21") (pin "19") (pinfunction "ENCA_DCIN_CFG5_19") (pintype "bidirectional"))
      (node (ref "U9") (pin "1") (pinfunction "QB_1") (pintype "output"))
    )
    (net (code "136") (name "Net-(IC21-ENCB_DCEN_CFG4)") (class "Default")
      (node (ref "IC21") (pin "18") (pinfunction "ENCB_DCEN_CFG4_18") (pintype "bidirectional"))
      (node (ref "U9") (pin "2") (pinfunction "QC_2") (pintype "output"))
    )
    (net (code "137") (name "Net-(IC21-SDO_NAO_CFG0)") (class "Default")
      (node (ref "IC21") (pin "5") (pinfunction "SDO_NAO_CFG0_5") (pintype "bidirectional"))
      (node (ref "U9") (pin "3") (pinfunction "QD_3") (pintype "output"))
    )
    (net (code "138") (name "Net-(IC21-VCC)") (class "Default")
      (node (ref "C52") (pin "1") (pinfunction "1_1") (pintype "passive"))
      (node (ref "IC21") (pin "26") (pinfunction "VCC_26") (pintype "bidirectional"))
      (node (ref "R39") (pin "2") (pinfunction "2_2") (pintype "passive"))
    )
    (net (code "139") (name "Net-(IC21-VCP)") (class "Default")
      (node (ref "C70") (pin "1") (pinfunction "1_1") (pintype "passive"))
      (node (ref "IC21") (pin "29") (pinfunction "VCP_29") (pintype "bidirectional"))
    )
    (net (code "140") (name "Net-(IC22-5VOUT)") (class "Default")
      (node (ref "C59") (pin "2") (pinfunction "2_2") (pintype "passive"))
      (node (ref "IC22") (pin "25") (pinfunction "5VOUT_25") (pintype "bidirectional"))
      (node (ref "R43") (pin "1") (pinfunction "1_1") (pintype "passive"))
    )
    (net (code "141") (name "Net-(IC22-AIN_IREF)") (class "Default")
      (node (ref "C60") (pin "1") (pinfunction "1_1") (pintype "passive"))
      (node (ref "IC22") (pin "23") (pinfunction "AIN_IREF_23") (pintype "bidirectional"))
      (node (ref "R44") (pin "1") (pinfunction "1_1") (pintype "passive"))
    )
    (net (code "142") (name "Net-(IC22-BRA)") (class "Default")
      (node (ref "IC22") (pin "33") (pinfunction "BRA_33") (pintype "bidirectional"))
      (node (ref "R56") (pin "2") (pinfunction "2_2") (pintype "passive"))
    )
    (net (code "143") (name "Net-(IC22-BRB)") (class "Default")
      (node (ref "IC22") (pin "14") (pinfunction "BRB_14") (pintype "bidirectional"))
      (node (ref "R57") (pin "2") (pinfunction "2_2") (pintype "passive"))
    )
    (net (code "144") (name "Net-(IC22-CPI)") (class "Default")
      (node (ref "C57") (pin "1") (pinfunction "1_1") (pintype "passive"))
      (node (ref "IC22") (pin "28") (pinfunction "CPI_28") (pintype "bidirectional"))
    )
    (net (code "145") (name "Net-(IC22-CPO)") (class "Default")
      (node (ref "C57") (pin "2") (pinfunction "2_2") (pintype "passive"))
      (node (ref "IC22") (pin "27") (pinfunction "CPO_27") (pintype "bidirectional"))
    )
    (net (code "146") (name "Net-(IC22-ENCA_DCIN_CFG5)") (class "Default")
      (node (ref "IC22") (pin "19") (pinfunction "ENCA_DCIN_CFG5_19") (pintype "bidirectional"))
      (node (ref "U10") (pin "1") (pinfunction "QB_1") (pintype "output"))
    )
    (net (code "147") (name "Net-(IC22-ENCB_DCEN_CFG4)") (class "Default")
      (node (ref "IC22") (pin "18") (pinfunction "ENCB_DCEN_CFG4_18") (pintype "bidirectional"))
      (node (ref "U10") (pin "2") (pinfunction "QC_2") (pintype "output"))
    )
    (net (code "148") (name "Net-(IC22-OA1)") (class "Default")
      (node (ref "IC22") (pin "34") (pinfunction "OA1_34") (pintype "bidirectional"))
      (node (ref "J500") (pin "2") (pinfunction "S_2") (pintype "passive"))
    )
    (net (code "149") (name "Net-(IC22-OA2)") (class "Default")
      (node (ref "IC22") (pin "32") (pinfunction "OA2_32") (pintype "bidirectional"))
      (node (ref "J500") (pin "1") (pinfunction "S_1") (pintype "passive"))
    )
    (net (code "150") (name "Net-(IC22-OB1)") (class "Default")
      (node (ref "IC22") (pin "13") (pinfunction "OB1_13") (pintype "bidirectional"))
      (node (ref "J500") (pin "3") (pinfunction "S_3") (pintype "passive"))
    )
    (net (code "151") (name "Net-(IC22-OB2)") (class "Default")
      (node (ref "IC22") (pin "15") (pinfunction "OB2_15") (pintype "bidirectional"))
      (node (ref "J500") (pin "4") (pinfunction "S_4") (pintype "passive"))
    )
    (net (code "152") (name "Net-(IC22-SDO_NAO_CFG0)") (class "Default")
      (node (ref "IC22") (pin "5") (pinfunction "SDO_NAO_CFG0_5") (pintype "bidirectional"))
      (node (ref "U10") (pin "3") (pinfunction "QD_3") (pintype "output"))
    )
    (net (code "153") (name "Net-(IC22-VCC)") (class "Default")
      (node (ref "C58") (pin "1") (pinfunction "1_1") (pintype "passive"))
      (node (ref "IC22") (pin "26") (pinfunction "VCC_26") (pintype "bidirectional"))
      (node (ref "R43") (pin "2") (pinfunction "2_2") (pintype "passive"))
    )
    (net (code "154") (name "Net-(IC22-VCP)") (class "Default")
      (node (ref "C72") (pin "1") (pinfunction "1_1") (pintype "passive"))
      (node (ref "IC22") (pin "29") (pinfunction "VCP_29") (pintype "bidirectional"))
    )
    (net (code "155") (name "Net-(LED1-PadA)") (class "Default")
      (node (ref "LED1") (pin "A") (pinfunction "A_A") (pintype "passive"))
      (node (ref "R15") (pin "1") (pinfunction "1_1") (pintype "passive"))
    )
    (net (code "156") (name "Net-(LED2-PadA)") (class "Default")
      (node (ref "LED2") (pin "A") (pinfunction "A_A") (pintype "passive"))
      (node (ref "R24") (pin "1") (pinfunction "1_1") (pintype "passive"))
    )
    (net (code "157") (name "Net-(LED3-PadA)") (class "Default")
      (node (ref "LED3") (pin "A") (pinfunction "A_A") (pintype "passive"))
      (node (ref "R26") (pin "1") (pinfunction "1_1") (pintype "passive"))
    )
    (net (code "158") (name "Net-(LED4-PadA)") (class "Default")
      (node (ref "LED4") (pin "A") (pinfunction "A_A") (pintype "passive"))
      (node (ref "R59") (pin "1") (pinfunction "1_1") (pintype "passive"))
    )
    (net (code "159") (name "Net-(LED5-PadA)") (class "Default")
      (node (ref "LED5") (pin "A") (pinfunction "A_A") (pintype "passive"))
      (node (ref "R62") (pin "1") (pinfunction "1_1") (pintype "passive"))
    )
    (net (code "160") (name "Net-(LED6-PadA)") (class "Default")
      (node (ref "LED6") (pin "A") (pinfunction "A_A") (pintype "passive"))
      (node (ref "R63") (pin "1") (pinfunction "1_1") (pintype "passive"))
    )
    (net (code "161") (name "Net-(LED7-PadC)") (class "Default")
      (node (ref "LED7") (pin "C") (pinfunction "C_C") (pintype "passive"))
      (node (ref "R64") (pin "2") (pinfunction "2_2") (pintype "passive"))
    )
    (net (code "162") (name "Net-(Q4-C)") (class "Default")
      (node (ref "LED5") (pin "C") (pinfunction "C_C") (pintype "passive"))
      (node (ref "Q4") (pin "3") (pinfunction "C_3") (pintype "passive"))
      (node (ref "X15") (pin "2") (pinfunction "S_2") (pintype "passive"))
    )
    (net (code "163") (name "Net-(Q5-C)") (class "Default")
      (node (ref "LED6") (pin "C") (pinfunction "C_C") (pintype "passive"))
      (node (ref "Q5") (pin "3") (pinfunction "C_3") (pintype "passive"))
      (node (ref "X16") (pin "2") (pinfunction "S_2") (pintype "passive"))
    )
    (net (code "164") (name "Net-(U1-LED0)") (class "Default")
      (node (ref "SV1") (pin "1") (pinfunction "1_1") (pintype "passive"))
      (node (ref "U1") (pin "6") (pinfunction "LED0_6") (pintype "output"))
    )
    (net (code "165") (name "Net-(U1-LED1)") (class "Default")
      (node (ref "SV1") (pin "2") (pinfunction "2_2") (pintype "passive"))
      (node (ref "U1") (pin "7") (pinfunction "LED1_7") (pintype "output"))
    )
    (net (code "166") (name "Net-(U1-LED2)") (class "Default")
      (node (ref "SV1") (pin "3") (pinfunction "3_3") (pintype "passive"))
      (node (ref "U1") (pin "8") (pinfunction "LED2_8") (pintype "output"))
    )
    (net (code "167") (name "Net-(U4-BOOT)") (class "Default")
      (node (ref "C16") (pin "1") (pinfunction "1_1") (pintype "passive"))
      (node (ref "U4") (pin "2") (pinfunction "BOOT_2") (pintype "input"))
    )
    (net (code "168") (name "Net-(U4-COMP)") (class "Default")
      (node (ref "C14") (pin "1") (pinfunction "1_1") (pintype "passive"))
      (node (ref "U4") (pin "8") (pinfunction "COMP_8") (pintype "bidirectional"))
    )
    (net (code "169") (name "Net-(U4-FB)") (class "Default")
      (node (ref "R16") (pin "1") (pinfunction "1_1") (pintype "passive"))
      (node (ref "R17") (pin "2") (pinfunction "2_2") (pintype "passive"))
      (node (ref "U4") (pin "7") (pinfunction "FB_7") (pintype "input"))
    )
    (net (code "170") (name "Net-(U4-SS)") (class "Default")
      (node (ref "C15") (pin "1") (pinfunction "1_1") (pintype "passive"))
      (node (ref "U4") (pin "10") (pinfunction "SS_10") (pintype "bidirectional"))
    )
    (net (code "171") (name "Net-(U4-SW)") (class "Default")
      (node (ref "C16") (pin "2") (pinfunction "2_2") (pintype "passive"))
      (node (ref "D2") (pin "C") (pinfunction "C_C") (pintype "passive"))
      (node (ref "L2") (pin "P$2") (pinfunction "P$2_P$2") (pintype "passive"))
      (node (ref "U4") (pin "5") (pinfunction "SW_5") (pintype "power_in"))
    )
    (net (code "172") (name "Net-(U5-BOOT)") (class "Default")
      (node (ref "C21") (pin "1") (pinfunction "1_1") (pintype "passive"))
      (node (ref "U5") (pin "2") (pinfunction "BOOT_2") (pintype "input"))
    )
    (net (code "173") (name "Net-(U5-COMP)") (class "Default")
      (node (ref "C17") (pin "1") (pinfunction "1_1") (pintype "passive"))
      (node (ref "U5") (pin "8") (pinfunction "COMP_8") (pintype "bidirectional"))
    )
    (net (code "174") (name "Net-(U5-FB)") (class "Default")
      (node (ref "R18") (pin "1") (pinfunction "1_1") (pintype "passive"))
      (node (ref "R19") (pin "2") (pinfunction "2_2") (pintype "passive"))
      (node (ref "U5") (pin "7") (pinfunction "FB_7") (pintype "input"))
    )
    (net (code "175") (name "Net-(U5-SS)") (class "Default")
      (node (ref "C20") (pin "1") (pinfunction "1_1") (pintype "passive"))
      (node (ref "U5") (pin "10") (pinfunction "SS_10") (pintype "bidirectional"))
    )
    (net (code "176") (name "Net-(U5-SW)") (class "Default")
      (node (ref "C21") (pin "2") (pinfunction "2_2") (pintype "passive"))
      (node (ref "D4") (pin "C") (pinfunction "C_C") (pintype "passive"))
      (node (ref "L1") (pin "P$2") (pinfunction "P$2_P$2") (pintype "passive"))
      (node (ref "U5") (pin "5") (pinfunction "SW_5") (pintype "power_in"))
    )
    (net (code "177") (name "Net-(X3B-S)") (class "Default")
      (node (ref "R11") (pin "1") (pinfunction "1_1") (pintype "passive"))
      (node (ref "R12") (pin "1") (pinfunction "1_1") (pintype "passive"))
      (node (ref "X3") (pin "2") (pinfunction "S_2") (pintype "passive"))
    )
    (net (code "178") (name "Net-(X4B-S)") (class "Default")
      (node (ref "R13") (pin "1") (pinfunction "1_1") (pintype "passive"))
      (node (ref "R14") (pin "1") (pinfunction "1_1") (pintype "passive"))
      (node (ref "X4") (pin "2") (pinfunction "S_2") (pintype "passive"))
    )
    (net (code "179") (name "Net-(X11B-1)") (class "Default")
      (node (ref "C3") (pin "1") (pinfunction "1_1") (pintype "passive"))
      (node (ref "D1") (pin "A") (pinfunction "A_A") (pintype "passive"))
      (node (ref "LED1") (pin "C") (pinfunction "C_C") (pintype "passive"))
      (node (ref "Q1") (pin "5") (pinfunction "D_5") (pintype "passive"))
      (node (ref "Q1") (pin "6") (pinfunction "D_6") (pintype "passive"))
      (node (ref "Q1") (pin "7") (pinfunction "D_7") (pintype "passive"))
      (node (ref "Q1") (pin "8") (pinfunction "D_8") (pintype "passive"))
      (node (ref "Q1") (pin "TH") (pinfunction "D_TH") (pintype "passive"))
      (node (ref "R8") (pin "1") (pinfunction "1_1") (pintype "passive"))
      (node (ref "X11") (pin "2") (pinfunction "1_2") (pintype "passive"))
    )
    (net (code "180") (name "Net-(X12C-1)") (class "Default")
      (node (ref "C32") (pin "1") (pinfunction "1_1") (pintype "passive"))
      (node (ref "D3") (pin "A") (pinfunction "A_A") (pintype "passive"))
      (node (ref "LED3") (pin "C") (pinfunction "C_C") (pintype "passive"))
      (node (ref "Q2") (pin "5") (pinfunction "D_5") (pintype "passive"))
      (node (ref "Q2") (pin "6") (pinfunction "D_6") (pintype "passive"))
      (node (ref "Q2") (pin "7") (pinfunction "D_7") (pintype "passive"))
      (node (ref "Q2") (pin "8") (pinfunction "D_8") (pintype "passive"))
      (node (ref "Q2") (pin "TH") (pinfunction "D_TH") (pintype "passive"))
      (node (ref "R25") (pin "1") (pinfunction "1_1") (pintype "passive"))
      (node (ref "X12") (pin "3") (pinfunction "1_3") (pintype "passive"))
      (node (ref "X12") (pin "4") (pinfunction "1_4") (pintype "passive"))
    )
    (net (code "181") (name "SERVO_0") (class "Default")
      (node (ref "IC2") (pin "2") (pinfunction "I_2") (pintype "input"))
      (node (ref "P1") (pin "14") (pinfunction "14_14") (pintype "passive"))
    )
    (net (code "182") (name "SERVO_0_EN") (class "Default")
      (node (ref "IC2") (pin "1") (pinfunction "OE_1") (pintype "input"))
      (node (ref "U7") (pin "15") (pinfunction "QA_15") (pintype "output"))
    )
    (net (code "183") (name "SERVO_1") (class "Default")
      (node (ref "IC1") (pin "2") (pinfunction "I_2") (pintype "input"))
      (node (ref "P1") (pin "16") (pinfunction "16_16") (pintype "passive"))
    )
    (net (code "184") (name "SERVO_1_EN") (class "Default")
      (node (ref "IC1") (pin "1") (pinfunction "OE_1") (pintype "input"))
      (node (ref "U8") (pin "15") (pinfunction "QA_15") (pintype "output"))
    )
    (net (code "185") (name "SER_2") (class "Default")
      (node (ref "U6") (pin "9") (pinfunction "QH_2_9") (pintype "output"))
      (node (ref "U7") (pin "14") (pinfunction "SER_14") (pintype "input"))
    )
    (net (code "186") (name "SER_3") (class "Default")
      (node (ref "U7") (pin "9") (pinfunction "QH_2_9") (pintype "output"))
      (node (ref "U8") (pin "14") (pinfunction "SER_14") (pintype "input"))
    )
    (net (code "187") (name "SER_4") (class "Default")
      (node (ref "U8") (pin "9") (pinfunction "QH_2_9") (pintype "output"))
      (node (ref "U9") (pin "14") (pinfunction "SER_14") (pintype "input"))
    )
    (net (code "188") (name "SER_5") (class "Default")
      (node (ref "U10") (pin "14") (pinfunction "SER_14") (pintype "input"))
      (node (ref "U9") (pin "9") (pinfunction "QH_2_9") (pintype "output"))
    )
    (net (code "189") (name "SPI1_CS1") (class "Default")
      (node (ref "P1") (pin "42") (pinfunction "42_42") (pintype "passive"))
      (node (ref "U10") (pin "12") (pinfunction "RCLK_12") (pintype "input"))
      (node (ref "U6") (pin "12") (pinfunction "RCLK_12") (pintype "input"))
      (node (ref "U7") (pin "12") (pinfunction "RCLK_12") (pintype "input"))
      (node (ref "U8") (pin "12") (pinfunction "RCLK_12") (pintype "input"))
      (node (ref "U9") (pin "12") (pinfunction "RCLK_12") (pintype "input"))
    )
    (net (code "190") (name "SPI1_MOSI") (class "Default")
      (node (ref "P1") (pin "30") (pinfunction "30_30") (pintype "passive"))
      (node (ref "U6") (pin "14") (pinfunction "SER_14") (pintype "input"))
    )
    (net (code "191") (name "SPI1_SCLK") (class "Default")
      (node (ref "P1") (pin "31") (pinfunction "31_31") (pintype "passive"))
      (node (ref "U10") (pin "11") (pinfunction "SRCLK_11") (pintype "input"))
      (node (ref "U6") (pin "11") (pinfunction "SRCLK_11") (pintype "input"))
      (node (ref "U7") (pin "11") (pinfunction "SRCLK_11") (pintype "input"))
      (node (ref "U8") (pin "11") (pinfunction "SRCLK_11") (pintype "input"))
      (node (ref "U9") (pin "11") (pinfunction "SRCLK_11") (pintype "input"))
    )
    (net (code "192") (name "STEP_E") (class "Default")
      (node (ref "IC21") (pin "6") (pinfunction "REFL_STEP_6") (pintype "bidirectional"))
      (node (ref "P1") (pin "12") (pinfunction "12_12") (pintype "passive"))
    )
    (net (code "193") (name "STEP_H") (class "Default")
      (node (ref "IC22") (pin "6") (pinfunction "REFL_STEP_6") (pintype "bidirectional"))
      (node (ref "P2") (pin "11") (pinfunction "11_11") (pintype "passive"))
    )
    (net (code "194") (name "STEP_X") (class "Default")
      (node (ref "IC18") (pin "6") (pinfunction "REFL_STEP_6") (pintype "bidirectional"))
      (node (ref "P2") (pin "17") (pinfunction "17_17") (pintype "passive"))
    )
    (net (code "195") (name "STEP_Y") (class "Default")
      (node (ref "IC19") (pin "6") (pinfunction "REFL_STEP_6") (pintype "bidirectional"))
      (node (ref "P2") (pin "12") (pinfunction "12_12") (pintype "passive"))
    )
    (net (code "196") (name "STEP_Z") (class "Default")
      (node (ref "IC20") (pin "6") (pinfunction "REFL_STEP_6") (pintype "bidirectional"))
      (node (ref "P2") (pin "13") (pinfunction "13_13") (pintype "passive"))
    )
    (net (code "197") (name "SYS_5V") (class "Default")
      (node (ref "C18") (pin "1") (pinfunction "1_1") (pintype "passive"))
      (node (ref "P1") (pin "7") (pinfunction "7_7") (pintype "passive"))
      (node (ref "P1") (pin "8") (pinfunction "8_8") (pintype "passive"))
      (node (ref "U1") (pin "1") (pinfunction "A0_1") (pintype "input"))
      (node (ref "U1") (pin "2") (pinfunction "A1_2") (pintype "input"))
      (node (ref "U1") (pin "24") (pinfunction "A5_24") (pintype "input"))
      (node (ref "U1") (pin "28") (pinfunction "VDD_28") (pintype "power_in"))
      (node (ref "U1") (pin "3") (pinfunction "A2_3") (pintype "input"))
      (node (ref "U1") (pin "4") (pinfunction "A3_4") (pintype "input"))
      (node (ref "U1") (pin "5") (pinfunction "A4_5") (pintype "input"))
    )
    (net (code "198") (name "TERM_EXT1") (class "Default")
      (node (ref "C4") (pin "1") (pinfunction "1_1") (pintype "passive"))
      (node (ref "P1") (pin "33") (pinfunction "33_33") (pintype "passive"))
      (node (ref "R10") (pin "2") (pinfunction "2_2") (pintype "passive"))
    )
    (net (code "199") (name "TERM_EXT2") (class "Default")
      (node (ref "C6") (pin "1") (pinfunction "1_1") (pintype "passive"))
      (node (ref "P1") (pin "36") (pinfunction "36_36") (pintype "passive"))
      (node (ref "R14") (pin "2") (pinfunction "2_2") (pintype "passive"))
    )
    (net (code "200") (name "TERM_HBP") (class "Default")
      (node (ref "C5") (pin "1") (pinfunction "1_1") (pintype "passive"))
      (node (ref "P1") (pin "35") (pinfunction "35_35") (pintype "passive"))
      (node (ref "R11") (pin "2") (pinfunction "2_2") (pintype "passive"))
    )
    (net (code "201") (name "THERM_EXT1_IN") (class "Default")
      (node (ref "R10") (pin "1") (pinfunction "1_1") (pintype "passive"))
      (node (ref "R9") (pin "1") (pinfunction "1_1") (pintype "passive"))
      (node (ref "X2") (pin "2") (pinfunction "S_2") (pintype "passive"))
    )
    (net (code "202") (name "TRISTATE_STEPPERS") (class "Default")
      (node (ref "IC3") (pin "1") (pinfunction "OE_1") (pintype "input"))
      (node (ref "IC4") (pin "1") (pinfunction "OE_1") (pintype "input"))
      (node (ref "IC5") (pin "1") (pinfunction "OE_1") (pintype "input"))
      (node (ref "IC6") (pin "1") (pinfunction "OE_1") (pintype "input"))
      (node (ref "IC7") (pin "1") (pinfunction "OE_1") (pintype "input"))
      (node (ref "U10") (pin "15") (pinfunction "QA_15") (pintype "output"))
    )
    (net (code "203") (name "VDD_5V") (class "Default")
      (node (ref "5V") (pin "TP") (pinfunction "TP_TP") (pintype "input"))
      (node (ref "C10") (pin "1") (pinfunction "1_1") (pintype "passive"))
      (node (ref "C12") (pin "1") (pinfunction "1_1") (pintype "passive"))
      (node (ref "C13") (pin "1") (pinfunction "1_1") (pintype "passive"))
      (node (ref "C8") (pin "1") (pinfunction "1_1") (pintype "passive"))
      (node (ref "IC1") (pin "5") (pinfunction "VCC_5") (pintype "power_in"))
      (node (ref "IC2") (pin "5") (pinfunction "VCC_5") (pintype "power_in"))
      (node (ref "L2") (pin "P$1") (pinfunction "P$1_P$1") (pintype "passive"))
      (node (ref "P1") (pin "5") (pinfunction "5_5") (pintype "passive"))
      (node (ref "P1") (pin "6") (pinfunction "6_6") (pintype "passive"))
      (node (ref "R1") (pin "2") (pinfunction "2_2") (pintype "passive"))
      (node (ref "R17") (pin "1") (pinfunction "1_1") (pintype "passive"))
      (node (ref "R2") (pin "2") (pinfunction "2_2") (pintype "passive"))
      (node (ref "R3") (pin "2") (pinfunction "2_2") (pintype "passive"))
      (node (ref "R4") (pin "2") (pinfunction "2_2") (pintype "passive"))
      (node (ref "R5") (pin "2") (pinfunction "2_2") (pintype "passive"))
      (node (ref "R6") (pin "2") (pinfunction "2_2") (pintype "passive"))
      (node (ref "X10") (pin "3") (pinfunction "S_3") (pintype "passive"))
      (node (ref "X5") (pin "3") (pinfunction "S_3") (pintype "passive"))
      (node (ref "X6") (pin "3") (pinfunction "S_3") (pintype "passive"))
      (node (ref "X7") (pin "3") (pinfunction "S_3") (pintype "passive"))
      (node (ref "X8") (pin "3") (pinfunction "S_3") (pintype "passive"))
      (node (ref "X9") (pin "3") (pinfunction "S_3") (pintype "passive"))
    )
    (net (code "204") (name "VDD_12V") (class "Default")
      (node (ref "12V") (pin "TP") (pinfunction "TP_TP") (pintype "input"))
      (node (ref "C1") (pin "1") (pinfunction "1_1") (pintype "passive"))
      (node (ref "C2") (pin "1") (pinfunction "1_1") (pintype "passive"))
      (node (ref "L1") (pin "P$1") (pinfunction "P$1_P$1") (pintype "passive"))
      (node (ref "R19") (pin "1") (pinfunction "1_1") (pintype "passive"))
      (node (ref "R24") (pin "2") (pinfunction "2_2") (pintype "passive"))
      (node (ref "X10") (pin "4") (pinfunction "S_4") (pintype "passive"))
    )
    (net (code "205") (name "VDD_ADC") (class "Default")
      (node (ref "P1") (pin "32") (pinfunction "32_32") (pintype "passive"))
      (node (ref "R12") (pin "2") (pinfunction "2_2") (pintype "passive"))
      (node (ref "R13") (pin "2") (pinfunction "2_2") (pintype "passive"))
      (node (ref "R9") (pin "2") (pinfunction "2_2") (pintype "passive"))
    )
    (net (code "206") (name "VDD_IN") (class "Default")
      (node (ref "12..24V") (pin "TP") (pinfunction "TP_TP") (pintype "input"))
      (node (ref "C11") (pin "1") (pinfunction "1_1") (pintype "passive"))
      (node (ref "C64") (pin "2") (pinfunction "2_2") (pintype "passive"))
      (node (ref "C65") (pin "2") (pinfunction "2_2") (pintype "passive"))
      (node (ref "C66") (pin "2") (pinfunction "2_2") (pintype "passive"))
      (node (ref "C67") (pin "2") (pinfunction "2_2") (pintype "passive"))
      (node (ref "C68") (pin "2") (pinfunction "2_2") (pintype "passive"))
      (node (ref "C69") (pin "2") (pinfunction "2_2") (pintype "passive"))
      (node (ref "C70") (pin "2") (pinfunction "2_2") (pintype "passive"))
      (node (ref "C71") (pin "2") (pinfunction "2_2") (pintype "passive"))
      (node (ref "C72") (pin "2") (pinfunction "2_2") (pintype "passive"))
      (node (ref "C73") (pin "2") (pinfunction "2_2") (pintype "passive"))
      (node (ref "C74") (pin "1") (pinfunction "1_1") (pintype "passive"))
      (node (ref "C75") (pin "1") (pinfunction "1_1") (pintype "passive"))
      (node (ref "C76") (pin "1") (pinfunction "1_1") (pintype "passive"))
      (node (ref "C77") (pin "1") (pinfunction "1_1") (pintype "passive"))
      (node (ref "C78") (pin "1") (pinfunction "1_1") (pintype "passive"))
      (node (ref "C79") (pin "+") (pinfunction "+_+") (pintype "passive"))
      (node (ref "C80") (pin "+") (pinfunction "+_+") (pintype "passive"))
      (node (ref "C81") (pin "+") (pinfunction "+_+") (pintype "passive"))
      (node (ref "C82") (pin "+") (pinfunction "+_+") (pintype "passive"))
      (node (ref "C83") (pin "+") (pinfunction "+_+") (pintype "passive"))
      (node (ref "C84") (pin "1") (pinfunction "1_1") (pintype "passive"))
      (node (ref "C85") (pin "1") (pinfunction "1_1") (pintype "passive"))
      (node (ref "C86") (pin "1") (pinfunction "1_1") (pintype "passive"))
      (node (ref "C87") (pin "1") (pinfunction "1_1") (pintype "passive"))
      (node (ref "C88") (pin "1") (pinfunction "1_1") (pintype "passive"))
      (node (ref "C89") (pin "1") (pinfunction "1_1") (pintype "passive"))
      (node (ref "C9") (pin "1") (pinfunction "1_1") (pintype "passive"))
      (node (ref "C90") (pin "1") (pinfunction "1_1") (pintype "passive"))
      (node (ref "C91") (pin "1") (pinfunction "1_1") (pintype "passive"))
      (node (ref "C92") (pin "1") (pinfunction "1_1") (pintype "passive"))
      (node (ref "C93") (pin "1") (pinfunction "1_1") (pintype "passive"))
      (node (ref "D1") (pin "C") (pinfunction "C_C") (pintype "passive"))
      (node (ref "D3") (pin "C") (pinfunction "C_C") (pintype "passive"))
      (node (ref "D5") (pin "C") (pinfunction "C_C") (pintype "passive"))
      (node (ref "D6") (pin "C") (pinfunction "C_C") (pintype "passive"))
      (node (ref "F1") (pin "P$3") (pinfunction "2_P$3") (pintype "passive"))
      (node (ref "F1") (pin "P$4") (pinfunction "2_P$4") (pintype "passive"))
      (node (ref "IC18") (pin "16") (pinfunction "VS_16") (pintype "bidirectional"))
      (node (ref "IC18") (pin "30") (pinfunction "VSA_30") (pintype "bidirectional"))
      (node (ref "IC18") (pin "31") (pinfunction "VS_31") (pintype "bidirectional"))
      (node (ref "IC19") (pin "16") (pinfunction "VS_16") (pintype "bidirectional"))
      (node (ref "IC19") (pin "30") (pinfunction "VSA_30") (pintype "bidirectional"))
      (node (ref "IC19") (pin "31") (pinfunction "VS_31") (pintype "bidirectional"))
      (node (ref "IC20") (pin "16") (pinfunction "VS_16") (pintype "bidirectional"))
      (node (ref "IC20") (pin "30") (pinfunction "VSA_30") (pintype "bidirectional"))
      (node (ref "IC20") (pin "31") (pinfunction "VS_31") (pintype "bidirectional"))
      (node (ref "IC21") (pin "16") (pinfunction "VS_16") (pintype "bidirectional"))
      (node (ref "IC21") (pin "30") (pinfunction "VSA_30") (pintype "bidirectional"))
      (node (ref "IC21") (pin "31") (pinfunction "VS_31") (pintype "bidirectional"))
      (node (ref "IC22") (pin "16") (pinfunction "VS_16") (pintype "bidirectional"))
      (node (ref "IC22") (pin "30") (pinfunction "VSA_30") (pintype "bidirectional"))
      (node (ref "IC22") (pin "31") (pinfunction "VS_31") (pintype "bidirectional"))
      (node (ref "R15") (pin "2") (pinfunction "2_2") (pintype "passive"))
      (node (ref "R25") (pin "2") (pinfunction "2_2") (pintype "passive"))
      (node (ref "R26") (pin "2") (pinfunction "2_2") (pintype "passive"))
      (node (ref "R58") (pin "2") (pinfunction "2_2") (pintype "passive"))
      (node (ref "R59") (pin "2") (pinfunction "2_2") (pintype "passive"))
      (node (ref "R62") (pin "2") (pinfunction "2_2") (pintype "passive"))
      (node (ref "R63") (pin "2") (pinfunction "2_2") (pintype "passive"))
      (node (ref "R64") (pin "1") (pinfunction "1_1") (pintype "passive"))
      (node (ref "R8") (pin "2") (pinfunction "2_2") (pintype "passive"))
      (node (ref "U4") (pin "4") (pinfunction "VIN_4") (pintype "power_in"))
      (node (ref "U5") (pin "4") (pinfunction "VIN_4") (pintype "power_in"))
      (node (ref "X11") (pin "1") (pinfunction "1_1") (pintype "passive"))
      (node (ref "X12") (pin "1") (pinfunction "1_1") (pintype "passive"))
      (node (ref "X12") (pin "2") (pinfunction "1_2") (pintype "passive"))
      (node (ref "X13") (pin "1") (pinfunction "1_1") (pintype "passive"))
      (node (ref "X15") (pin "1") (pinfunction "S_1") (pintype "passive"))
      (node (ref "X16") (pin "1") (pinfunction "S_1") (pintype "passive"))
    )
    (net (code "207") (name "VIN") (class "Default")
      (node (ref "F1") (pin "P$1") (pinfunction "1_P$1") (pintype "passive"))
      (node (ref "F1") (pin "P$2") (pinfunction "1_P$2") (pintype "passive"))
      (node (ref "LED7") (pin "A") (pinfunction "A_A") (pintype "passive"))
      (node (ref "X14") (pin "3") (pinfunction "1_3") (pintype "passive"))
      (node (ref "X14") (pin "4") (pinfunction "1_4") (pintype "passive"))
    )
    (net (code "208") (name "X_A1") (class "Default")
      (node (ref "IC18") (pin "34") (pinfunction "OA1_34") (pintype "bidirectional"))
      (node (ref "J504") (pin "2") (pinfunction "S_2") (pintype "passive"))
    )
    (net (code "209") (name "X_A2") (class "Default")
      (node (ref "IC18") (pin "32") (pinfunction "OA2_32") (pintype "bidirectional"))
      (node (ref "J504") (pin "1") (pinfunction "S_1") (pintype "passive"))
    )
    (net (code "210") (name "X_B1") (class "Default")
      (node (ref "IC18") (pin "13") (pinfunction "OB1_13") (pintype "bidirectional"))
      (node (ref "J504") (pin "3") (pinfunction "S_3") (pintype "passive"))
    )
    (net (code "211") (name "X_B2") (class "Default")
      (node (ref "IC18") (pin "15") (pinfunction "OB2_15") (pintype "bidirectional"))
      (node (ref "J504") (pin "4") (pinfunction "S_4") (pintype "passive"))
    )
    (net (code "212") (name "unconnected-(IC18-CSN_CFG3-Pad2)") (class "Default")
      (node (ref "IC18") (pin "2") (pinfunction "CSN_CFG3_2") (pintype "bidirectional"))
    )
    (net (code "213") (name "unconnected-(IC18-ENCN_DCO-Pad17)") (class "Default")
      (node (ref "IC18") (pin "17") (pinfunction "ENCN_DCO_17") (pintype "bidirectional"))
    )
    (net (code "214") (name "unconnected-(IC18-SD_MODE-Pad9)") (class "Default")
      (node (ref "IC18") (pin "9") (pinfunction "SD_MODE_9") (pintype "bidirectional"))
    )
    (net (code "215") (name "unconnected-(IC18-SWP_DIAG1-Pad21)") (class "Default")
      (node (ref "IC18") (pin "21") (pinfunction "SWP_DIAG1_21") (pintype "bidirectional"))
    )
    (net (code "216") (name "unconnected-(IC19-CSN_CFG3-Pad2)") (class "Default")
      (node (ref "IC19") (pin "2") (pinfunction "CSN_CFG3_2") (pintype "bidirectional"))
    )
    (net (code "217") (name "unconnected-(IC19-ENCN_DCO-Pad17)") (class "Default")
      (node (ref "IC19") (pin "17") (pinfunction "ENCN_DCO_17") (pintype "bidirectional"))
    )
    (net (code "218") (name "unconnected-(IC19-SD_MODE-Pad9)") (class "Default")
      (node (ref "IC19") (pin "9") (pinfunction "SD_MODE_9") (pintype "bidirectional"))
    )
    (net (code "219") (name "unconnected-(IC19-SWP_DIAG1-Pad21)") (class "Default")
      (node (ref "IC19") (pin "21") (pinfunction "SWP_DIAG1_21") (pintype "bidirectional"))
    )
    (net (code "220") (name "unconnected-(IC20-CSN_CFG3-Pad2)") (class "Default")
      (node (ref "IC20") (pin "2") (pinfunction "CSN_CFG3_2") (pintype "bidirectional"))
    )
    (net (code "221") (name "unconnected-(IC20-ENCN_DCO-Pad17)") (class "Default")
      (node (ref "IC20") (pin "17") (pinfunction "ENCN_DCO_17") (pintype "bidirectional"))
    )
    (net (code "222") (name "unconnected-(IC20-SD_MODE-Pad9)") (class "Default")
      (node (ref "IC20") (pin "9") (pinfunction "SD_MODE_9") (pintype "bidirectional"))
    )
    (net (code "223") (name "unconnected-(IC20-SWP_DIAG1-Pad21)") (class "Default")
      (node (ref "IC20") (pin "21") (pinfunction "SWP_DIAG1_21") (pintype "bidirectional"))
    )
    (net (code "224") (name "unconnected-(IC21-CSN_CFG3-Pad2)") (class "Default")
      (node (ref "IC21") (pin "2") (pinfunction "CSN_CFG3_2") (pintype "bidirectional"))
    )
    (net (code "225") (name "unconnected-(IC21-ENCN_DCO-Pad17)") (class "Default")
      (node (ref "IC21") (pin "17") (pinfunction "ENCN_DCO_17") (pintype "bidirectional"))
    )
    (net (code "226") (name "unconnected-(IC21-SD_MODE-Pad9)") (class "Default")
      (node (ref "IC21") (pin "9") (pinfunction "SD_MODE_9") (pintype "bidirectional"))
    )
    (net (code "227") (name "unconnected-(IC21-SWP_DIAG1-Pad21)") (class "Default")
      (node (ref "IC21") (pin "21") (pinfunction "SWP_DIAG1_21") (pintype "bidirectional"))
    )
    (net (code "228") (name "unconnected-(IC22-CSN_CFG3-Pad2)") (class "Default")
      (node (ref "IC22") (pin "2") (pinfunction "CSN_CFG3_2") (pintype "bidirectional"))
    )
    (net (code "229") (name "unconnected-(IC22-ENCN_DCO-Pad17)") (class "Default")
      (node (ref "IC22") (pin "17") (pinfunction "ENCN_DCO_17") (pintype "bidirectional"))
    )
    (net (code "230") (name "unconnected-(IC22-SD_MODE-Pad9)") (class "Default")
      (node (ref "IC22") (pin "9") (pinfunction "SD_MODE_9") (pintype "bidirectional"))
    )
    (net (code "231") (name "unconnected-(IC22-SWP_DIAG1-Pad21)") (class "Default")
      (node (ref "IC22") (pin "21") (pinfunction "SWP_DIAG1_21") (pintype "bidirectional"))
    )
    (net (code "232") (name "unconnected-(P1-Pad9)") (class "Default")
      (node (ref "P1") (pin "9") (pinfunction "9_9") (pintype "passive"))
    )
    (net (code "233") (name "unconnected-(P1-Pad10)") (class "Default")
      (node (ref "P1") (pin "10") (pinfunction "10_10") (pintype "passive"))
    )
    (net (code "234") (name "unconnected-(P1-Pad15)") (class "Default")
      (node (ref "P1") (pin "15") (pinfunction "15_15") (pintype "passive"))
    )
    (net (code "235") (name "unconnected-(P1-Pad17)") (class "Default")
      (node (ref "P1") (pin "17") (pinfunction "17_17") (pintype "passive"))
    )
    (net (code "236") (name "unconnected-(P1-Pad21)") (class "Default")
      (node (ref "P1") (pin "21") (pinfunction "21_21") (pintype "passive"))
    )
    (net (code "237") (name "unconnected-(P1-Pad26)") (class "Default")
      (node (ref "P1") (pin "26") (pinfunction "26_26") (pintype "passive"))
    )
    (net (code "238") (name "unconnected-(P1-Pad27)") (class "Default")
      (node (ref "P1") (pin "27") (pinfunction "27_27") (pintype "passive"))
    )
    (net (code "239") (name "unconnected-(P1-Pad29)") (class "Default")
      (node (ref "P1") (pin "29") (pinfunction "29_29") (pintype "passive"))
    )
    (net (code "240") (name "unconnected-(P1-Pad34)") (class "Default")
      (node (ref "P1") (pin "34") (pinfunction "34_34") (pintype "passive"))
    )
    (net (code "241") (name "unconnected-(P1-Pad37)") (class "Default")
      (node (ref "P1") (pin "37") (pinfunction "37_37") (pintype "passive"))
    )
    (net (code "242") (name "unconnected-(P1-Pad38)") (class "Default")
      (node (ref "P1") (pin "38") (pinfunction "38_38") (pintype "passive"))
    )
    (net (code "243") (name "unconnected-(P1-Pad39)") (class "Default")
      (node (ref "P1") (pin "39") (pinfunction "39_39") (pintype "passive"))
    )
    (net (code "244") (name "unconnected-(P1-Pad40)") (class "Default")
      (node (ref "P1") (pin "40") (pinfunction "40_40") (pintype "passive"))
    )
    (net (code "245") (name "unconnected-(P2-Pad3)") (class "Default")
      (node (ref "P2") (pin "3") (pinfunction "3_3") (pintype "passive"))
    )
    (net (code "246") (name "unconnected-(P2-Pad4)") (class "Default")
      (node (ref "P2") (pin "4") (pinfunction "4_4") (pintype "passive"))
    )
    (net (code "247") (name "unconnected-(P2-Pad5)") (class "Default")
      (node (ref "P2") (pin "5") (pinfunction "5_5") (pintype "passive"))
    )
    (net (code "248") (name "unconnected-(P2-Pad6)") (class "Default")
      (node (ref "P2") (pin "6") (pinfunction "6_6") (pintype "passive"))
    )
    (net (code "249") (name "unconnected-(P2-Pad7)") (class "Default")
      (node (ref "P2") (pin "7") (pinfunction "7_7") (pintype "passive"))
    )
    (net (code "250") (name "unconnected-(P2-Pad20)") (class "Default")
      (node (ref "P2") (pin "20") (pinfunction "20_20") (pintype "passive"))
    )
    (net (code "251") (name "unconnected-(P2-Pad21)") (class "Default")
      (node (ref "P2") (pin "21") (pinfunction "21_21") (pintype "passive"))
    )
    (net (code "252") (name "unconnected-(P2-Pad22)") (class "Default")
      (node (ref "P2") (pin "22") (pinfunction "22_22") (pintype "passive"))
    )
    (net (code "253") (name "unconnected-(P2-Pad23)") (class "Default")
      (node (ref "P2") (pin "23") (pinfunction "23_23") (pintype "passive"))
    )
    (net (code "254") (name "unconnected-(P2-Pad24)") (class "Default")
      (node (ref "P2") (pin "24") (pinfunction "24_24") (pintype "passive"))
    )
    (net (code "255") (name "unconnected-(P2-Pad25)") (class "Default")
      (node (ref "P2") (pin "25") (pinfunction "25_25") (pintype "passive"))
    )
    (net (code "256") (name "unconnected-(P2-Pad27)") (class "Default")
      (node (ref "P2") (pin "27") (pinfunction "27_27") (pintype "passive"))
    )
    (net (code "257") (name "unconnected-(P2-Pad28)") (class "Default")
      (node (ref "P2") (pin "28") (pinfunction "28_28") (pintype "passive"))
    )
    (net (code "258") (name "unconnected-(P2-Pad29)") (class "Default")
      (node (ref "P2") (pin "29") (pinfunction "29_29") (pintype "passive"))
    )
    (net (code "259") (name "unconnected-(P2-Pad30)") (class "Default")
      (node (ref "P2") (pin "30") (pinfunction "30_30") (pintype "passive"))
    )
    (net (code "260") (name "unconnected-(P2-Pad31)") (class "Default")
      (node (ref "P2") (pin "31") (pinfunction "31_31") (pintype "passive"))
    )
    (net (code "261") (name "unconnected-(P2-Pad32)") (class "Default")
      (node (ref "P2") (pin "32") (pinfunction "32_32") (pintype "passive"))
    )
    (net (code "262") (name "unconnected-(P2-Pad33)") (class "Default")
      (node (ref "P2") (pin "33") (pinfunction "33_33") (pintype "passive"))
    )
    (net (code "263") (name "unconnected-(P2-Pad34)") (class "Default")
      (node (ref "P2") (pin "34") (pinfunction "34_34") (pintype "passive"))
    )
    (net (code "264") (name "unconnected-(P2-Pad35)") (class "Default")
      (node (ref "P2") (pin "35") (pinfunction "35_35") (pintype "passive"))
    )
    (net (code "265") (name "unconnected-(P2-Pad36)") (class "Default")
      (node (ref "P2") (pin "36") (pinfunction "36_36") (pintype "passive"))
    )
    (net (code "266") (name "unconnected-(P2-Pad37)") (class "Default")
      (node (ref "P2") (pin "37") (pinfunction "37_37") (pintype "passive"))
    )
    (net (code "267") (name "unconnected-(P2-Pad38)") (class "Default")
      (node (ref "P2") (pin "38") (pinfunction "38_38") (pintype "passive"))
    )
    (net (code "268") (name "unconnected-(P2-Pad39)") (class "Default")
      (node (ref "P2") (pin "39") (pinfunction "39_39") (pintype "passive"))
    )
    (net (code "269") (name "unconnected-(P2-Pad40)") (class "Default")
      (node (ref "P2") (pin "40") (pinfunction "40_40") (pintype "passive"))
    )
    (net (code "270") (name "unconnected-(P2-Pad41)") (class "Default")
      (node (ref "P2") (pin "41") (pinfunction "41_41") (pintype "passive"))
    )
    (net (code "271") (name "unconnected-(P2-Pad42)") (class "Default")
      (node (ref "P2") (pin "42") (pinfunction "42_42") (pintype "passive"))
    )
    (net (code "272") (name "unconnected-(P2-Pad43)") (class "Default")
      (node (ref "P2") (pin "43") (pinfunction "43_43") (pintype "passive"))
    )
    (net (code "273") (name "unconnected-(P2-Pad44)") (class "Default")
      (node (ref "P2") (pin "44") (pinfunction "44_44") (pintype "passive"))
    )
    (net (code "274") (name "unconnected-(P2-Pad45)") (class "Default")
      (node (ref "P2") (pin "45") (pinfunction "45_45") (pintype "passive"))
    )
    (net (code "275") (name "unconnected-(P2-Pad46)") (class "Default")
      (node (ref "P2") (pin "46") (pinfunction "46_46") (pintype "passive"))
    )
    (net (code "276") (name "unconnected-(U1-EXTCLK-Pad25)") (class "Default")
      (node (ref "U1") (pin "25") (pinfunction "EXTCLK_25") (pintype "input"))
    )
    (net (code "277") (name "unconnected-(U1-LED6-Pad12)") (class "Default")
      (node (ref "U1") (pin "12") (pinfunction "LED6_12") (pintype "output"))
    )
    (net (code "278") (name "unconnected-(U1-LED7-Pad13)") (class "Default")
      (node (ref "U1") (pin "13") (pinfunction "LED7_13") (pintype "output"))
    )
    (net (code "279") (name "unconnected-(U1-LED8-Pad15)") (class "Default")
      (node (ref "U1") (pin "15") (pinfunction "LED8_15") (pintype "output"))
    )
    (net (code "280") (name "unconnected-(U2-~{WC}-Pad7)") (class "Default")
      (node (ref "U2") (pin "7") (pinfunction "~{WC}_7") (pintype "no_connect"))
    )
    (net (code "281") (name "unconnected-(U3-NC-Pad16)") (class "Default")
      (node (ref "U3") (pin "16") (pinfunction "NC_16") (pintype "no_connect"))
    )
    (net (code "282") (name "unconnected-(U3-NC_2-Pad13)") (class "Default")
      (node (ref "U3") (pin "13") (pinfunction "NC_2_13") (pintype "no_connect"))
    )
    (net (code "283") (name "unconnected-(U4-EN-Pad9)") (class "Default")
      (node (ref "U4") (pin "9") (pinfunction "EN_9") (pintype "input"))
    )
    (net (code "284") (name "unconnected-(U5-EN-Pad9)") (class "Default")
      (node (ref "U5") (pin "9") (pinfunction "EN_9") (pintype "input"))
    )
    (net (code "285") (name "unconnected-(U10-QH_2-Pad9)") (class "Default")
      (node (ref "U10") (pin "9") (pinfunction "QH_2_9") (pintype "output"))
    )
  )
)
